# AES_HWR1_M2018.net
KiCad netlist of a schematic drawn in EAGLE
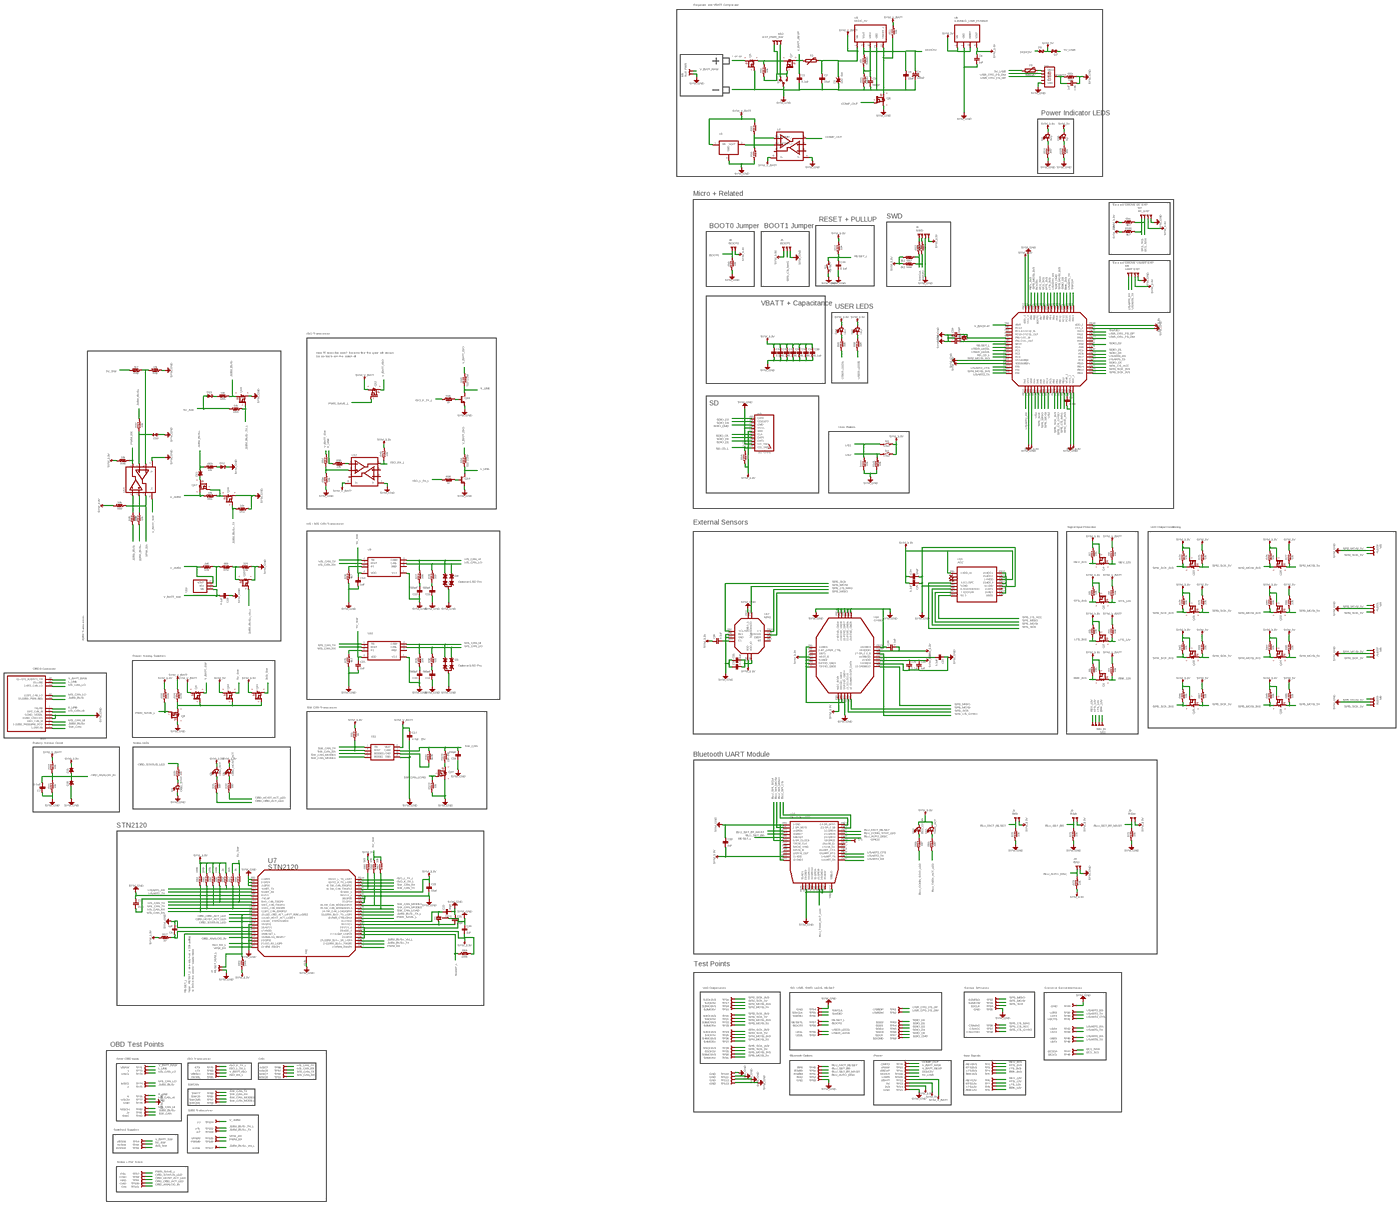
[diagram p0: schematic, sheet 1, overview]
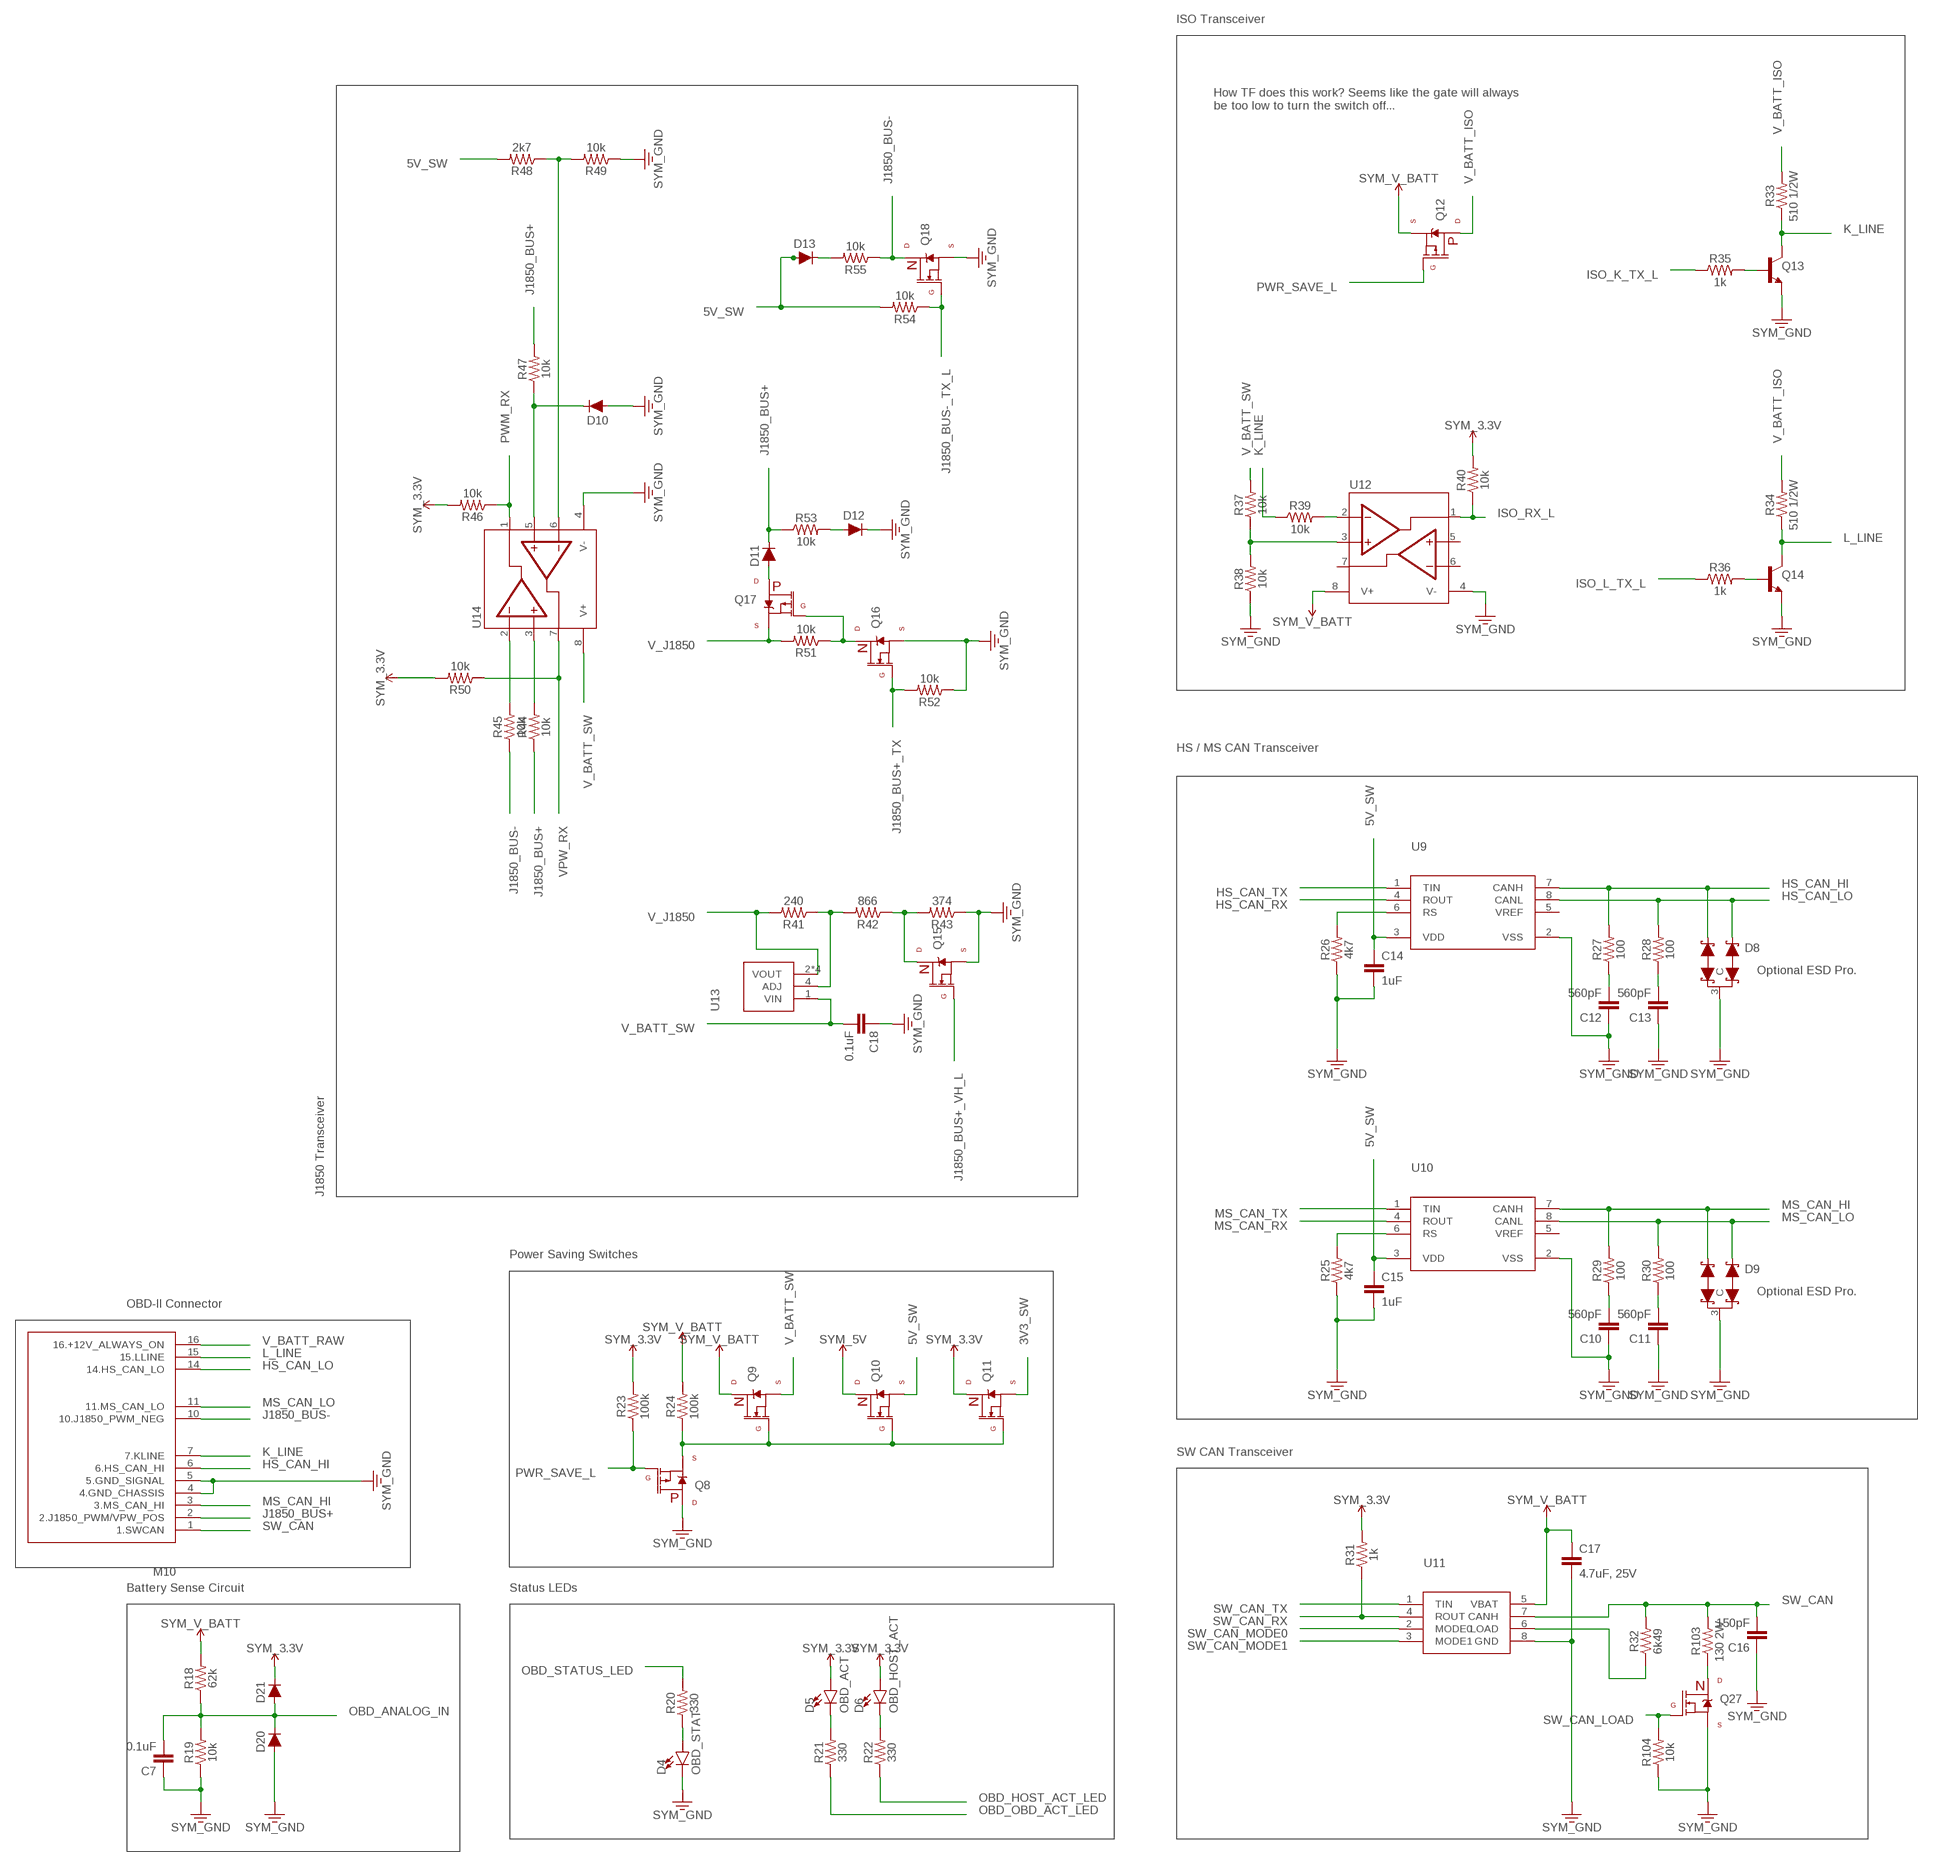
[diagram p1: schematic, sheet 1, part 1 of 5]
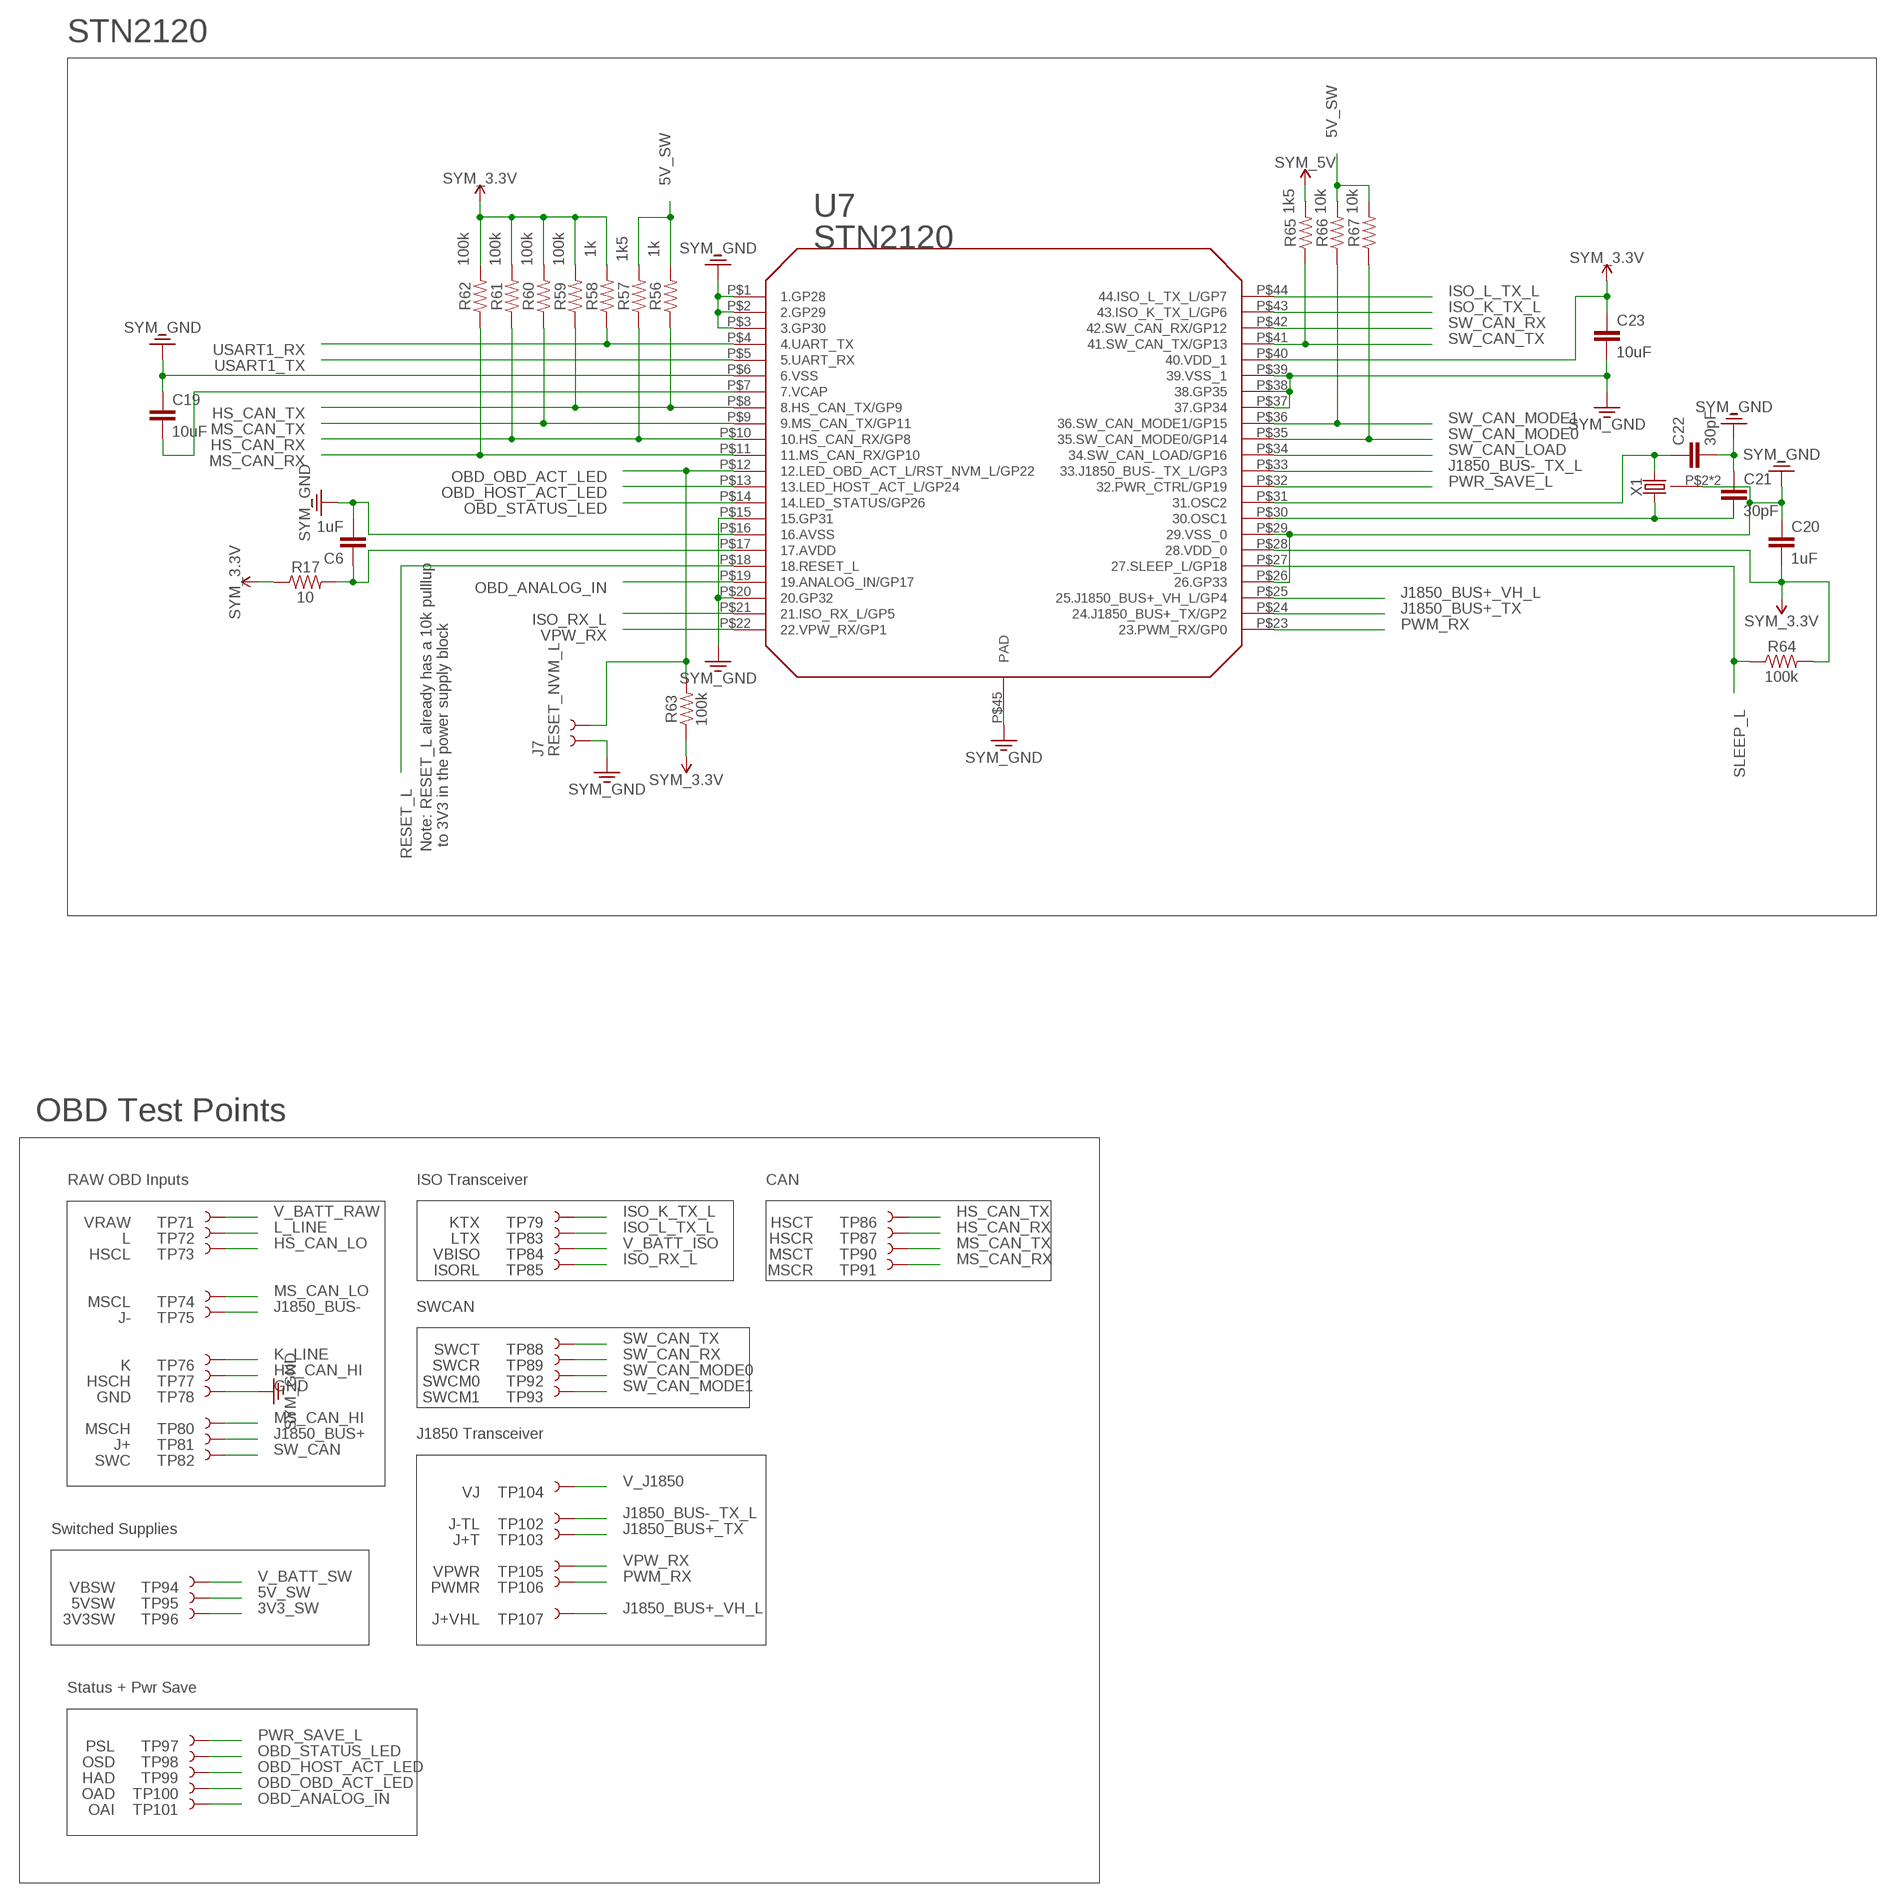
[diagram p2: schematic, sheet 1, part 2 of 5]
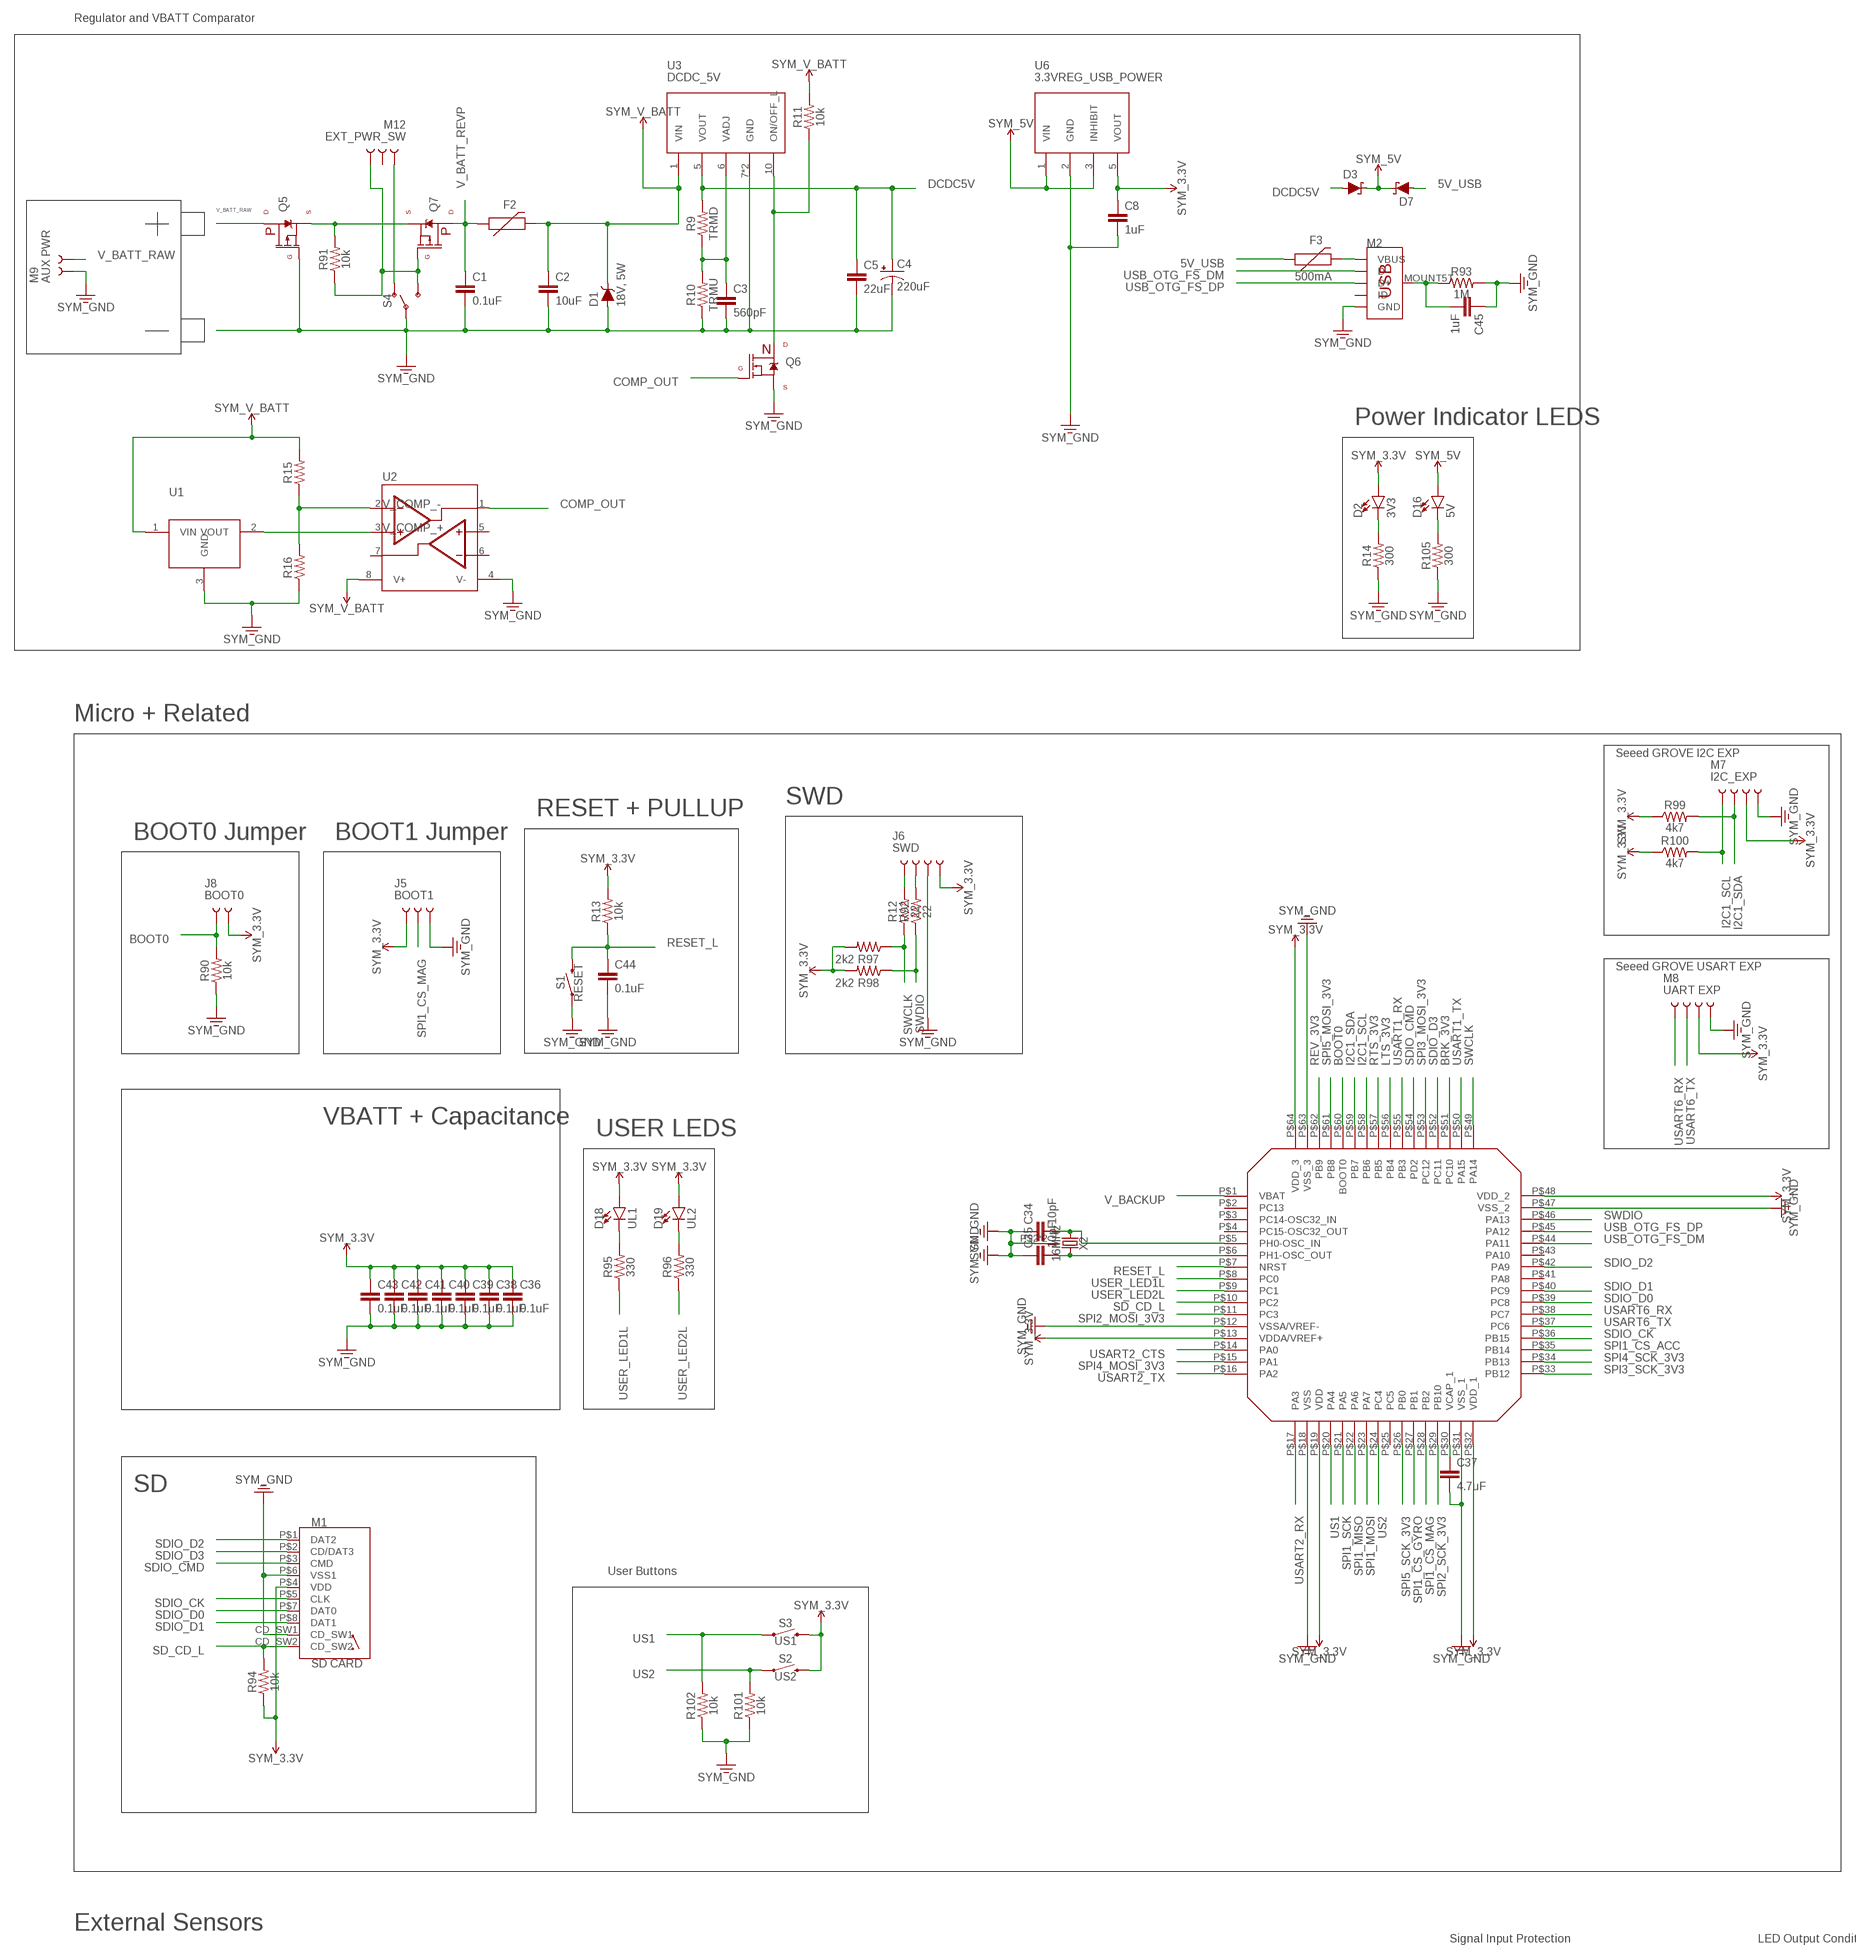
[diagram p3: schematic, sheet 1, part 3 of 5]
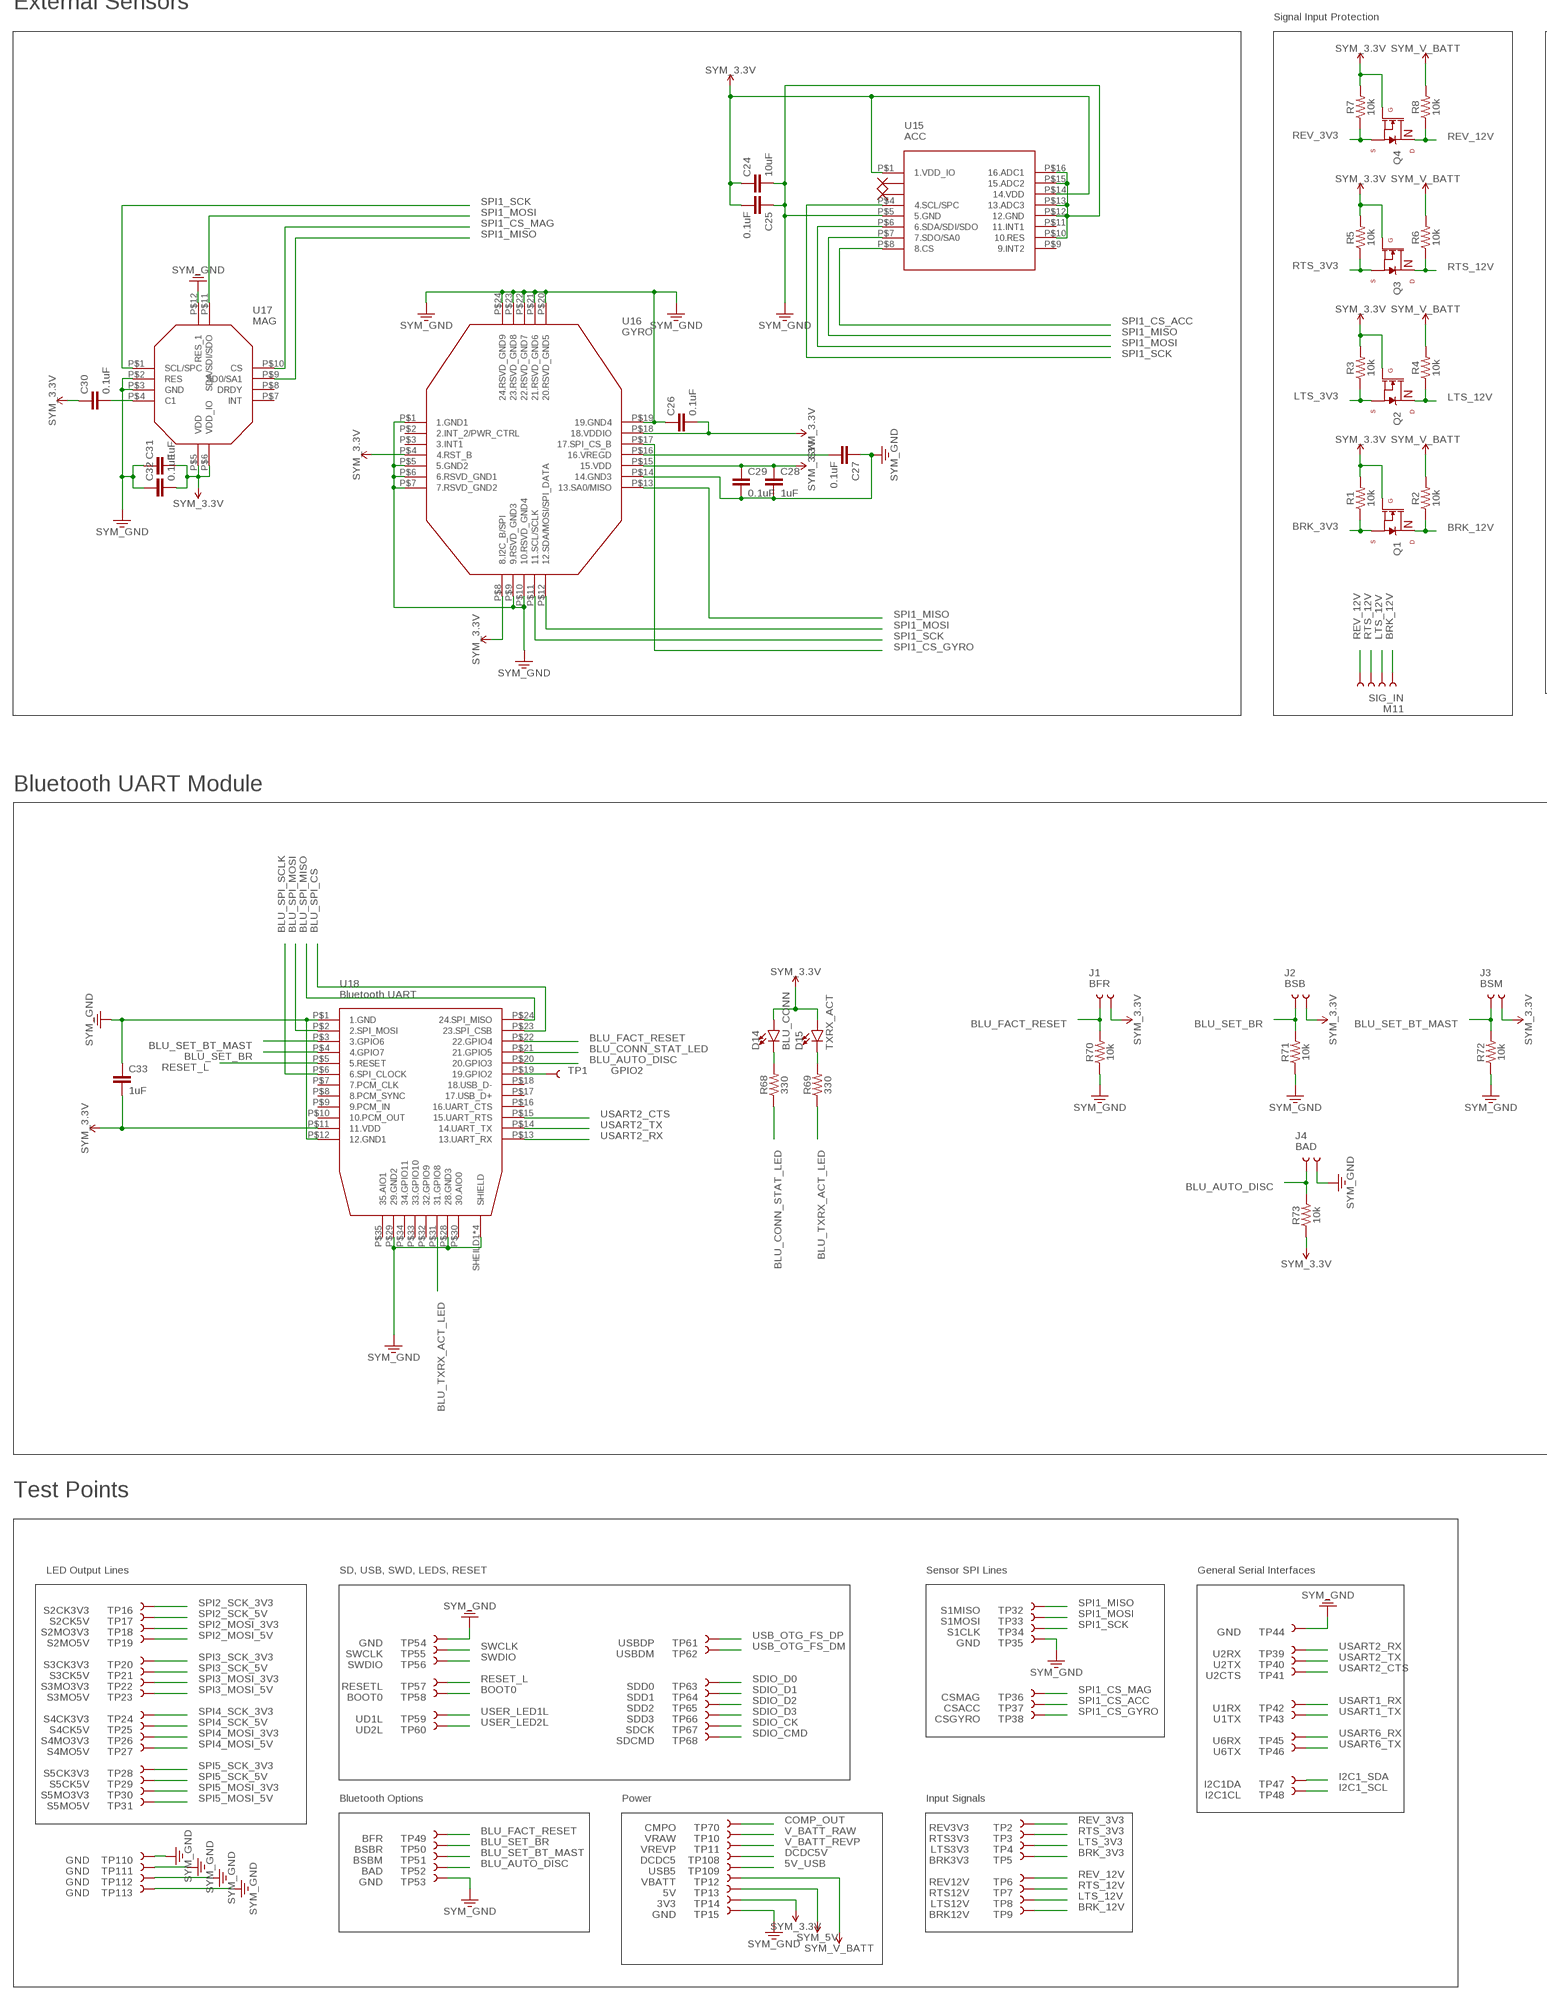
[diagram p4: schematic, sheet 1, part 4 of 5]
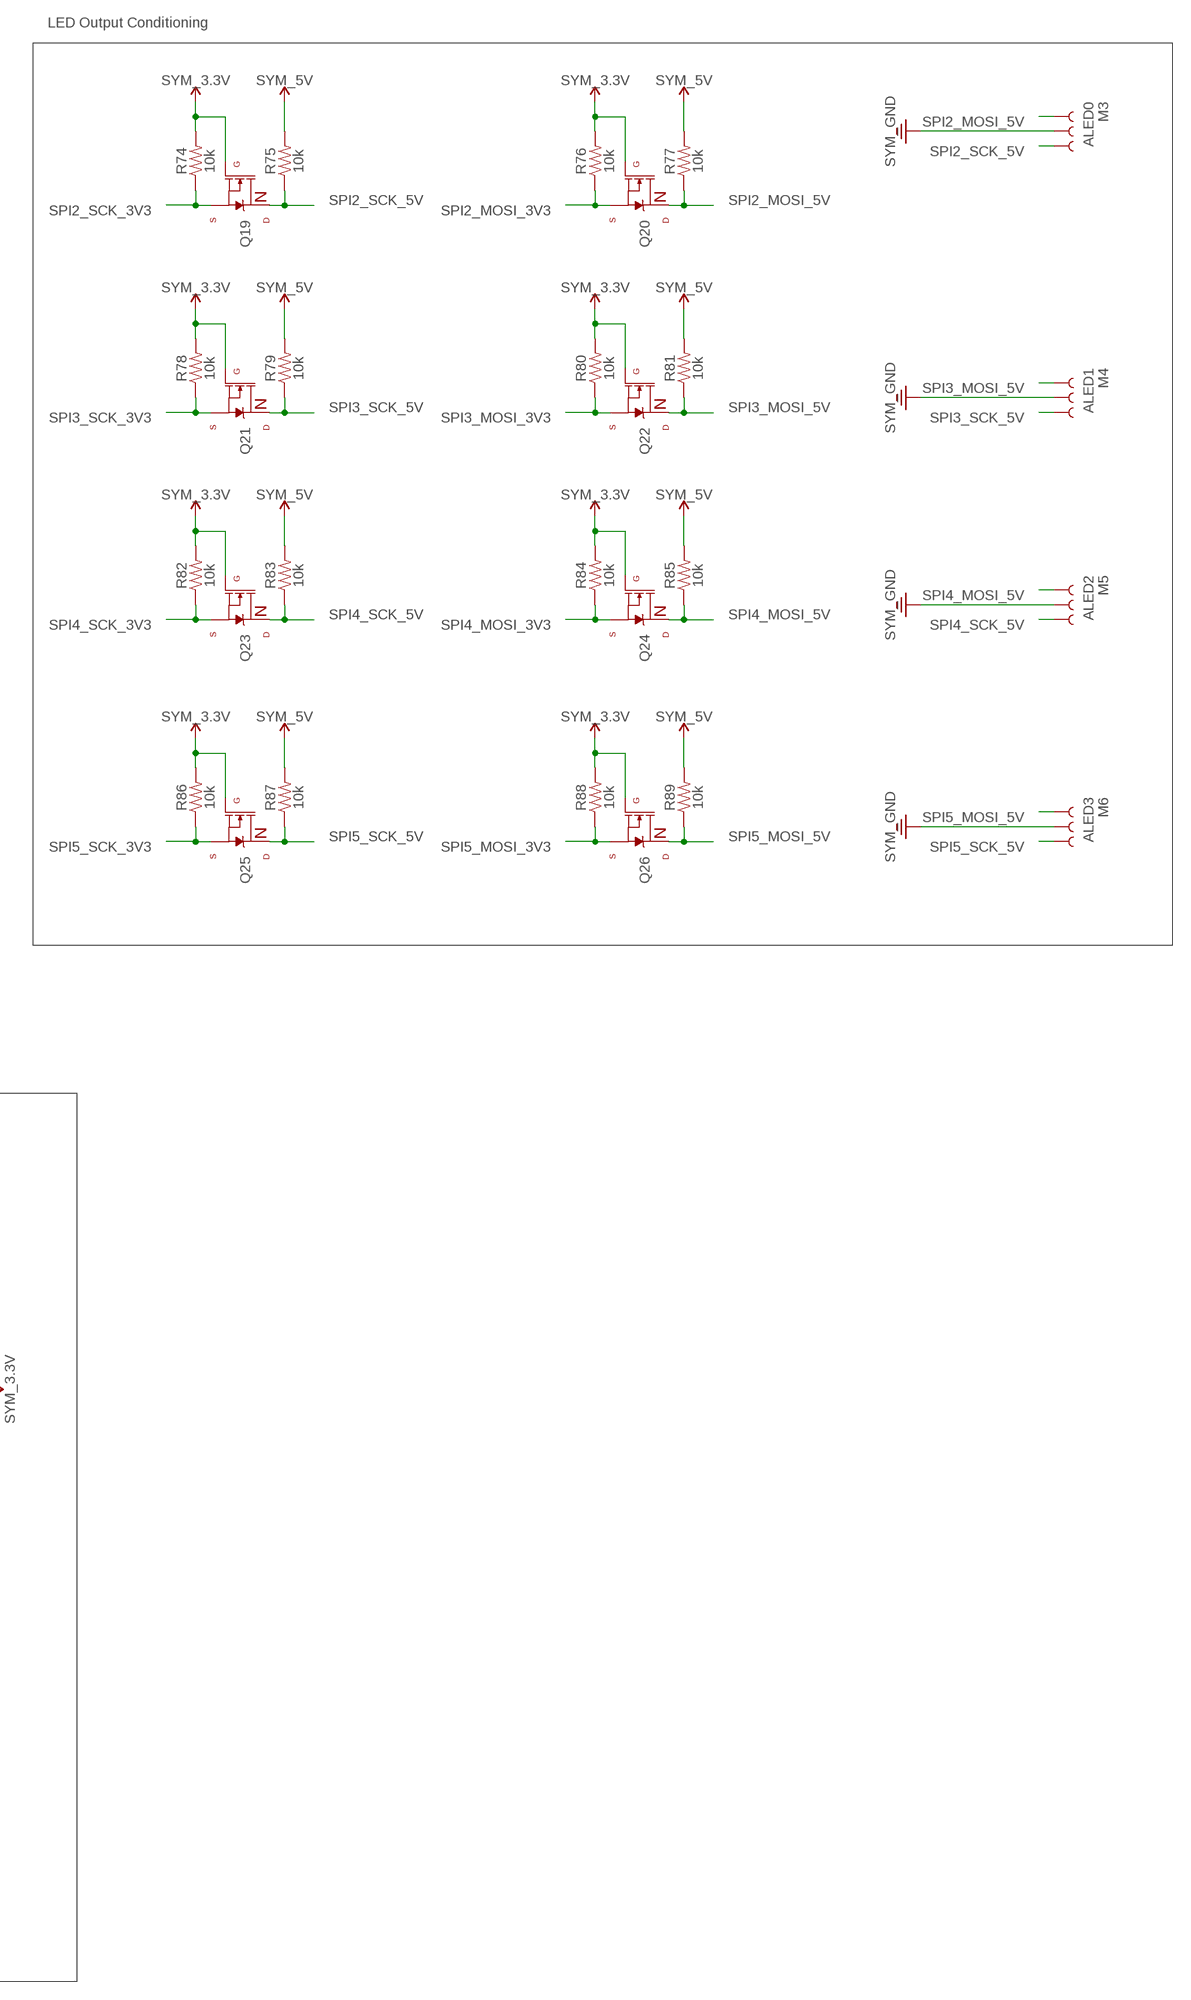
[diagram p5: schematic, sheet 1, part 5 of 5]

(export (version "E")
  (design (tool "Eeschema 10.0.6"))
  (components
    (comp (ref "C1")
      (value "0.1uF")
      (footprint "eagle-import:0603")
      (libsource (lib "eagle-import") (part "PASS_CAP_CER-SMD_0603"))
    )
    (comp (ref "C2")
      (value "10uF")
      (footprint "eagle-import:1206")
      (libsource (lib "eagle-import") (part "PASS_CAP_CER-SMD_1206"))
    )
    (comp (ref "C3")
      (value "560pF")
      (footprint "eagle-import:0603")
      (libsource (lib "eagle-import") (part "PASS_CAP_CER-SMD_0603"))
    )
    (comp (ref "C4")
      (value "220uF")
      (footprint "eagle-import:2917_P")
      (libsource (lib "eagle-import") (part "PASS_CAP_TANT"))
    )
    (comp (ref "C5")
      (value "22uF")
      (footprint "eagle-import:1206")
      (libsource (lib "eagle-import") (part "PASS_CAP_CER-SMD_1206"))
    )
    (comp (ref "C6")
      (value "1uF")
      (footprint "eagle-import:0603")
      (libsource (lib "eagle-import") (part "PASS_CAP_CER-SMD_0603"))
    )
    (comp (ref "C7")
      (value "0.1uF")
      (footprint "eagle-import:0603")
      (libsource (lib "eagle-import") (part "PASS_CAP_CER-SMD_0603"))
    )
    (comp (ref "C8")
      (value "1uF")
      (footprint "eagle-import:0603")
      (libsource (lib "eagle-import") (part "PASS_CAP_CER-SMD_0603"))
    )
    (comp (ref "C10")
      (value "560pF")
      (footprint "eagle-import:0603")
      (libsource (lib "eagle-import") (part "PASS_CAP_CER-SMD_0603"))
    )
    (comp (ref "C11")
      (value "560pF")
      (footprint "eagle-import:0603")
      (libsource (lib "eagle-import") (part "PASS_CAP_CER-SMD_0603"))
    )
    (comp (ref "C12")
      (value "560pF")
      (footprint "eagle-import:0603")
      (libsource (lib "eagle-import") (part "PASS_CAP_CER-SMD_0603"))
    )
    (comp (ref "C13")
      (value "560pF")
      (footprint "eagle-import:0603")
      (libsource (lib "eagle-import") (part "PASS_CAP_CER-SMD_0603"))
    )
    (comp (ref "C14")
      (value "1uF")
      (footprint "eagle-import:0603")
      (libsource (lib "eagle-import") (part "PASS_CAP_CER-SMD_0603"))
    )
    (comp (ref "C15")
      (value "1uF")
      (footprint "eagle-import:0603")
      (libsource (lib "eagle-import") (part "PASS_CAP_CER-SMD_0603"))
    )
    (comp (ref "C16")
      (value "150pF")
      (footprint "eagle-import:0603")
      (libsource (lib "eagle-import") (part "PASS_CAP_CER-SMD_0603"))
    )
    (comp (ref "C17")
      (value "4.7uF, 25V")
      (footprint "eagle-import:0603")
      (libsource (lib "eagle-import") (part "PASS_CAP_CER-SMD_0603"))
    )
    (comp (ref "C18")
      (value "0.1uF")
      (footprint "eagle-import:0603")
      (libsource (lib "eagle-import") (part "PASS_CAP_CER-SMD_0603"))
    )
    (comp (ref "C19")
      (value "10uF")
      (footprint "eagle-import:1206")
      (libsource (lib "eagle-import") (part "PASS_CAP_CER-SMD_1206"))
    )
    (comp (ref "C20")
      (value "1uF")
      (footprint "eagle-import:0603")
      (libsource (lib "eagle-import") (part "PASS_CAP_CER-SMD_0603"))
    )
    (comp (ref "C21")
      (value "30pF")
      (footprint "eagle-import:0603")
      (libsource (lib "eagle-import") (part "PASS_CAP_CER-SMD_0603"))
    )
    (comp (ref "C22")
      (value "30pF")
      (footprint "eagle-import:0603")
      (libsource (lib "eagle-import") (part "PASS_CAP_CER-SMD_0603"))
    )
    (comp (ref "C23")
      (value "10uF")
      (footprint "eagle-import:0603")
      (libsource (lib "eagle-import") (part "PASS_CAP_CER-SMD_0603"))
    )
    (comp (ref "C24")
      (value "10uF")
      (footprint "eagle-import:0603")
      (libsource (lib "eagle-import") (part "PASS_CAP_CER-SMD_0603"))
    )
    (comp (ref "C25")
      (value "0.1uF")
      (footprint "eagle-import:0603")
      (libsource (lib "eagle-import") (part "PASS_CAP_CER-SMD_0603"))
    )
    (comp (ref "C26")
      (value "0.1uF")
      (footprint "eagle-import:0603")
      (libsource (lib "eagle-import") (part "PASS_CAP_CER-SMD_0603"))
    )
    (comp (ref "C27")
      (value "0.1uF")
      (footprint "eagle-import:0603")
      (libsource (lib "eagle-import") (part "PASS_CAP_CER-SMD_0603"))
    )
    (comp (ref "C28")
      (value "1uF")
      (footprint "eagle-import:0603")
      (libsource (lib "eagle-import") (part "PASS_CAP_CER-SMD_0603"))
    )
    (comp (ref "C29")
      (value "0.1uF")
      (footprint "eagle-import:0603")
      (libsource (lib "eagle-import") (part "PASS_CAP_CER-SMD_0603"))
    )
    (comp (ref "C30")
      (value "0.1uF")
      (footprint "eagle-import:0603")
      (libsource (lib "eagle-import") (part "PASS_CAP_CER-SMD_0603"))
    )
    (comp (ref "C31")
      (value "1uF")
      (footprint "eagle-import:0603")
      (libsource (lib "eagle-import") (part "PASS_CAP_CER-SMD_0603"))
    )
    (comp (ref "C32")
      (value "0.1uF")
      (footprint "eagle-import:0603")
      (libsource (lib "eagle-import") (part "PASS_CAP_CER-SMD_0603"))
    )
    (comp (ref "C33")
      (value "1uF")
      (footprint "eagle-import:0603")
      (libsource (lib "eagle-import") (part "PASS_CAP_CER-SMD_0603"))
    )
    (comp (ref "C34")
      (value "10pF")
      (footprint "eagle-import:0603")
      (libsource (lib "eagle-import") (part "PASS_CAP_CER-SMD_0603"))
    )
    (comp (ref "C35")
      (value "10pF")
      (footprint "eagle-import:0603")
      (libsource (lib "eagle-import") (part "PASS_CAP_CER-SMD_0603"))
    )
    (comp (ref "C36")
      (value "0.1uF")
      (footprint "eagle-import:0603")
      (libsource (lib "eagle-import") (part "PASS_CAP_CER-SMD_0603"))
    )
    (comp (ref "C37")
      (value "4.7uF")
      (footprint "eagle-import:0603")
      (libsource (lib "eagle-import") (part "PASS_CAP_CER-SMD_0603"))
    )
    (comp (ref "C38")
      (value "0.1uF")
      (footprint "eagle-import:0603")
      (libsource (lib "eagle-import") (part "PASS_CAP_CER-SMD_0603"))
    )
    (comp (ref "C39")
      (value "0.1uF")
      (footprint "eagle-import:0603")
      (libsource (lib "eagle-import") (part "PASS_CAP_CER-SMD_0603"))
    )
    (comp (ref "C40")
      (value "0.1uF")
      (footprint "eagle-import:0603")
      (libsource (lib "eagle-import") (part "PASS_CAP_CER-SMD_0603"))
    )
    (comp (ref "C41")
      (value "0.1uF")
      (footprint "eagle-import:0603")
      (libsource (lib "eagle-import") (part "PASS_CAP_CER-SMD_0603"))
    )
    (comp (ref "C42")
      (value "0.1uF")
      (footprint "eagle-import:0603")
      (libsource (lib "eagle-import") (part "PASS_CAP_CER-SMD_0603"))
    )
    (comp (ref "C43")
      (value "0.1uF")
      (footprint "eagle-import:0603")
      (libsource (lib "eagle-import") (part "PASS_CAP_CER-SMD_0603"))
    )
    (comp (ref "C44")
      (value "0.1uF")
      (footprint "eagle-import:0603")
      (libsource (lib "eagle-import") (part "PASS_CAP_CER-SMD_0603"))
    )
    (comp (ref "C45")
      (value "1uF")
      (footprint "eagle-import:0603")
      (libsource (lib "eagle-import") (part "PASS_CAP_CER-SMD_0603"))
    )
    (comp (ref "D1")
      (value "18V, 5W")
      (footprint "eagle-import:DO-214AA")
      (libsource (lib "eagle-import") (part "PASS_DIODE_ZENER-SMBJ5355B"))
    )
    (comp (ref "D2")
      (value "3V3")
      (footprint "eagle-import:0603-POLAR")
      (libsource (lib "eagle-import") (part "PASS_DIODE_LED-SMLE13BC8TT86"))
    )
    (comp (ref "D3")
      (value "PASS_DIODE_SCHOTTKY-LSM115J")
      (footprint "eagle-import:DO-214BA")
      (libsource (lib "eagle-import") (part "PASS_DIODE_SCHOTTKY-LSM115J"))
    )
    (comp (ref "D4")
      (value "OBD_STAT")
      (footprint "eagle-import:0603-POLAR")
      (libsource (lib "eagle-import") (part "PASS_DIODE_LED-SMLE13BC8TT86"))
    )
    (comp (ref "D5")
      (value "OBD_ACT")
      (footprint "eagle-import:0603-POLAR")
      (libsource (lib "eagle-import") (part "PASS_DIODE_LED-LTST-C190KFKT"))
    )
    (comp (ref "D6")
      (value "OBD_HOST_ACT")
      (footprint "eagle-import:0603-POLAR")
      (libsource (lib "eagle-import") (part "PASS_DIODE_LED-LTST-C190KFKT"))
    )
    (comp (ref "D7")
      (value "PASS_DIODE_SCHOTTKY-LSM115J")
      (footprint "eagle-import:DO-214BA")
      (libsource (lib "eagle-import") (part "PASS_DIODE_SCHOTTKY-LSM115J"))
    )
    (comp (ref "D8")
      (value "PASS_DIODE_ESD_CAN-PESD1CAN-UX")
      (footprint "eagle-import:SOT23-3")
      (libsource (lib "eagle-import") (part "PASS_DIODE_ESD_CAN-PESD1CAN-UX"))
    )
    (comp (ref "D9")
      (value "PASS_DIODE_ESD_CAN-PESD1CAN-UX")
      (footprint "eagle-import:SOT23-3")
      (libsource (lib "eagle-import") (part "PASS_DIODE_ESD_CAN-PESD1CAN-UX"))
    )
    (comp (ref "D10")
      (value "PASS_DIODE_GEN-1N4148X")
      (footprint "eagle-import:SOD-523")
      (libsource (lib "eagle-import") (part "PASS_DIODE_GEN-1N4148X"))
    )
    (comp (ref "D11")
      (value "PASS_DIODE_GEN-1N4148X")
      (footprint "eagle-import:SOD-523")
      (libsource (lib "eagle-import") (part "PASS_DIODE_GEN-1N4148X"))
    )
    (comp (ref "D12")
      (value "PASS_DIODE_GEN-1N4148X")
      (footprint "eagle-import:SOD-523")
      (libsource (lib "eagle-import") (part "PASS_DIODE_GEN-1N4148X"))
    )
    (comp (ref "D13")
      (value "PASS_DIODE_GEN-1N4148X")
      (footprint "eagle-import:SOD-523")
      (libsource (lib "eagle-import") (part "PASS_DIODE_GEN-1N4148X"))
    )
    (comp (ref "D14")
      (value "BLU_CONN")
      (footprint "eagle-import:0603-POLAR")
      (libsource (lib "eagle-import") (part "PASS_DIODE_LED-SMLE13BC8TT86"))
    )
    (comp (ref "D15")
      (value "TXRX_ACT")
      (footprint "eagle-import:0603-POLAR")
      (libsource (lib "eagle-import") (part "PASS_DIODE_LED-LTST-C190KFKT"))
    )
    (comp (ref "D16")
      (value "5V")
      (footprint "eagle-import:0603-POLAR")
      (libsource (lib "eagle-import") (part "PASS_DIODE_LED-SMLE13BC8TT86"))
    )
    (comp (ref "D18")
      (value "UL1")
      (footprint "eagle-import:0603-POLAR")
      (libsource (lib "eagle-import") (part "PASS_DIODE_LED-SMLE13BC8TT86"))
    )
    (comp (ref "D19")
      (value "UL2")
      (footprint "eagle-import:0603-POLAR")
      (libsource (lib "eagle-import") (part "PASS_DIODE_LED-SMLE13BC8TT86"))
    )
    (comp (ref "D20")
      (value "PASS_DIODE_GEN-1N4148X")
      (footprint "eagle-import:SOD-523")
      (libsource (lib "eagle-import") (part "PASS_DIODE_GEN-1N4148X"))
    )
    (comp (ref "D21")
      (value "PASS_DIODE_GEN-1N4148X")
      (footprint "eagle-import:SOD-523")
      (libsource (lib "eagle-import") (part "PASS_DIODE_GEN-1N4148X"))
    )
    (comp (ref "F2")
      (value "PASS_FUSE_POLY-1206L200SLYR")
      (footprint "eagle-import:1206")
      (libsource (lib "eagle-import") (part "PASS_FUSE_POLY-1206L200SLYR"))
    )
    (comp (ref "F3")
      (value "500mA")
      (footprint "eagle-import:1206")
      (libsource (lib "eagle-import") (part "PASS_FUSE_POLY-0ZCJ0050FF2G"))
    )
    (comp (ref "J1")
      (value "BFR")
      (footprint "eagle-import:1X02")
      (libsource (lib "eagle-import") (part "ZMISC_JUMPER_2PTH_0.1IN"))
    )
    (comp (ref "J2")
      (value "BSB")
      (footprint "eagle-import:1X02")
      (libsource (lib "eagle-import") (part "ZMISC_JUMPER_2PTH_0.1IN"))
    )
    (comp (ref "J3")
      (value "BSM")
      (footprint "eagle-import:1X02")
      (libsource (lib "eagle-import") (part "ZMISC_JUMPER_2PTH_0.1IN"))
    )
    (comp (ref "J4")
      (value "BAD")
      (footprint "eagle-import:1X02")
      (libsource (lib "eagle-import") (part "ZMISC_JUMPER_2PTH_0.1IN"))
    )
    (comp (ref "J5")
      (value "BOOT1")
      (footprint "eagle-import:1X03")
      (libsource (lib "eagle-import") (part "ZMISC_JUMPER_3PTH_0.1IN"))
    )
    (comp (ref "J6")
      (value "SWD")
      (footprint "eagle-import:1X04")
      (libsource (lib "eagle-import") (part "ZMISC_JUMPER_4PTH_0.1IN"))
    )
    (comp (ref "J7")
      (value "RESET_NVM_L")
      (footprint "eagle-import:SMD_HEADER_0.1IN_2POS")
      (libsource (lib "eagle-import") (part "ZMISC_JUMPER_2SMD_0.1IN"))
    )
    (comp (ref "J8")
      (value "BOOT0")
      (footprint "eagle-import:1X02")
      (libsource (lib "eagle-import") (part "ZMISC_JUMPER_2PTH_0.1IN"))
    )
    (comp (ref "M1")
      (value "SD CARD")
      (footprint "eagle-import:SD_AMPHENOL_PUSH_PULL")
      (libsource (lib "eagle-import") (part "SD_MICRO_SOCKET-114-00841-68"))
    )
    (comp (ref "M2")
      (value "USB_MICRO-MID_MOUNT_REVERSIBLE")
      (footprint "eagle-import:MICROUSB")
      (libsource (lib "eagle-import") (part "USB_MICRO-MID_MOUNT_REVERSIBLE"))
    )
    (comp (ref "M3")
      (value "ALED0")
      (footprint "eagle-import:3_PIN_LOCK")
      (libsource (lib "eagle-import") (part "CONN_LED_OUT-MOLEX_5055670371"))
    )
    (comp (ref "M4")
      (value "ALED1")
      (footprint "eagle-import:3_PIN_LOCK")
      (libsource (lib "eagle-import") (part "CONN_LED_OUT-MOLEX_5055670371"))
    )
    (comp (ref "M5")
      (value "ALED2")
      (footprint "eagle-import:3_PIN_LOCK")
      (libsource (lib "eagle-import") (part "CONN_LED_OUT-MOLEX_5055670371"))
    )
    (comp (ref "M6")
      (value "ALED3")
      (footprint "eagle-import:3_PIN_LOCK")
      (libsource (lib "eagle-import") (part "CONN_LED_OUT-MOLEX_5055670371"))
    )
    (comp (ref "M7")
      (value "I2C_EXP")
      (footprint "eagle-import:4_PIN_LOCK")
      (libsource (lib "eagle-import") (part "CONN_LOCK_4-MOLEX_5055670471"))
    )
    (comp (ref "M8")
      (value "UART EXP")
      (footprint "eagle-import:4_PIN_LOCK")
      (libsource (lib "eagle-import") (part "CONN_LOCK_4-MOLEX_5055670471"))
    )
    (comp (ref "M9")
      (value "AUX PWR")
      (footprint "eagle-import:2_PIN_LOCK")
      (libsource (lib "eagle-import") (part "CONN_LOCK_2-5055670271"))
    )
    (comp (ref "M10")
      (value "OBD_CONN-4-794627-6")
      (footprint "eagle-import:OBD_16_SMD")
      (libsource (lib "eagle-import") (part "OBD_CONN-4-794627-6"))
    )
    (comp (ref "M11")
      (value "SIG_IN")
      (footprint "eagle-import:4_PIN_LOCK")
      (libsource (lib "eagle-import") (part "CONN_LOCK_4-MOLEX_5055670471"))
    )
    (comp (ref "M12")
      (value "EXT_PWR_SW")
      (footprint "eagle-import:3_PIN_LOCK")
      (libsource (lib "eagle-import") (part "CONN_LED_OUT-MOLEX_5055670371"))
    )
    (comp (ref "Q1")
      (value "PASS_NMOS-2N7002K")
      (footprint "eagle-import:SOT23-3@1")
      (libsource (lib "eagle-import") (part "PASS_NMOS-2N7002K"))
    )
    (comp (ref "Q2")
      (value "PASS_NMOS-2N7002K")
      (footprint "eagle-import:SOT23-3@1")
      (libsource (lib "eagle-import") (part "PASS_NMOS-2N7002K"))
    )
    (comp (ref "Q3")
      (value "PASS_NMOS-2N7002K")
      (footprint "eagle-import:SOT23-3@1")
      (libsource (lib "eagle-import") (part "PASS_NMOS-2N7002K"))
    )
    (comp (ref "Q4")
      (value "PASS_NMOS-2N7002K")
      (footprint "eagle-import:SOT23-3@1")
      (libsource (lib "eagle-import") (part "PASS_NMOS-2N7002K"))
    )
    (comp (ref "Q5")
      (value "AMP_MOSFET_PCH-MCQ4459")
      (footprint "eagle-import:SOP-8")
      (libsource (lib "eagle-import") (part "AMP_MOSFET_PCH-MCQ4459"))
    )
    (comp (ref "Q6")
      (value "AMP_MOSFET_NCH-2N7002K")
      (footprint "eagle-import:SOT23-3")
      (libsource (lib "eagle-import") (part "AMP_MOSFET_NCH-2N7002K"))
    )
    (comp (ref "Q7")
      (value "AMP_MOSFET_PCH-MCQ4459")
      (footprint "eagle-import:SOP-8")
      (libsource (lib "eagle-import") (part "AMP_MOSFET_PCH-MCQ4459"))
    )
    (comp (ref "Q8")
      (value "PASS_PMOS-MCQ4459")
      (footprint "eagle-import:SOP-8@1")
      (libsource (lib "eagle-import") (part "PASS_PMOS-MCQ4459"))
    )
    (comp (ref "Q9")
      (value "PASS_NMOS-2N7002K")
      (footprint "eagle-import:SOT23-3@1")
      (libsource (lib "eagle-import") (part "PASS_NMOS-2N7002K"))
    )
    (comp (ref "Q10")
      (value "PASS_NMOS-2N7002K")
      (footprint "eagle-import:SOT23-3@1")
      (libsource (lib "eagle-import") (part "PASS_NMOS-2N7002K"))
    )
    (comp (ref "Q11")
      (value "PASS_NMOS-2N7002K")
      (footprint "eagle-import:SOT23-3@1")
      (libsource (lib "eagle-import") (part "PASS_NMOS-2N7002K"))
    )
    (comp (ref "Q12")
      (value "AMP_MOSFET_PCH-MCQ4459")
      (footprint "eagle-import:SOP-8")
      (libsource (lib "eagle-import") (part "AMP_MOSFET_PCH-MCQ4459"))
    )
    (comp (ref "Q13")
      (value "AMP_BJT_NPNZXTN19100CFF")
      (footprint "eagle-import:SOT23-3")
      (libsource (lib "eagle-import") (part "AMP_BJT_NPNZXTN19100CFF"))
    )
    (comp (ref "Q14")
      (value "AMP_BJT_NPNZXTN19100CFF")
      (footprint "eagle-import:SOT23-3")
      (libsource (lib "eagle-import") (part "AMP_BJT_NPNZXTN19100CFF"))
    )
    (comp (ref "Q15")
      (value "AMP_MOSFET_NCH-2N7002K")
      (footprint "eagle-import:SOT23-3")
      (libsource (lib "eagle-import") (part "AMP_MOSFET_NCH-2N7002K"))
    )
    (comp (ref "Q16")
      (value "AMP_MOSFET_NCH-2N7002K")
      (footprint "eagle-import:SOT23-3")
      (libsource (lib "eagle-import") (part "AMP_MOSFET_NCH-2N7002K"))
    )
    (comp (ref "Q17")
      (value "AMP_MOSFET_PCH-MCQ4459")
      (footprint "eagle-import:SOP-8")
      (libsource (lib "eagle-import") (part "AMP_MOSFET_PCH-MCQ4459"))
    )
    (comp (ref "Q18")
      (value "AMP_MOSFET_NCH-2N7002K")
      (footprint "eagle-import:SOT23-3")
      (libsource (lib "eagle-import") (part "AMP_MOSFET_NCH-2N7002K"))
    )
    (comp (ref "Q19")
      (value "AMP_MOSFET_NCH-2N7002K")
      (footprint "eagle-import:SOT23-3")
      (libsource (lib "eagle-import") (part "AMP_MOSFET_NCH-2N7002K"))
    )
    (comp (ref "Q20")
      (value "AMP_MOSFET_NCH-2N7002K")
      (footprint "eagle-import:SOT23-3")
      (libsource (lib "eagle-import") (part "AMP_MOSFET_NCH-2N7002K"))
    )
    (comp (ref "Q21")
      (value "AMP_MOSFET_NCH-2N7002K")
      (footprint "eagle-import:SOT23-3")
      (libsource (lib "eagle-import") (part "AMP_MOSFET_NCH-2N7002K"))
    )
    (comp (ref "Q22")
      (value "AMP_MOSFET_NCH-2N7002K")
      (footprint "eagle-import:SOT23-3")
      (libsource (lib "eagle-import") (part "AMP_MOSFET_NCH-2N7002K"))
    )
    (comp (ref "Q23")
      (value "AMP_MOSFET_NCH-2N7002K")
      (footprint "eagle-import:SOT23-3")
      (libsource (lib "eagle-import") (part "AMP_MOSFET_NCH-2N7002K"))
    )
    (comp (ref "Q24")
      (value "AMP_MOSFET_NCH-2N7002K")
      (footprint "eagle-import:SOT23-3")
      (libsource (lib "eagle-import") (part "AMP_MOSFET_NCH-2N7002K"))
    )
    (comp (ref "Q25")
      (value "AMP_MOSFET_NCH-2N7002K")
      (footprint "eagle-import:SOT23-3")
      (libsource (lib "eagle-import") (part "AMP_MOSFET_NCH-2N7002K"))
    )
    (comp (ref "Q26")
      (value "AMP_MOSFET_NCH-2N7002K")
      (footprint "eagle-import:SOT23-3")
      (libsource (lib "eagle-import") (part "AMP_MOSFET_NCH-2N7002K"))
    )
    (comp (ref "Q27")
      (value "AMP_MOSFET_NCH-2N7002K")
      (footprint "eagle-import:SOT23-3")
      (libsource (lib "eagle-import") (part "AMP_MOSFET_NCH-2N7002K"))
    )
    (comp (ref "R1")
      (value "10k")
      (footprint "eagle-import:0603")
      (libsource (lib "eagle-import") (part "PASS_RES-SMD_0603"))
    )
    (comp (ref "R2")
      (value "10k")
      (footprint "eagle-import:0603")
      (libsource (lib "eagle-import") (part "PASS_RES-SMD_0603"))
    )
    (comp (ref "R3")
      (value "10k")
      (footprint "eagle-import:0603")
      (libsource (lib "eagle-import") (part "PASS_RES-SMD_0603"))
    )
    (comp (ref "R4")
      (value "10k")
      (footprint "eagle-import:0603")
      (libsource (lib "eagle-import") (part "PASS_RES-SMD_0603"))
    )
    (comp (ref "R5")
      (value "10k")
      (footprint "eagle-import:0603")
      (libsource (lib "eagle-import") (part "PASS_RES-SMD_0603"))
    )
    (comp (ref "R6")
      (value "10k")
      (footprint "eagle-import:0603")
      (libsource (lib "eagle-import") (part "PASS_RES-SMD_0603"))
    )
    (comp (ref "R7")
      (value "10k")
      (footprint "eagle-import:0603")
      (libsource (lib "eagle-import") (part "PASS_RES-SMD_0603"))
    )
    (comp (ref "R8")
      (value "10k")
      (footprint "eagle-import:0603")
      (libsource (lib "eagle-import") (part "PASS_RES-SMD_0603"))
    )
    (comp (ref "R9")
      (value "TRMD")
      (footprint "eagle-import:0603")
      (libsource (lib "eagle-import") (part "PASS_RES-SMD_0603"))
    )
    (comp (ref "R10")
      (value "TRMU")
      (footprint "eagle-import:0603")
      (libsource (lib "eagle-import") (part "PASS_RES-SMD_0603"))
    )
    (comp (ref "R11")
      (value "10k")
      (footprint "eagle-import:0603")
      (libsource (lib "eagle-import") (part "PASS_RES-SMD_0603"))
    )
    (comp (ref "R12")
      (value "22")
      (footprint "eagle-import:0603")
      (libsource (lib "eagle-import") (part "PASS_RES-SMD_0603"))
    )
    (comp (ref "R13")
      (value "10k")
      (footprint "eagle-import:0603")
      (libsource (lib "eagle-import") (part "PASS_RES-SMD_0603"))
    )
    (comp (ref "R14")
      (value "300")
      (footprint "eagle-import:0603")
      (libsource (lib "eagle-import") (part "PASS_RES-SMD_0603"))
    )
    (comp (ref "R15")
      (value "PASS_RES-SMD_0603")
      (footprint "eagle-import:0603")
      (libsource (lib "eagle-import") (part "PASS_RES-SMD_0603"))
    )
    (comp (ref "R16")
      (value "PASS_RES-SMD_0603")
      (footprint "eagle-import:0603")
      (libsource (lib "eagle-import") (part "PASS_RES-SMD_0603"))
    )
    (comp (ref "R17")
      (value "10")
      (footprint "eagle-import:0603")
      (libsource (lib "eagle-import") (part "PASS_RES-SMD_0603"))
    )
    (comp (ref "R18")
      (value "62k")
      (footprint "eagle-import:0603")
      (libsource (lib "eagle-import") (part "PASS_RES-SMD_0603"))
    )
    (comp (ref "R19")
      (value "10k")
      (footprint "eagle-import:0603")
      (libsource (lib "eagle-import") (part "PASS_RES-SMD_0603"))
    )
    (comp (ref "R20")
      (value "330")
      (footprint "eagle-import:0603")
      (libsource (lib "eagle-import") (part "PASS_RES-SMD_0603"))
    )
    (comp (ref "R21")
      (value "330")
      (footprint "eagle-import:0603")
      (libsource (lib "eagle-import") (part "PASS_RES-SMD_0603"))
    )
    (comp (ref "R22")
      (value "330")
      (footprint "eagle-import:0603")
      (libsource (lib "eagle-import") (part "PASS_RES-SMD_0603"))
    )
    (comp (ref "R23")
      (value "100k")
      (footprint "eagle-import:0603")
      (libsource (lib "eagle-import") (part "PASS_RES-SMD_0603"))
    )
    (comp (ref "R24")
      (value "100k")
      (footprint "eagle-import:0603")
      (libsource (lib "eagle-import") (part "PASS_RES-SMD_0603"))
    )
    (comp (ref "R25")
      (value "4k7")
      (footprint "eagle-import:0603")
      (libsource (lib "eagle-import") (part "PASS_RES-SMD_0603"))
    )
    (comp (ref "R26")
      (value "4k7")
      (footprint "eagle-import:0603")
      (libsource (lib "eagle-import") (part "PASS_RES-SMD_0603"))
    )
    (comp (ref "R27")
      (value "100")
      (footprint "eagle-import:0603")
      (libsource (lib "eagle-import") (part "PASS_RES-SMD_0603"))
    )
    (comp (ref "R28")
      (value "100")
      (footprint "eagle-import:0603")
      (libsource (lib "eagle-import") (part "PASS_RES-SMD_0603"))
    )
    (comp (ref "R29")
      (value "100")
      (footprint "eagle-import:0603")
      (libsource (lib "eagle-import") (part "PASS_RES-SMD_0603"))
    )
    (comp (ref "R30")
      (value "100")
      (footprint "eagle-import:0603")
      (libsource (lib "eagle-import") (part "PASS_RES-SMD_0603"))
    )
    (comp (ref "R31")
      (value "1k")
      (footprint "eagle-import:0603")
      (libsource (lib "eagle-import") (part "PASS_RES-SMD_0603"))
    )
    (comp (ref "R32")
      (value "6k49")
      (footprint "eagle-import:0603")
      (libsource (lib "eagle-import") (part "PASS_RES-SMD_0603"))
    )
    (comp (ref "R33")
      (value "510 1/2W")
      (footprint "eagle-import:1206")
      (libsource (lib "eagle-import") (part "PASS_RES-SMD_1206"))
    )
    (comp (ref "R34")
      (value "510 1/2W")
      (footprint "eagle-import:1206")
      (libsource (lib "eagle-import") (part "PASS_RES-SMD_1206"))
    )
    (comp (ref "R35")
      (value "1k")
      (footprint "eagle-import:0603")
      (libsource (lib "eagle-import") (part "PASS_RES-SMD_0603"))
    )
    (comp (ref "R36")
      (value "1k")
      (footprint "eagle-import:0603")
      (libsource (lib "eagle-import") (part "PASS_RES-SMD_0603"))
    )
    (comp (ref "R37")
      (value "10k")
      (footprint "eagle-import:0603")
      (libsource (lib "eagle-import") (part "PASS_RES-SMD_0603"))
    )
    (comp (ref "R38")
      (value "10k")
      (footprint "eagle-import:0603")
      (libsource (lib "eagle-import") (part "PASS_RES-SMD_0603"))
    )
    (comp (ref "R39")
      (value "10k")
      (footprint "eagle-import:0603")
      (libsource (lib "eagle-import") (part "PASS_RES-SMD_0603"))
    )
    (comp (ref "R40")
      (value "10k")
      (footprint "eagle-import:0603")
      (libsource (lib "eagle-import") (part "PASS_RES-SMD_0603"))
    )
    (comp (ref "R41")
      (value "240")
      (footprint "eagle-import:0603")
      (libsource (lib "eagle-import") (part "PASS_RES-SMD_0603"))
    )
    (comp (ref "R42")
      (value "866")
      (footprint "eagle-import:0603")
      (libsource (lib "eagle-import") (part "PASS_RES-SMD_0603"))
    )
    (comp (ref "R43")
      (value "374")
      (footprint "eagle-import:0603")
      (libsource (lib "eagle-import") (part "PASS_RES-SMD_0603"))
    )
    (comp (ref "R44")
      (value "10k")
      (footprint "eagle-import:0603")
      (libsource (lib "eagle-import") (part "PASS_RES-SMD_0603"))
    )
    (comp (ref "R45")
      (value "10k")
      (footprint "eagle-import:0603")
      (libsource (lib "eagle-import") (part "PASS_RES-SMD_0603"))
    )
    (comp (ref "R46")
      (value "10k")
      (footprint "eagle-import:0603")
      (libsource (lib "eagle-import") (part "PASS_RES-SMD_0603"))
    )
    (comp (ref "R47")
      (value "10k")
      (footprint "eagle-import:0603")
      (libsource (lib "eagle-import") (part "PASS_RES-SMD_0603"))
    )
    (comp (ref "R48")
      (value "2k7")
      (footprint "eagle-import:0603")
      (libsource (lib "eagle-import") (part "PASS_RES-SMD_0603"))
    )
    (comp (ref "R49")
      (value "10k")
      (footprint "eagle-import:0603")
      (libsource (lib "eagle-import") (part "PASS_RES-SMD_0603"))
    )
    (comp (ref "R50")
      (value "10k")
      (footprint "eagle-import:0603")
      (libsource (lib "eagle-import") (part "PASS_RES-SMD_0603"))
    )
    (comp (ref "R51")
      (value "10k")
      (footprint "eagle-import:0603")
      (libsource (lib "eagle-import") (part "PASS_RES-SMD_0603"))
    )
    (comp (ref "R52")
      (value "10k")
      (footprint "eagle-import:0603")
      (libsource (lib "eagle-import") (part "PASS_RES-SMD_0603"))
    )
    (comp (ref "R53")
      (value "10k")
      (footprint "eagle-import:0603")
      (libsource (lib "eagle-import") (part "PASS_RES-SMD_0603"))
    )
    (comp (ref "R54")
      (value "10k")
      (footprint "eagle-import:0603")
      (libsource (lib "eagle-import") (part "PASS_RES-SMD_0603"))
    )
    (comp (ref "R55")
      (value "10k")
      (footprint "eagle-import:0603")
      (libsource (lib "eagle-import") (part "PASS_RES-SMD_0603"))
    )
    (comp (ref "R56")
      (value "1k")
      (footprint "eagle-import:0603")
      (libsource (lib "eagle-import") (part "PASS_RES-SMD_0603"))
    )
    (comp (ref "R57")
      (value "1k5")
      (footprint "eagle-import:0603")
      (libsource (lib "eagle-import") (part "PASS_RES-SMD_0603"))
    )
    (comp (ref "R58")
      (value "1k")
      (footprint "eagle-import:0603")
      (libsource (lib "eagle-import") (part "PASS_RES-SMD_0603"))
    )
    (comp (ref "R59")
      (value "100k")
      (footprint "eagle-import:0603")
      (libsource (lib "eagle-import") (part "PASS_RES-SMD_0603"))
    )
    (comp (ref "R60")
      (value "100k")
      (footprint "eagle-import:0603")
      (libsource (lib "eagle-import") (part "PASS_RES-SMD_0603"))
    )
    (comp (ref "R61")
      (value "100k")
      (footprint "eagle-import:0603")
      (libsource (lib "eagle-import") (part "PASS_RES-SMD_0603"))
    )
    (comp (ref "R62")
      (value "100k")
      (footprint "eagle-import:0603")
      (libsource (lib "eagle-import") (part "PASS_RES-SMD_0603"))
    )
    (comp (ref "R63")
      (value "100k")
      (footprint "eagle-import:0603")
      (libsource (lib "eagle-import") (part "PASS_RES-SMD_0603"))
    )
    (comp (ref "R64")
      (value "100k")
      (footprint "eagle-import:0603")
      (libsource (lib "eagle-import") (part "PASS_RES-SMD_0603"))
    )
    (comp (ref "R65")
      (value "1k5")
      (footprint "eagle-import:0603")
      (libsource (lib "eagle-import") (part "PASS_RES-SMD_0603"))
    )
    (comp (ref "R66")
      (value "10k")
      (footprint "eagle-import:0603")
      (libsource (lib "eagle-import") (part "PASS_RES-SMD_0603"))
    )
    (comp (ref "R67")
      (value "10k")
      (footprint "eagle-import:0603")
      (libsource (lib "eagle-import") (part "PASS_RES-SMD_0603"))
    )
    (comp (ref "R68")
      (value "330")
      (footprint "eagle-import:0603")
      (libsource (lib "eagle-import") (part "PASS_RES-SMD_0603"))
    )
    (comp (ref "R69")
      (value "330")
      (footprint "eagle-import:0603")
      (libsource (lib "eagle-import") (part "PASS_RES-SMD_0603"))
    )
    (comp (ref "R70")
      (value "10k")
      (footprint "eagle-import:0603")
      (libsource (lib "eagle-import") (part "PASS_RES-SMD_0603"))
    )
    (comp (ref "R71")
      (value "10k")
      (footprint "eagle-import:0603")
      (libsource (lib "eagle-import") (part "PASS_RES-SMD_0603"))
    )
    (comp (ref "R72")
      (value "10k")
      (footprint "eagle-import:0603")
      (libsource (lib "eagle-import") (part "PASS_RES-SMD_0603"))
    )
    (comp (ref "R73")
      (value "10k")
      (footprint "eagle-import:0603")
      (libsource (lib "eagle-import") (part "PASS_RES-SMD_0603"))
    )
    (comp (ref "R74")
      (value "10k")
      (footprint "eagle-import:0603")
      (libsource (lib "eagle-import") (part "PASS_RES-SMD_0603"))
    )
    (comp (ref "R75")
      (value "10k")
      (footprint "eagle-import:0603")
      (libsource (lib "eagle-import") (part "PASS_RES-SMD_0603"))
    )
    (comp (ref "R76")
      (value "10k")
      (footprint "eagle-import:0603")
      (libsource (lib "eagle-import") (part "PASS_RES-SMD_0603"))
    )
    (comp (ref "R77")
      (value "10k")
      (footprint "eagle-import:0603")
      (libsource (lib "eagle-import") (part "PASS_RES-SMD_0603"))
    )
    (comp (ref "R78")
      (value "10k")
      (footprint "eagle-import:0603")
      (libsource (lib "eagle-import") (part "PASS_RES-SMD_0603"))
    )
    (comp (ref "R79")
      (value "10k")
      (footprint "eagle-import:0603")
      (libsource (lib "eagle-import") (part "PASS_RES-SMD_0603"))
    )
    (comp (ref "R80")
      (value "10k")
      (footprint "eagle-import:0603")
      (libsource (lib "eagle-import") (part "PASS_RES-SMD_0603"))
    )
    (comp (ref "R81")
      (value "10k")
      (footprint "eagle-import:0603")
      (libsource (lib "eagle-import") (part "PASS_RES-SMD_0603"))
    )
    (comp (ref "R82")
      (value "10k")
      (footprint "eagle-import:0603")
      (libsource (lib "eagle-import") (part "PASS_RES-SMD_0603"))
    )
    (comp (ref "R83")
      (value "10k")
      (footprint "eagle-import:0603")
      (libsource (lib "eagle-import") (part "PASS_RES-SMD_0603"))
    )
    (comp (ref "R84")
      (value "10k")
      (footprint "eagle-import:0603")
      (libsource (lib "eagle-import") (part "PASS_RES-SMD_0603"))
    )
    (comp (ref "R85")
      (value "10k")
      (footprint "eagle-import:0603")
      (libsource (lib "eagle-import") (part "PASS_RES-SMD_0603"))
    )
    (comp (ref "R86")
      (value "10k")
      (footprint "eagle-import:0603")
      (libsource (lib "eagle-import") (part "PASS_RES-SMD_0603"))
    )
    (comp (ref "R87")
      (value "10k")
      (footprint "eagle-import:0603")
      (libsource (lib "eagle-import") (part "PASS_RES-SMD_0603"))
    )
    (comp (ref "R88")
      (value "10k")
      (footprint "eagle-import:0603")
      (libsource (lib "eagle-import") (part "PASS_RES-SMD_0603"))
    )
    (comp (ref "R89")
      (value "10k")
      (footprint "eagle-import:0603")
      (libsource (lib "eagle-import") (part "PASS_RES-SMD_0603"))
    )
    (comp (ref "R90")
      (value "10k")
      (footprint "eagle-import:0603")
      (libsource (lib "eagle-import") (part "PASS_RES-SMD_0603"))
    )
    (comp (ref "R91")
      (value "10k")
      (footprint "eagle-import:0603")
      (libsource (lib "eagle-import") (part "PASS_RES-SMD_0603"))
    )
    (comp (ref "R92")
      (value "22")
      (footprint "eagle-import:0603")
      (libsource (lib "eagle-import") (part "PASS_RES-SMD_0603"))
    )
    (comp (ref "R93")
      (value "1M")
      (footprint "eagle-import:0603")
      (libsource (lib "eagle-import") (part "PASS_RES-SMD_0603"))
    )
    (comp (ref "R94")
      (value "10k")
      (footprint "eagle-import:0603")
      (libsource (lib "eagle-import") (part "PASS_RES-SMD_0603"))
    )
    (comp (ref "R95")
      (value "330")
      (footprint "eagle-import:0603")
      (libsource (lib "eagle-import") (part "PASS_RES-SMD_0603"))
    )
    (comp (ref "R96")
      (value "330")
      (footprint "eagle-import:0603")
      (libsource (lib "eagle-import") (part "PASS_RES-SMD_0603"))
    )
    (comp (ref "R97")
      (value "2k2")
      (footprint "eagle-import:0603")
      (libsource (lib "eagle-import") (part "PASS_RES-SMD_0603"))
    )
    (comp (ref "R98")
      (value "2k2")
      (footprint "eagle-import:0603")
      (libsource (lib "eagle-import") (part "PASS_RES-SMD_0603"))
    )
    (comp (ref "R99")
      (value "4k7")
      (footprint "eagle-import:0603")
      (libsource (lib "eagle-import") (part "PASS_RES-SMD_0603"))
    )
    (comp (ref "R100")
      (value "4k7")
      (footprint "eagle-import:0603")
      (libsource (lib "eagle-import") (part "PASS_RES-SMD_0603"))
    )
    (comp (ref "R101")
      (value "10k")
      (footprint "eagle-import:0603")
      (libsource (lib "eagle-import") (part "PASS_RES-SMD_0603"))
    )
    (comp (ref "R102")
      (value "10k")
      (footprint "eagle-import:0603")
      (libsource (lib "eagle-import") (part "PASS_RES-SMD_0603"))
    )
    (comp (ref "R103")
      (value "130 2W")
      (footprint "eagle-import:2512")
      (libsource (lib "eagle-import") (part "PASS_RES-SMD_2512"))
    )
    (comp (ref "R104")
      (value "10k")
      (footprint "eagle-import:0603")
      (libsource (lib "eagle-import") (part "PASS_RES-SMD_0603"))
    )
    (comp (ref "R105")
      (value "300")
      (footprint "eagle-import:0603")
      (libsource (lib "eagle-import") (part "PASS_RES-SMD_0603"))
    )
    (comp (ref "S1")
      (value "RESET")
      (footprint "eagle-import:PTS525")
      (libsource (lib "eagle-import") (part "BUTTON_TEMP_ON"))
    )
    (comp (ref "S2")
      (value "US2")
      (footprint "eagle-import:PTS525")
      (libsource (lib "eagle-import") (part "BUTTON_TEMP_ON"))
    )
    (comp (ref "S3")
      (value "US1")
      (footprint "eagle-import:PTS525")
      (libsource (lib "eagle-import") (part "BUTTON_TEMP_ON"))
    )
    (comp (ref "S4")
      (value "SWITCH_SPDT_SLIDE_SPARKFUN_SMD")
      (footprint "eagle-import:SPARKFUNSWITCH")
      (libsource (lib "eagle-import") (part "SWITCH_SPDT_SLIDE_SPARKFUN_SMD"))
    )
    (comp (ref "TP1")
      (value "GPIO2")
      (footprint "eagle-import:PAD.03X.05")
      (libsource (lib "eagle-import") (part "TEST-POINT3X5"))
    )
    (comp (ref "TP2")
      (value "REV3V3")
      (footprint "eagle-import:PAD.03X.05")
      (libsource (lib "eagle-import") (part "TEST-POINT3X5"))
    )
    (comp (ref "TP3")
      (value "RTS3V3")
      (footprint "eagle-import:PAD.03X.05")
      (libsource (lib "eagle-import") (part "TEST-POINT3X5"))
    )
    (comp (ref "TP4")
      (value "LTS3V3")
      (footprint "eagle-import:PAD.03X.05")
      (libsource (lib "eagle-import") (part "TEST-POINT3X5"))
    )
    (comp (ref "TP5")
      (value "BRK3V3")
      (footprint "eagle-import:PAD.03X.05")
      (libsource (lib "eagle-import") (part "TEST-POINT3X5"))
    )
    (comp (ref "TP6")
      (value "REV12V")
      (footprint "eagle-import:PAD.03X.05")
      (libsource (lib "eagle-import") (part "TEST-POINT3X5"))
    )
    (comp (ref "TP7")
      (value "RTS12V")
      (footprint "eagle-import:PAD.03X.05")
      (libsource (lib "eagle-import") (part "TEST-POINT3X5"))
    )
    (comp (ref "TP8")
      (value "LTS12V")
      (footprint "eagle-import:PAD.03X.05")
      (libsource (lib "eagle-import") (part "TEST-POINT3X5"))
    )
    (comp (ref "TP9")
      (value "BRK12V")
      (footprint "eagle-import:PAD.03X.05")
      (libsource (lib "eagle-import") (part "TEST-POINT3X5"))
    )
    (comp (ref "TP10")
      (value "VRAW")
      (footprint "eagle-import:PAD.03X.05")
      (libsource (lib "eagle-import") (part "TEST-POINT3X5"))
    )
    (comp (ref "TP11")
      (value "VREVP")
      (footprint "eagle-import:PAD.03X.05")
      (libsource (lib "eagle-import") (part "TEST-POINT3X5"))
    )
    (comp (ref "TP12")
      (value "VBATT")
      (footprint "eagle-import:PAD.03X.05")
      (libsource (lib "eagle-import") (part "TEST-POINT3X5"))
    )
    (comp (ref "TP13")
      (value "5V")
      (footprint "eagle-import:PAD.03X.05")
      (libsource (lib "eagle-import") (part "TEST-POINT3X5"))
    )
    (comp (ref "TP14")
      (value "3V3")
      (footprint "eagle-import:PAD.03X.05")
      (libsource (lib "eagle-import") (part "TEST-POINT3X5"))
    )
    (comp (ref "TP15")
      (value "GND")
      (footprint "eagle-import:PAD.03X.05")
      (libsource (lib "eagle-import") (part "TEST-POINT3X5"))
    )
    (comp (ref "TP16")
      (value "S2CK3V3")
      (footprint "eagle-import:PAD.03X.05")
      (libsource (lib "eagle-import") (part "TEST-POINT3X5"))
    )
    (comp (ref "TP17")
      (value "S2CK5V")
      (footprint "eagle-import:PAD.03X.05")
      (libsource (lib "eagle-import") (part "TEST-POINT3X5"))
    )
    (comp (ref "TP18")
      (value "S2MO3V3")
      (footprint "eagle-import:PAD.03X.05")
      (libsource (lib "eagle-import") (part "TEST-POINT3X5"))
    )
    (comp (ref "TP19")
      (value "S2MO5V")
      (footprint "eagle-import:PAD.03X.05")
      (libsource (lib "eagle-import") (part "TEST-POINT3X5"))
    )
    (comp (ref "TP20")
      (value "S3CK3V3")
      (footprint "eagle-import:PAD.03X.05")
      (libsource (lib "eagle-import") (part "TEST-POINT3X5"))
    )
    (comp (ref "TP21")
      (value "S3CK5V")
      (footprint "eagle-import:PAD.03X.05")
      (libsource (lib "eagle-import") (part "TEST-POINT3X5"))
    )
    (comp (ref "TP22")
      (value "S3MO3V3")
      (footprint "eagle-import:PAD.03X.05")
      (libsource (lib "eagle-import") (part "TEST-POINT3X5"))
    )
    (comp (ref "TP23")
      (value "S3MO5V")
      (footprint "eagle-import:PAD.03X.05")
      (libsource (lib "eagle-import") (part "TEST-POINT3X5"))
    )
    (comp (ref "TP24")
      (value "S4CK3V3")
      (footprint "eagle-import:PAD.03X.05")
      (libsource (lib "eagle-import") (part "TEST-POINT3X5"))
    )
    (comp (ref "TP25")
      (value "S4CK5V")
      (footprint "eagle-import:PAD.03X.05")
      (libsource (lib "eagle-import") (part "TEST-POINT3X5"))
    )
    (comp (ref "TP26")
      (value "S4MO3V3")
      (footprint "eagle-import:PAD.03X.05")
      (libsource (lib "eagle-import") (part "TEST-POINT3X5"))
    )
    (comp (ref "TP27")
      (value "S4MO5V")
      (footprint "eagle-import:PAD.03X.05")
      (libsource (lib "eagle-import") (part "TEST-POINT3X5"))
    )
    (comp (ref "TP28")
      (value "S5CK3V3")
      (footprint "eagle-import:PAD.03X.05")
      (libsource (lib "eagle-import") (part "TEST-POINT3X5"))
    )
    (comp (ref "TP29")
      (value "S5CK5V")
      (footprint "eagle-import:PAD.03X.05")
      (libsource (lib "eagle-import") (part "TEST-POINT3X5"))
    )
    (comp (ref "TP30")
      (value "S5MO3V3")
      (footprint "eagle-import:PAD.03X.05")
      (libsource (lib "eagle-import") (part "TEST-POINT3X5"))
    )
    (comp (ref "TP31")
      (value "S5MO5V")
      (footprint "eagle-import:PAD.03X.05")
      (libsource (lib "eagle-import") (part "TEST-POINT3X5"))
    )
    (comp (ref "TP32")
      (value "S1MISO")
      (footprint "eagle-import:PAD.03X.05")
      (libsource (lib "eagle-import") (part "TEST-POINT3X5"))
    )
    (comp (ref "TP33")
      (value "S1MOSI")
      (footprint "eagle-import:PAD.03X.05")
      (libsource (lib "eagle-import") (part "TEST-POINT3X5"))
    )
    (comp (ref "TP34")
      (value "S1CLK")
      (footprint "eagle-import:PAD.03X.05")
      (libsource (lib "eagle-import") (part "TEST-POINT3X5"))
    )
    (comp (ref "TP35")
      (value "GND")
      (footprint "eagle-import:PAD.03X.05")
      (libsource (lib "eagle-import") (part "TEST-POINT3X5"))
    )
    (comp (ref "TP36")
      (value "CSMAG")
      (footprint "eagle-import:PAD.03X.05")
      (libsource (lib "eagle-import") (part "TEST-POINT3X5"))
    )
    (comp (ref "TP37")
      (value "CSACC")
      (footprint "eagle-import:PAD.03X.05")
      (libsource (lib "eagle-import") (part "TEST-POINT3X5"))
    )
    (comp (ref "TP38")
      (value "CSGYRO")
      (footprint "eagle-import:PAD.03X.05")
      (libsource (lib "eagle-import") (part "TEST-POINT3X5"))
    )
    (comp (ref "TP39")
      (value "U2RX")
      (footprint "eagle-import:PAD.03X.05")
      (libsource (lib "eagle-import") (part "TEST-POINT3X5"))
    )
    (comp (ref "TP40")
      (value "U2TX")
      (footprint "eagle-import:PAD.03X.05")
      (libsource (lib "eagle-import") (part "TEST-POINT3X5"))
    )
    (comp (ref "TP41")
      (value "U2CTS")
      (footprint "eagle-import:PAD.03X.05")
      (libsource (lib "eagle-import") (part "TEST-POINT3X5"))
    )
    (comp (ref "TP42")
      (value "U1RX")
      (footprint "eagle-import:PAD.03X.05")
      (libsource (lib "eagle-import") (part "TEST-POINT3X5"))
    )
    (comp (ref "TP43")
      (value "U1TX")
      (footprint "eagle-import:PAD.03X.05")
      (libsource (lib "eagle-import") (part "TEST-POINT3X5"))
    )
    (comp (ref "TP44")
      (value "GND")
      (footprint "eagle-import:PAD.03X.05")
      (libsource (lib "eagle-import") (part "TEST-POINT3X5"))
    )
    (comp (ref "TP45")
      (value "U6RX")
      (footprint "eagle-import:PAD.03X.05")
      (libsource (lib "eagle-import") (part "TEST-POINT3X5"))
    )
    (comp (ref "TP46")
      (value "U6TX")
      (footprint "eagle-import:PAD.03X.05")
      (libsource (lib "eagle-import") (part "TEST-POINT3X5"))
    )
    (comp (ref "TP47")
      (value "I2C1DA")
      (footprint "eagle-import:PAD.03X.05")
      (libsource (lib "eagle-import") (part "TEST-POINT3X5"))
    )
    (comp (ref "TP48")
      (value "I2C1CL")
      (footprint "eagle-import:PAD.03X.05")
      (libsource (lib "eagle-import") (part "TEST-POINT3X5"))
    )
    (comp (ref "TP49")
      (value "BFR")
      (footprint "eagle-import:PAD.03X.05")
      (libsource (lib "eagle-import") (part "TEST-POINT3X5"))
    )
    (comp (ref "TP50")
      (value "BSBR")
      (footprint "eagle-import:PAD.03X.05")
      (libsource (lib "eagle-import") (part "TEST-POINT3X5"))
    )
    (comp (ref "TP51")
      (value "BSBM")
      (footprint "eagle-import:PAD.03X.05")
      (libsource (lib "eagle-import") (part "TEST-POINT3X5"))
    )
    (comp (ref "TP52")
      (value "BAD")
      (footprint "eagle-import:PAD.03X.05")
      (libsource (lib "eagle-import") (part "TEST-POINT3X5"))
    )
    (comp (ref "TP53")
      (value "GND")
      (footprint "eagle-import:PAD.03X.05")
      (libsource (lib "eagle-import") (part "TEST-POINT3X5"))
    )
    (comp (ref "TP54")
      (value "GND")
      (footprint "eagle-import:PAD.03X.05")
      (libsource (lib "eagle-import") (part "TEST-POINT3X5"))
    )
    (comp (ref "TP55")
      (value "SWCLK")
      (footprint "eagle-import:PAD.03X.05")
      (libsource (lib "eagle-import") (part "TEST-POINT3X5"))
    )
    (comp (ref "TP56")
      (value "SWDIO")
      (footprint "eagle-import:PAD.03X.05")
      (libsource (lib "eagle-import") (part "TEST-POINT3X5"))
    )
    (comp (ref "TP57")
      (value "RESETL")
      (footprint "eagle-import:PAD.03X.05")
      (libsource (lib "eagle-import") (part "TEST-POINT3X5"))
    )
    (comp (ref "TP58")
      (value "BOOT0")
      (footprint "eagle-import:PAD.03X.05")
      (libsource (lib "eagle-import") (part "TEST-POINT3X5"))
    )
    (comp (ref "TP59")
      (value "UD1L")
      (footprint "eagle-import:PAD.03X.05")
      (libsource (lib "eagle-import") (part "TEST-POINT3X5"))
    )
    (comp (ref "TP60")
      (value "UD2L")
      (footprint "eagle-import:PAD.03X.05")
      (libsource (lib "eagle-import") (part "TEST-POINT3X5"))
    )
    (comp (ref "TP61")
      (value "USBDP")
      (footprint "eagle-import:PAD.03X.05")
      (libsource (lib "eagle-import") (part "TEST-POINT3X5"))
    )
    (comp (ref "TP62")
      (value "USBDM")
      (footprint "eagle-import:PAD.03X.05")
      (libsource (lib "eagle-import") (part "TEST-POINT3X5"))
    )
    (comp (ref "TP63")
      (value "SDD0")
      (footprint "eagle-import:PAD.03X.05")
      (libsource (lib "eagle-import") (part "TEST-POINT3X5"))
    )
    (comp (ref "TP64")
      (value "SDD1")
      (footprint "eagle-import:PAD.03X.05")
      (libsource (lib "eagle-import") (part "TEST-POINT3X5"))
    )
    (comp (ref "TP65")
      (value "SDD2")
      (footprint "eagle-import:PAD.03X.05")
      (libsource (lib "eagle-import") (part "TEST-POINT3X5"))
    )
    (comp (ref "TP66")
      (value "SDD3")
      (footprint "eagle-import:PAD.03X.05")
      (libsource (lib "eagle-import") (part "TEST-POINT3X5"))
    )
    (comp (ref "TP67")
      (value "SDCK")
      (footprint "eagle-import:PAD.03X.05")
      (libsource (lib "eagle-import") (part "TEST-POINT3X5"))
    )
    (comp (ref "TP68")
      (value "SDCMD")
      (footprint "eagle-import:PAD.03X.05")
      (libsource (lib "eagle-import") (part "TEST-POINT3X5"))
    )
    (comp (ref "TP70")
      (value "CMPO")
      (footprint "eagle-import:PAD.03X.05")
      (libsource (lib "eagle-import") (part "TEST-POINT3X5"))
    )
    (comp (ref "TP71")
      (value "VRAW")
      (footprint "eagle-import:PAD.03X.05")
      (libsource (lib "eagle-import") (part "TEST-POINT3X5"))
    )
    (comp (ref "TP72")
      (value "L")
      (footprint "eagle-import:PAD.03X.05")
      (libsource (lib "eagle-import") (part "TEST-POINT3X5"))
    )
    (comp (ref "TP73")
      (value "HSCL")
      (footprint "eagle-import:PAD.03X.05")
      (libsource (lib "eagle-import") (part "TEST-POINT3X5"))
    )
    (comp (ref "TP74")
      (value "MSCL")
      (footprint "eagle-import:PAD.03X.05")
      (libsource (lib "eagle-import") (part "TEST-POINT3X5"))
    )
    (comp (ref "TP75")
      (value "J-")
      (footprint "eagle-import:PAD.03X.05")
      (libsource (lib "eagle-import") (part "TEST-POINT3X5"))
    )
    (comp (ref "TP76")
      (value "K")
      (footprint "eagle-import:PAD.03X.05")
      (libsource (lib "eagle-import") (part "TEST-POINT3X5"))
    )
    (comp (ref "TP77")
      (value "HSCH")
      (footprint "eagle-import:PAD.03X.05")
      (libsource (lib "eagle-import") (part "TEST-POINT3X5"))
    )
    (comp (ref "TP78")
      (value "GND")
      (footprint "eagle-import:PAD.03X.05")
      (libsource (lib "eagle-import") (part "TEST-POINT3X5"))
    )
    (comp (ref "TP79")
      (value "KTX")
      (footprint "eagle-import:PAD.03X.05")
      (libsource (lib "eagle-import") (part "TEST-POINT3X5"))
    )
    (comp (ref "TP80")
      (value "MSCH")
      (footprint "eagle-import:PAD.03X.05")
      (libsource (lib "eagle-import") (part "TEST-POINT3X5"))
    )
    (comp (ref "TP81")
      (value "J+")
      (footprint "eagle-import:PAD.03X.05")
      (libsource (lib "eagle-import") (part "TEST-POINT3X5"))
    )
    (comp (ref "TP82")
      (value "SWC")
      (footprint "eagle-import:PAD.03X.05")
      (libsource (lib "eagle-import") (part "TEST-POINT3X5"))
    )
    (comp (ref "TP83")
      (value "LTX")
      (footprint "eagle-import:PAD.03X.05")
      (libsource (lib "eagle-import") (part "TEST-POINT3X5"))
    )
    (comp (ref "TP84")
      (value "VBISO")
      (footprint "eagle-import:PAD.03X.05")
      (libsource (lib "eagle-import") (part "TEST-POINT3X5"))
    )
    (comp (ref "TP85")
      (value "ISORL")
      (footprint "eagle-import:PAD.03X.05")
      (libsource (lib "eagle-import") (part "TEST-POINT3X5"))
    )
    (comp (ref "TP86")
      (value "HSCT")
      (footprint "eagle-import:PAD.03X.05")
      (libsource (lib "eagle-import") (part "TEST-POINT3X5"))
    )
    (comp (ref "TP87")
      (value "HSCR")
      (footprint "eagle-import:PAD.03X.05")
      (libsource (lib "eagle-import") (part "TEST-POINT3X5"))
    )
    (comp (ref "TP88")
      (value "SWCT")
      (footprint "eagle-import:PAD.03X.05")
      (libsource (lib "eagle-import") (part "TEST-POINT3X5"))
    )
    (comp (ref "TP89")
      (value "SWCR")
      (footprint "eagle-import:PAD.03X.05")
      (libsource (lib "eagle-import") (part "TEST-POINT3X5"))
    )
    (comp (ref "TP90")
      (value "MSCT")
      (footprint "eagle-import:PAD.03X.05")
      (libsource (lib "eagle-import") (part "TEST-POINT3X5"))
    )
    (comp (ref "TP91")
      (value "MSCR")
      (footprint "eagle-import:PAD.03X.05")
      (libsource (lib "eagle-import") (part "TEST-POINT3X5"))
    )
    (comp (ref "TP92")
      (value "SWCM0")
      (footprint "eagle-import:PAD.03X.05")
      (libsource (lib "eagle-import") (part "TEST-POINT3X5"))
    )
    (comp (ref "TP93")
      (value "SWCM1")
      (footprint "eagle-import:PAD.03X.05")
      (libsource (lib "eagle-import") (part "TEST-POINT3X5"))
    )
    (comp (ref "TP94")
      (value "VBSW")
      (footprint "eagle-import:PAD.03X.05")
      (libsource (lib "eagle-import") (part "TEST-POINT3X5"))
    )
    (comp (ref "TP95")
      (value "5VSW")
      (footprint "eagle-import:PAD.03X.05")
      (libsource (lib "eagle-import") (part "TEST-POINT3X5"))
    )
    (comp (ref "TP96")
      (value "3V3SW")
      (footprint "eagle-import:PAD.03X.05")
      (libsource (lib "eagle-import") (part "TEST-POINT3X5"))
    )
    (comp (ref "TP97")
      (value "PSL")
      (footprint "eagle-import:PAD.03X.05")
      (libsource (lib "eagle-import") (part "TEST-POINT3X5"))
    )
    (comp (ref "TP98")
      (value "OSD")
      (footprint "eagle-import:PAD.03X.05")
      (libsource (lib "eagle-import") (part "TEST-POINT3X5"))
    )
    (comp (ref "TP99")
      (value "HAD")
      (footprint "eagle-import:PAD.03X.05")
      (libsource (lib "eagle-import") (part "TEST-POINT3X5"))
    )
    (comp (ref "TP100")
      (value "OAD")
      (footprint "eagle-import:PAD.03X.05")
      (libsource (lib "eagle-import") (part "TEST-POINT3X5"))
    )
    (comp (ref "TP101")
      (value "OAI")
      (footprint "eagle-import:PAD.03X.05")
      (libsource (lib "eagle-import") (part "TEST-POINT3X5"))
    )
    (comp (ref "TP102")
      (value "J-TL")
      (footprint "eagle-import:PAD.03X.05")
      (libsource (lib "eagle-import") (part "TEST-POINT3X5"))
    )
    (comp (ref "TP103")
      (value "J+T")
      (footprint "eagle-import:PAD.03X.05")
      (libsource (lib "eagle-import") (part "TEST-POINT3X5"))
    )
    (comp (ref "TP104")
      (value "VJ")
      (footprint "eagle-import:PAD.03X.05")
      (libsource (lib "eagle-import") (part "TEST-POINT3X5"))
    )
    (comp (ref "TP105")
      (value "VPWR")
      (footprint "eagle-import:PAD.03X.05")
      (libsource (lib "eagle-import") (part "TEST-POINT3X5"))
    )
    (comp (ref "TP106")
      (value "PWMR")
      (footprint "eagle-import:PAD.03X.05")
      (libsource (lib "eagle-import") (part "TEST-POINT3X5"))
    )
    (comp (ref "TP107")
      (value "J+VHL")
      (footprint "eagle-import:PAD.03X.05")
      (libsource (lib "eagle-import") (part "TEST-POINT3X5"))
    )
    (comp (ref "TP108")
      (value "DCDC5")
      (footprint "eagle-import:PAD.03X.05")
      (libsource (lib "eagle-import") (part "TEST-POINT3X5"))
    )
    (comp (ref "TP109")
      (value "USB5")
      (footprint "eagle-import:PAD.03X.05")
      (libsource (lib "eagle-import") (part "TEST-POINT3X5"))
    )
    (comp (ref "TP110")
      (value "GND")
      (footprint "eagle-import:PAD.03X.05")
      (libsource (lib "eagle-import") (part "TEST-POINT3X5"))
    )
    (comp (ref "TP111")
      (value "GND")
      (footprint "eagle-import:PAD.03X.05")
      (libsource (lib "eagle-import") (part "TEST-POINT3X5"))
    )
    (comp (ref "TP112")
      (value "GND")
      (footprint "eagle-import:PAD.03X.05")
      (libsource (lib "eagle-import") (part "TEST-POINT3X5"))
    )
    (comp (ref "TP113")
      (value "GND")
      (footprint "eagle-import:PAD.03X.05")
      (libsource (lib "eagle-import") (part "TEST-POINT3X5"))
    )
    (comp (ref "U1")
      (value "IC_VREF_3PIN-NCP51460SN33T1G")
      (footprint "eagle-import:SOT23-3")
      (libsource (lib "eagle-import") (part "IC_VREF_3PIN-NCP51460SN33T1G"))
    )
    (comp (ref "U2")
      (value "IC_OP-AMP_DUAL-OPA1662AIDR")
      (footprint "eagle-import:SOIC-8")
      (libsource (lib "eagle-import") (part "IC_OP-AMP_DUAL-OPA1662AIDR"))
    )
    (comp (ref "U3")
      (value "DCDC_5V")
      (footprint "eagle-import:CUI-5")
      (libsource (lib "eagle-import") (part "REG-DCDC_5V"))
    )
    (comp (ref "U6")
      (value "3.3VREG_USB_POWER")
      (footprint "eagle-import:SOT23-5")
      (libsource (lib "eagle-import") (part "REG-LINEAR_4-RT9080-33GJ5_INHIBIT_IS_ACTUALLY_ENABLE!"))
    )
    (comp (ref "U7")
      (value "STN2120")
      (footprint "eagle-import:QFN-44")
      (libsource (lib "eagle-import") (part "IC_OBD_INTERPSTN2120"))
    )
    (comp (ref "U9")
      (value "IC_OBD_TXRX_CAN_MCP2551")
      (footprint "eagle-import:SOIC-8@1")
      (libsource (lib "eagle-import") (part "IC_OBD_TXRX_CAN_MCP2551"))
    )
    (comp (ref "U10")
      (value "IC_OBD_TXRX_CAN_MCP2551")
      (footprint "eagle-import:SOIC-8@1")
      (libsource (lib "eagle-import") (part "IC_OBD_TXRX_CAN_MCP2551"))
    )
    (comp (ref "U11")
      (value "IC_OBD_TXRX_SWCAN-TH8056A")
      (footprint "eagle-import:SOIC-8")
      (libsource (lib "eagle-import") (part "IC_OBD_TXRX_SWCAN-TH8056A"))
    )
    (comp (ref "U12")
      (value "IC_OP-AMP_DUAL-OPA1662AIDR")
      (footprint "eagle-import:SOIC-8")
      (libsource (lib "eagle-import") (part "IC_OP-AMP_DUAL-OPA1662AIDR"))
    )
    (comp (ref "U13")
      (value "REG_LINEAR_3LM317LD")
      (footprint "eagle-import:SOIC-8")
      (libsource (lib "eagle-import") (part "REG_LINEAR_3LM317LD"))
    )
    (comp (ref "U14")
      (value "IC_OP-AMP_DUAL-OPA1662AIDR")
      (footprint "eagle-import:SOIC-8")
      (libsource (lib "eagle-import") (part "IC_OP-AMP_DUAL-OPA1662AIDR"))
    )
    (comp (ref "U15")
      (value "ACC")
      (footprint "eagle-import:LGA-16")
      (libsource (lib "eagle-import") (part "SEN_ACC-LIS3DH"))
    )
    (comp (ref "U16")
      (value "GYRO")
      (footprint "eagle-import:QFN-24")
      (libsource (lib "eagle-import") (part "SEN_GYRO-FXAS21002C"))
    )
    (comp (ref "U17")
      (value "MAG")
      (footprint "eagle-import:VFLGA-12")
      (libsource (lib "eagle-import") (part "SEN_MAG-LIS3MDL"))
    )
    (comp (ref "U18")
      (value "Bluetooth UART")
      (footprint "eagle-import:RN42")
      (libsource (lib "eagle-import") (part "RN4X"))
    )
    (comp (ref "U19")
      (value "STM32F411")
      (footprint "eagle-import:LQFP-64")
      (libsource (lib "eagle-import") (part "IC_MICRO_STM32F411-RXTX"))
    )
    (comp (ref "X1")
      (value "XTAL-FA238")
      (footprint "eagle-import:FA-238")
      (libsource (lib "eagle-import") (part "XTAL-FA238"))
    )
    (comp (ref "X2")
      (value "16MHz")
      (footprint "eagle-import:FA-238")
      (libsource (lib "eagle-import") (part "XTAL-FA238"))
    )
  )
  (nets
    (net (code "1") (name "/3V3_SW") (class "Default")
      (node (ref "Q11") (pin "2") (pinfunction "S_2") (pintype "bidirectional"))
      (node (ref "TP96") (pin "P$1") (pinfunction "1_P$1") (pintype "bidirectional"))
    )
    (net (code "2") (name "/5V_SW") (class "Default")
      (node (ref "C14") (pin "1") (pinfunction "1_1") (pintype "passive"))
      (node (ref "C15") (pin "1") (pinfunction "1_1") (pintype "passive"))
      (node (ref "D13") (pin "A") (pinfunction "A_A") (pintype "passive"))
      (node (ref "Q10") (pin "2") (pinfunction "S_2") (pintype "bidirectional"))
      (node (ref "R48") (pin "2") (pinfunction "2_2") (pintype "passive"))
      (node (ref "R54") (pin "2") (pinfunction "2_2") (pintype "passive"))
      (node (ref "R56") (pin "2") (pinfunction "2_2") (pintype "passive"))
      (node (ref "R57") (pin "2") (pinfunction "2_2") (pintype "passive"))
      (node (ref "R66") (pin "2") (pinfunction "2_2") (pintype "passive"))
      (node (ref "R67") (pin "2") (pinfunction "2_2") (pintype "passive"))
      (node (ref "TP95") (pin "P$1") (pinfunction "1_P$1") (pintype "bidirectional"))
      (node (ref "U10") (pin "3") (pinfunction "VDD_3") (pintype "bidirectional"))
      (node (ref "U9") (pin "3") (pinfunction "VDD_3") (pintype "bidirectional"))
    )
    (net (code "3") (name "/5V_USB") (class "Default")
      (node (ref "D7") (pin "A") (pinfunction "A_A") (pintype "passive"))
      (node (ref "F3") (pin "1") (pinfunction "1_1") (pintype "bidirectional"))
      (node (ref "TP109") (pin "P$1") (pinfunction "1_P$1") (pintype "bidirectional"))
    )
    (net (code "4") (name "/BLU_AUTO_DISC") (class "Default")
      (node (ref "J4") (pin "1") (pinfunction "1_1") (pintype "bidirectional"))
      (node (ref "R73") (pin "2") (pinfunction "2_2") (pintype "passive"))
      (node (ref "TP52") (pin "P$1") (pinfunction "1_P$1") (pintype "bidirectional"))
      (node (ref "U18") (pin "P$20") (pinfunction "20.GPIO3_P$20") (pintype "bidirectional"))
    )
    (net (code "5") (name "/BLU_CONN_STAT_LED") (class "Default")
      (node (ref "R68") (pin "1") (pinfunction "1_1") (pintype "passive"))
      (node (ref "U18") (pin "P$21") (pinfunction "21.GPIO5_P$21") (pintype "bidirectional"))
    )
    (net (code "6") (name "/BLU_FACT_RESET") (class "Default")
      (node (ref "J1") (pin "1") (pinfunction "1_1") (pintype "bidirectional"))
      (node (ref "R70") (pin "2") (pinfunction "2_2") (pintype "passive"))
      (node (ref "TP49") (pin "P$1") (pinfunction "1_P$1") (pintype "bidirectional"))
      (node (ref "U18") (pin "P$22") (pinfunction "22.GPIO4_P$22") (pintype "bidirectional"))
    )
    (net (code "7") (name "/BLU_SET_BR") (class "Default")
      (node (ref "J2") (pin "1") (pinfunction "1_1") (pintype "bidirectional"))
      (node (ref "R71") (pin "2") (pinfunction "2_2") (pintype "passive"))
      (node (ref "TP50") (pin "P$1") (pinfunction "1_P$1") (pintype "bidirectional"))
      (node (ref "U18") (pin "P$4") (pinfunction "4.GPIO7_P$4") (pintype "bidirectional"))
    )
    (net (code "8") (name "/BLU_SET_BT_MAST") (class "Default")
      (node (ref "J3") (pin "1") (pinfunction "1_1") (pintype "bidirectional"))
      (node (ref "R72") (pin "2") (pinfunction "2_2") (pintype "passive"))
      (node (ref "TP51") (pin "P$1") (pinfunction "1_P$1") (pintype "bidirectional"))
      (node (ref "U18") (pin "P$3") (pinfunction "3.GPIO6_P$3") (pintype "bidirectional"))
    )
    (net (code "9") (name "/BLU_SPI_CS") (class "Default")
      (node (ref "U18") (pin "P$23") (pinfunction "23.SPI_CSB_P$23") (pintype "bidirectional"))
    )
    (net (code "10") (name "/BLU_SPI_MISO") (class "Default")
      (node (ref "U18") (pin "P$24") (pinfunction "24.SPI_MISO_P$24") (pintype "bidirectional"))
    )
    (net (code "11") (name "/BLU_SPI_MOSI") (class "Default")
      (node (ref "U18") (pin "P$2") (pinfunction "2.SPI_MOSI_P$2") (pintype "bidirectional"))
    )
    (net (code "12") (name "/BLU_SPI_SCLK") (class "Default")
      (node (ref "U18") (pin "P$6") (pinfunction "6.SPI_CLOCK_P$6") (pintype "bidirectional"))
    )
    (net (code "13") (name "/BLU_TXRX_ACT_LED") (class "Default")
      (node (ref "R69") (pin "1") (pinfunction "1_1") (pintype "passive"))
      (node (ref "U18") (pin "P$31") (pinfunction "31.GPIO8_P$31") (pintype "bidirectional"))
    )
    (net (code "14") (name "/BOOT0") (class "Default")
      (node (ref "J8") (pin "1") (pinfunction "1_1") (pintype "bidirectional"))
      (node (ref "R90") (pin "2") (pinfunction "2_2") (pintype "passive"))
      (node (ref "TP58") (pin "P$1") (pinfunction "1_P$1") (pintype "bidirectional"))
      (node (ref "U19") (pin "P$60") (pinfunction "BOOT0_P$60") (pintype "bidirectional"))
    )
    (net (code "15") (name "/BRK_3V3") (class "Default")
      (node (ref "Q1") (pin "2") (pinfunction "S_2") (pintype "bidirectional"))
      (node (ref "R1") (pin "1") (pinfunction "1_1") (pintype "passive"))
      (node (ref "TP5") (pin "P$1") (pinfunction "1_P$1") (pintype "bidirectional"))
      (node (ref "U19") (pin "P$51") (pinfunction "PC10_P$51") (pintype "bidirectional"))
    )
    (net (code "16") (name "/BRK_12V") (class "Default")
      (node (ref "M11") (pin "P$1") (pinfunction "1_P$1") (pintype "bidirectional"))
      (node (ref "Q1") (pin "3") (pinfunction "D_3") (pintype "bidirectional"))
      (node (ref "R2") (pin "1") (pinfunction "1_1") (pintype "passive"))
      (node (ref "TP9") (pin "P$1") (pinfunction "1_P$1") (pintype "bidirectional"))
    )
    (net (code "17") (name "/COMP_OUT") (class "Default")
      (node (ref "Q6") (pin "1") (pinfunction "G_1") (pintype "bidirectional"))
      (node (ref "TP70") (pin "P$1") (pinfunction "1_P$1") (pintype "bidirectional"))
      (node (ref "U2") (pin "1") (pinfunction "OUTA_1") (pintype "output"))
    )
    (net (code "18") (name "/DCDC5V") (class "Default")
      (node (ref "C4") (pin "PIN_2_+") (pinfunction "+_PIN_2_+") (pintype "passive"))
      (node (ref "C5") (pin "1") (pinfunction "1_1") (pintype "passive"))
      (node (ref "D3") (pin "A") (pinfunction "A_A") (pintype "passive"))
      (node (ref "R9") (pin "2") (pinfunction "2_2") (pintype "passive"))
      (node (ref "TP108") (pin "P$1") (pinfunction "1_P$1") (pintype "bidirectional"))
      (node (ref "U3") (pin "5") (pinfunction "VOUT_5") (pintype "bidirectional"))
    )
    (net (code "19") (name "/HS_CAN_HI") (class "Default")
      (node (ref "D8") (pin "2") (pinfunction "C1_2") (pintype "passive"))
      (node (ref "M10") (pin "6") (pinfunction "6.HS_CAN_HI_6") (pintype "bidirectional"))
      (node (ref "R27") (pin "2") (pinfunction "2_2") (pintype "passive"))
      (node (ref "TP77") (pin "P$1") (pinfunction "1_P$1") (pintype "bidirectional"))
      (node (ref "U9") (pin "7") (pinfunction "CANH_7") (pintype "bidirectional"))
    )
    (net (code "20") (name "/HS_CAN_LO") (class "Default")
      (node (ref "D8") (pin "1") (pinfunction "C2_1") (pintype "passive"))
      (node (ref "M10") (pin "14") (pinfunction "14.HS_CAN_LO_14") (pintype "bidirectional"))
      (node (ref "R28") (pin "2") (pinfunction "2_2") (pintype "passive"))
      (node (ref "TP73") (pin "P$1") (pinfunction "1_P$1") (pintype "bidirectional"))
      (node (ref "U9") (pin "8") (pinfunction "CANL_8") (pintype "bidirectional"))
    )
    (net (code "21") (name "/HS_CAN_RX") (class "Default")
      (node (ref "R57") (pin "1") (pinfunction "1_1") (pintype "passive"))
      (node (ref "R61") (pin "1") (pinfunction "1_1") (pintype "passive"))
      (node (ref "TP87") (pin "P$1") (pinfunction "1_P$1") (pintype "bidirectional"))
      (node (ref "U7") (pin "P$10") (pinfunction "10.HS_CAN_RX/GP8_P$10") (pintype "bidirectional"))
      (node (ref "U9") (pin "4") (pinfunction "ROUT_4") (pintype "bidirectional"))
    )
    (net (code "22") (name "/HS_CAN_TX") (class "Default")
      (node (ref "R56") (pin "1") (pinfunction "1_1") (pintype "passive"))
      (node (ref "R59") (pin "1") (pinfunction "1_1") (pintype "passive"))
      (node (ref "TP86") (pin "P$1") (pinfunction "1_P$1") (pintype "bidirectional"))
      (node (ref "U7") (pin "P$8") (pinfunction "8.HS_CAN_TX/GP9_P$8") (pintype "bidirectional"))
      (node (ref "U9") (pin "1") (pinfunction "TIN_1") (pintype "bidirectional"))
    )
    (net (code "23") (name "/I2C1_SCL") (class "Default")
      (node (ref "M7") (pin "P$1") (pinfunction "1_P$1") (pintype "bidirectional"))
      (node (ref "R100") (pin "2") (pinfunction "2_2") (pintype "passive"))
      (node (ref "TP48") (pin "P$1") (pinfunction "1_P$1") (pintype "bidirectional"))
      (node (ref "U19") (pin "P$58") (pinfunction "PB6_P$58") (pintype "bidirectional"))
    )
    (net (code "24") (name "/I2C1_SDA") (class "Default")
      (node (ref "M7") (pin "P$2") (pinfunction "2_P$2") (pintype "bidirectional"))
      (node (ref "R99") (pin "2") (pinfunction "2_2") (pintype "passive"))
      (node (ref "TP47") (pin "P$1") (pinfunction "1_P$1") (pintype "bidirectional"))
      (node (ref "U19") (pin "P$59") (pinfunction "PB7_P$59") (pintype "bidirectional"))
    )
    (net (code "25") (name "/ISO_K_TX_L") (class "Default")
      (node (ref "R35") (pin "1") (pinfunction "1_1") (pintype "passive"))
      (node (ref "TP79") (pin "P$1") (pinfunction "1_P$1") (pintype "bidirectional"))
      (node (ref "U7") (pin "P$43") (pinfunction "43.ISO_K_TX_L/GP6_P$43") (pintype "bidirectional"))
    )
    (net (code "26") (name "/ISO_L_TX_L") (class "Default")
      (node (ref "R36") (pin "1") (pinfunction "1_1") (pintype "passive"))
      (node (ref "TP83") (pin "P$1") (pinfunction "1_P$1") (pintype "bidirectional"))
      (node (ref "U7") (pin "P$44") (pinfunction "44.ISO_L_TX_L/GP7_P$44") (pintype "bidirectional"))
    )
    (net (code "27") (name "/ISO_RX_L") (class "Default")
      (node (ref "R40") (pin "1") (pinfunction "1_1") (pintype "passive"))
      (node (ref "TP85") (pin "P$1") (pinfunction "1_P$1") (pintype "bidirectional"))
      (node (ref "U12") (pin "1") (pinfunction "OUTA_1") (pintype "output"))
      (node (ref "U7") (pin "P$21") (pinfunction "21.ISO_RX_L/GP5_P$21") (pintype "bidirectional"))
    )
    (net (code "28") (name "/J1850_BUS+") (class "Default")
      (node (ref "D11") (pin "C") (pinfunction "C_C") (pintype "passive"))
      (node (ref "M10") (pin "2") (pinfunction "2.J1850_PWM/VPW_POS_2") (pintype "bidirectional"))
      (node (ref "R44") (pin "1") (pinfunction "1_1") (pintype "passive"))
      (node (ref "R47") (pin "2") (pinfunction "2_2") (pintype "passive"))
      (node (ref "R53") (pin "1") (pinfunction "1_1") (pintype "passive"))
      (node (ref "TP81") (pin "P$1") (pinfunction "1_P$1") (pintype "bidirectional"))
    )
    (net (code "29") (name "/J1850_BUS+_TX") (class "Default")
      (node (ref "Q16") (pin "1") (pinfunction "G_1") (pintype "bidirectional"))
      (node (ref "R52") (pin "2") (pinfunction "2_2") (pintype "passive"))
      (node (ref "TP103") (pin "P$1") (pinfunction "1_P$1") (pintype "bidirectional"))
      (node (ref "U7") (pin "P$24") (pinfunction "24.J1850_BUS+_TX/GP2_P$24") (pintype "bidirectional"))
    )
    (net (code "30") (name "/J1850_BUS+_VH_L") (class "Default")
      (node (ref "Q15") (pin "1") (pinfunction "G_1") (pintype "bidirectional"))
      (node (ref "TP107") (pin "P$1") (pinfunction "1_P$1") (pintype "bidirectional"))
      (node (ref "U7") (pin "P$25") (pinfunction "25.J1850_BUS+_VH_L/GP4_P$25") (pintype "bidirectional"))
    )
    (net (code "31") (name "/J1850_BUS-") (class "Default")
      (node (ref "M10") (pin "10") (pinfunction "10.J1850_PWM_NEG_10") (pintype "bidirectional"))
      (node (ref "Q18") (pin "3") (pinfunction "D_3") (pintype "bidirectional"))
      (node (ref "R45") (pin "1") (pinfunction "1_1") (pintype "passive"))
      (node (ref "R55") (pin "1") (pinfunction "1_1") (pintype "passive"))
      (node (ref "TP75") (pin "P$1") (pinfunction "1_P$1") (pintype "bidirectional"))
    )
    (net (code "32") (name "/J1850_BUS-_TX_L") (class "Default")
      (node (ref "Q18") (pin "1") (pinfunction "G_1") (pintype "bidirectional"))
      (node (ref "R54") (pin "1") (pinfunction "1_1") (pintype "passive"))
      (node (ref "TP102") (pin "P$1") (pinfunction "1_P$1") (pintype "bidirectional"))
      (node (ref "U7") (pin "P$33") (pinfunction "33.J1850_BUS-_TX_L/GP3_P$33") (pintype "bidirectional"))
    )
    (net (code "33") (name "/K_LINE") (class "Default")
      (node (ref "M10") (pin "7") (pinfunction "7.KLINE_7") (pintype "bidirectional"))
      (node (ref "Q13") (pin "3") (pinfunction "C_3") (pintype "passive"))
      (node (ref "R33") (pin "1") (pinfunction "1_1") (pintype "passive"))
      (node (ref "R39") (pin "1") (pinfunction "1_1") (pintype "passive"))
      (node (ref "TP76") (pin "P$1") (pinfunction "1_P$1") (pintype "bidirectional"))
    )
    (net (code "34") (name "/LTS_3V3") (class "Default")
      (node (ref "Q2") (pin "2") (pinfunction "S_2") (pintype "bidirectional"))
      (node (ref "R3") (pin "1") (pinfunction "1_1") (pintype "passive"))
      (node (ref "TP4") (pin "P$1") (pinfunction "1_P$1") (pintype "bidirectional"))
      (node (ref "U19") (pin "P$56") (pinfunction "PB4_P$56") (pintype "bidirectional"))
    )
    (net (code "35") (name "/LTS_12V") (class "Default")
      (node (ref "M11") (pin "P$2") (pinfunction "2_P$2") (pintype "bidirectional"))
      (node (ref "Q2") (pin "3") (pinfunction "D_3") (pintype "bidirectional"))
      (node (ref "R4") (pin "1") (pinfunction "1_1") (pintype "passive"))
      (node (ref "TP8") (pin "P$1") (pinfunction "1_P$1") (pintype "bidirectional"))
    )
    (net (code "36") (name "/L_LINE") (class "Default")
      (node (ref "M10") (pin "15") (pinfunction "15.LLINE_15") (pintype "bidirectional"))
      (node (ref "Q14") (pin "3") (pinfunction "C_3") (pintype "passive"))
      (node (ref "R34") (pin "1") (pinfunction "1_1") (pintype "passive"))
      (node (ref "TP72") (pin "P$1") (pinfunction "1_P$1") (pintype "bidirectional"))
    )
    (net (code "37") (name "/MS_CAN_HI") (class "Default")
      (node (ref "D9") (pin "2") (pinfunction "C1_2") (pintype "passive"))
      (node (ref "M10") (pin "3") (pinfunction "3.MS_CAN_HI_3") (pintype "bidirectional"))
      (node (ref "R29") (pin "2") (pinfunction "2_2") (pintype "passive"))
      (node (ref "TP80") (pin "P$1") (pinfunction "1_P$1") (pintype "bidirectional"))
      (node (ref "U10") (pin "7") (pinfunction "CANH_7") (pintype "bidirectional"))
    )
    (net (code "38") (name "/MS_CAN_LO") (class "Default")
      (node (ref "D9") (pin "1") (pinfunction "C2_1") (pintype "passive"))
      (node (ref "M10") (pin "11") (pinfunction "11.MS_CAN_LO_11") (pintype "bidirectional"))
      (node (ref "R30") (pin "2") (pinfunction "2_2") (pintype "passive"))
      (node (ref "TP74") (pin "P$1") (pinfunction "1_P$1") (pintype "bidirectional"))
      (node (ref "U10") (pin "8") (pinfunction "CANL_8") (pintype "bidirectional"))
    )
    (net (code "39") (name "/MS_CAN_RX") (class "Default")
      (node (ref "R62") (pin "1") (pinfunction "1_1") (pintype "passive"))
      (node (ref "TP91") (pin "P$1") (pinfunction "1_P$1") (pintype "bidirectional"))
      (node (ref "U10") (pin "4") (pinfunction "ROUT_4") (pintype "bidirectional"))
      (node (ref "U7") (pin "P$11") (pinfunction "11.MS_CAN_RX/GP10_P$11") (pintype "bidirectional"))
    )
    (net (code "40") (name "/MS_CAN_TX") (class "Default")
      (node (ref "R60") (pin "1") (pinfunction "1_1") (pintype "passive"))
      (node (ref "TP90") (pin "P$1") (pinfunction "1_P$1") (pintype "bidirectional"))
      (node (ref "U10") (pin "1") (pinfunction "TIN_1") (pintype "bidirectional"))
      (node (ref "U7") (pin "P$9") (pinfunction "9.MS_CAN_TX/GP11_P$9") (pintype "bidirectional"))
    )
    (net (code "41") (name "/OBD_ANALOG_IN") (class "Default")
      (node (ref "C7") (pin "2") (pinfunction "2_2") (pintype "passive"))
      (node (ref "D20") (pin "C") (pinfunction "C_C") (pintype "passive"))
      (node (ref "D21") (pin "A") (pinfunction "A_A") (pintype "passive"))
      (node (ref "R18") (pin "1") (pinfunction "1_1") (pintype "passive"))
      (node (ref "R19") (pin "2") (pinfunction "2_2") (pintype "passive"))
      (node (ref "TP101") (pin "P$1") (pinfunction "1_P$1") (pintype "bidirectional"))
      (node (ref "U7") (pin "P$19") (pinfunction "19.ANALOG_IN/GP17_P$19") (pintype "bidirectional"))
    )
    (net (code "42") (name "/OBD_HOST_ACT_LED") (class "Default")
      (node (ref "R22") (pin "1") (pinfunction "1_1") (pintype "passive"))
      (node (ref "TP99") (pin "P$1") (pinfunction "1_P$1") (pintype "bidirectional"))
      (node (ref "U7") (pin "P$13") (pinfunction "13.LED_HOST_ACT_L/GP24_P$13") (pintype "bidirectional"))
    )
    (net (code "43") (name "/OBD_OBD_ACT_LED") (class "Default")
      (node (ref "J7") (pin "P$2") (pinfunction "2_P$2") (pintype "bidirectional"))
      (node (ref "R21") (pin "1") (pinfunction "1_1") (pintype "passive"))
      (node (ref "R63") (pin "2") (pinfunction "2_2") (pintype "passive"))
      (node (ref "TP100") (pin "P$1") (pinfunction "1_P$1") (pintype "bidirectional"))
      (node (ref "U7") (pin "P$12") (pinfunction "12.LED_OBD_ACT_L/RST_NVM_L/GP22_P$12") (pintype "bidirectional"))
    )
    (net (code "44") (name "/OBD_STATUS_LED") (class "Default")
      (node (ref "R20") (pin "2") (pinfunction "2_2") (pintype "passive"))
      (node (ref "TP98") (pin "P$1") (pinfunction "1_P$1") (pintype "bidirectional"))
      (node (ref "U7") (pin "P$14") (pinfunction "14.LED_STATUS/GP26_P$14") (pintype "bidirectional"))
    )
    (net (code "45") (name "/PWM_RX") (class "Default")
      (node (ref "R46") (pin "1") (pinfunction "1_1") (pintype "passive"))
      (node (ref "TP106") (pin "P$1") (pinfunction "1_P$1") (pintype "bidirectional"))
      (node (ref "U14") (pin "1") (pinfunction "OUTA_1") (pintype "output"))
      (node (ref "U7") (pin "P$23") (pinfunction "23.PWM_RX/GP0_P$23") (pintype "bidirectional"))
    )
    (net (code "46") (name "/PWR_SAVE_L") (class "Default")
      (node (ref "Q12") (pin "5") (pinfunction "G_5") (pintype "bidirectional"))
      (node (ref "Q8") (pin "4") (pinfunction "G_4") (pintype "bidirectional"))
      (node (ref "R23") (pin "1") (pinfunction "1_1") (pintype "passive"))
      (node (ref "TP97") (pin "P$1") (pinfunction "1_P$1") (pintype "bidirectional"))
      (node (ref "U7") (pin "P$32") (pinfunction "32.PWR_CTRL/GP19_P$32") (pintype "bidirectional"))
    )
    (net (code "47") (name "/RESET_L") (class "Default")
      (node (ref "C44") (pin "1") (pinfunction "1_1") (pintype "passive"))
      (node (ref "R13") (pin "1") (pinfunction "1_1") (pintype "passive"))
      (node (ref "S1") (pin "P$3") (pinfunction "2_P$3") (pintype "passive"))
      (node (ref "S1") (pin "P$4") (pinfunction "2_P$4") (pintype "passive"))
      (node (ref "TP57") (pin "P$1") (pinfunction "1_P$1") (pintype "bidirectional"))
      (node (ref "U18") (pin "P$5") (pinfunction "5.RESET_P$5") (pintype "bidirectional"))
      (node (ref "U19") (pin "P$7") (pinfunction "NRST_P$7") (pintype "bidirectional"))
      (node (ref "U7") (pin "P$18") (pinfunction "18.RESET_L_P$18") (pintype "bidirectional"))
    )
    (net (code "48") (name "/REV_3V3") (class "Default")
      (node (ref "Q4") (pin "2") (pinfunction "S_2") (pintype "bidirectional"))
      (node (ref "R7") (pin "1") (pinfunction "1_1") (pintype "passive"))
      (node (ref "TP2") (pin "P$1") (pinfunction "1_P$1") (pintype "bidirectional"))
      (node (ref "U19") (pin "P$62") (pinfunction "PB9_P$62") (pintype "bidirectional"))
    )
    (net (code "49") (name "/REV_12V") (class "Default")
      (node (ref "M11") (pin "P$4") (pinfunction "4_P$4") (pintype "bidirectional"))
      (node (ref "Q4") (pin "3") (pinfunction "D_3") (pintype "bidirectional"))
      (node (ref "R8") (pin "1") (pinfunction "1_1") (pintype "passive"))
      (node (ref "TP6") (pin "P$1") (pinfunction "1_P$1") (pintype "bidirectional"))
    )
    (net (code "50") (name "/RTS_3V3") (class "Default")
      (node (ref "Q3") (pin "2") (pinfunction "S_2") (pintype "bidirectional"))
      (node (ref "R5") (pin "1") (pinfunction "1_1") (pintype "passive"))
      (node (ref "TP3") (pin "P$1") (pinfunction "1_P$1") (pintype "bidirectional"))
      (node (ref "U19") (pin "P$57") (pinfunction "PB5_P$57") (pintype "bidirectional"))
    )
    (net (code "51") (name "/RTS_12V") (class "Default")
      (node (ref "M11") (pin "P$3") (pinfunction "3_P$3") (pintype "bidirectional"))
      (node (ref "Q3") (pin "3") (pinfunction "D_3") (pintype "bidirectional"))
      (node (ref "R6") (pin "1") (pinfunction "1_1") (pintype "passive"))
      (node (ref "TP7") (pin "P$1") (pinfunction "1_P$1") (pintype "bidirectional"))
    )
    (net (code "52") (name "/SDIO_CK") (class "Default")
      (node (ref "M1") (pin "P$5") (pinfunction "CLK_P$5") (pintype "bidirectional"))
      (node (ref "TP67") (pin "P$1") (pinfunction "1_P$1") (pintype "bidirectional"))
      (node (ref "U19") (pin "P$36") (pinfunction "PB15_P$36") (pintype "bidirectional"))
    )
    (net (code "53") (name "/SDIO_CMD") (class "Default")
      (node (ref "M1") (pin "P$3") (pinfunction "CMD_P$3") (pintype "bidirectional"))
      (node (ref "TP68") (pin "P$1") (pinfunction "1_P$1") (pintype "bidirectional"))
      (node (ref "U19") (pin "P$54") (pinfunction "PD2_P$54") (pintype "bidirectional"))
    )
    (net (code "54") (name "/SDIO_D0") (class "Default")
      (node (ref "M1") (pin "P$7") (pinfunction "DAT0_P$7") (pintype "bidirectional"))
      (node (ref "TP63") (pin "P$1") (pinfunction "1_P$1") (pintype "bidirectional"))
      (node (ref "U19") (pin "P$39") (pinfunction "PC8_P$39") (pintype "bidirectional"))
    )
    (net (code "55") (name "/SDIO_D1") (class "Default")
      (node (ref "M1") (pin "P$8") (pinfunction "DAT1_P$8") (pintype "bidirectional"))
      (node (ref "TP64") (pin "P$1") (pinfunction "1_P$1") (pintype "bidirectional"))
      (node (ref "U19") (pin "P$40") (pinfunction "PC9_P$40") (pintype "bidirectional"))
    )
    (net (code "56") (name "/SDIO_D2") (class "Default")
      (node (ref "M1") (pin "P$1") (pinfunction "DAT2_P$1") (pintype "bidirectional"))
      (node (ref "TP65") (pin "P$1") (pinfunction "1_P$1") (pintype "bidirectional"))
      (node (ref "U19") (pin "P$42") (pinfunction "PA9_P$42") (pintype "bidirectional"))
    )
    (net (code "57") (name "/SDIO_D3") (class "Default")
      (node (ref "M1") (pin "P$2") (pinfunction "CD/DAT3_P$2") (pintype "bidirectional"))
      (node (ref "TP66") (pin "P$1") (pinfunction "1_P$1") (pintype "bidirectional"))
      (node (ref "U19") (pin "P$52") (pinfunction "PC11_P$52") (pintype "bidirectional"))
    )
    (net (code "58") (name "/SD_CD_L") (class "Default")
      (node (ref "M1") (pin "CD_SW2") (pinfunction "CD_SW2_CD_SW2") (pintype "bidirectional"))
      (node (ref "R94") (pin "2") (pinfunction "2_2") (pintype "passive"))
      (node (ref "U19") (pin "P$10") (pinfunction "PC2_P$10") (pintype "bidirectional"))
    )
    (net (code "59") (name "/SLEEP_L") (class "Default")
      (node (ref "R64") (pin "1") (pinfunction "1_1") (pintype "passive"))
      (node (ref "U7") (pin "P$27") (pinfunction "27.SLEEP_L/GP18_P$27") (pintype "bidirectional"))
    )
    (net (code "60") (name "/SPI1_CS_ACC") (class "Default")
      (node (ref "TP37") (pin "P$1") (pinfunction "1_P$1") (pintype "bidirectional"))
      (node (ref "U15") (pin "P$8") (pinfunction "8.CS_P$8") (pintype "bidirectional"))
      (node (ref "U19") (pin "P$35") (pinfunction "PB14_P$35") (pintype "bidirectional"))
    )
    (net (code "61") (name "/SPI1_CS_GYRO") (class "Default")
      (node (ref "TP38") (pin "P$1") (pinfunction "1_P$1") (pintype "bidirectional"))
      (node (ref "U16") (pin "P$17") (pinfunction "17.SPI_CS_B_P$17") (pintype "bidirectional"))
      (node (ref "U19") (pin "P$27") (pinfunction "PB1_P$27") (pintype "bidirectional"))
    )
    (net (code "62") (name "/SPI1_CS_MAG") (class "Default")
      (node (ref "J5") (pin "2") (pinfunction "2_2") (pintype "bidirectional"))
      (node (ref "TP36") (pin "P$1") (pinfunction "1_P$1") (pintype "bidirectional"))
      (node (ref "U17") (pin "P$10") (pinfunction "CS_P$10") (pintype "bidirectional"))
      (node (ref "U19") (pin "P$28") (pinfunction "PB2_P$28") (pintype "bidirectional"))
    )
    (net (code "63") (name "/SPI1_MISO") (class "Default")
      (node (ref "TP32") (pin "P$1") (pinfunction "1_P$1") (pintype "bidirectional"))
      (node (ref "U15") (pin "P$7") (pinfunction "7.SDO/SA0_P$7") (pintype "bidirectional"))
      (node (ref "U16") (pin "P$13") (pinfunction "13.SA0/MISO_P$13") (pintype "bidirectional"))
      (node (ref "U17") (pin "P$9") (pinfunction "SD0/SA1_P$9") (pintype "bidirectional"))
      (node (ref "U19") (pin "P$22") (pinfunction "PA6_P$22") (pintype "bidirectional"))
    )
    (net (code "64") (name "/SPI1_MOSI") (class "Default")
      (node (ref "TP33") (pin "P$1") (pinfunction "1_P$1") (pintype "bidirectional"))
      (node (ref "U15") (pin "P$6") (pinfunction "6.SDA/SDI/SDO_P$6") (pintype "bidirectional"))
      (node (ref "U16") (pin "P$12") (pinfunction "12.SDA/MOSI/SPI_DATA_P$12") (pintype "bidirectional"))
      (node (ref "U17") (pin "P$11") (pinfunction "SDA/SDI/SDO_P$11") (pintype "bidirectional"))
      (node (ref "U19") (pin "P$23") (pinfunction "PA7_P$23") (pintype "bidirectional"))
    )
    (net (code "65") (name "/SPI1_SCK") (class "Default")
      (node (ref "TP34") (pin "P$1") (pinfunction "1_P$1") (pintype "bidirectional"))
      (node (ref "U15") (pin "P$4") (pinfunction "4.SCL/SPC_P$4") (pintype "bidirectional"))
      (node (ref "U16") (pin "P$11") (pinfunction "11.SCL/SCLK_P$11") (pintype "bidirectional"))
      (node (ref "U17") (pin "P$1") (pinfunction "SCL/SPC_P$1") (pintype "bidirectional"))
      (node (ref "U19") (pin "P$21") (pinfunction "PA5_P$21") (pintype "bidirectional"))
    )
    (net (code "66") (name "/SPI2_MOSI_3V3") (class "Default")
      (node (ref "Q20") (pin "2") (pinfunction "S_2") (pintype "bidirectional"))
      (node (ref "R76") (pin "1") (pinfunction "1_1") (pintype "passive"))
      (node (ref "TP18") (pin "P$1") (pinfunction "1_P$1") (pintype "bidirectional"))
      (node (ref "U19") (pin "P$11") (pinfunction "PC3_P$11") (pintype "bidirectional"))
    )
    (net (code "67") (name "/SPI2_MOSI_5V") (class "Default")
      (node (ref "M3") (pin "P$1") (pinfunction "1_P$1") (pintype "bidirectional"))
      (node (ref "Q20") (pin "3") (pinfunction "D_3") (pintype "bidirectional"))
      (node (ref "R77") (pin "1") (pinfunction "1_1") (pintype "passive"))
      (node (ref "TP19") (pin "P$1") (pinfunction "1_P$1") (pintype "bidirectional"))
    )
    (net (code "68") (name "/SPI2_SCK_3V3") (class "Default")
      (node (ref "Q19") (pin "2") (pinfunction "S_2") (pintype "bidirectional"))
      (node (ref "R74") (pin "1") (pinfunction "1_1") (pintype "passive"))
      (node (ref "TP16") (pin "P$1") (pinfunction "1_P$1") (pintype "bidirectional"))
      (node (ref "U19") (pin "P$29") (pinfunction "PB10_P$29") (pintype "bidirectional"))
    )
    (net (code "69") (name "/SPI2_SCK_5V") (class "Default")
      (node (ref "M3") (pin "P$3") (pinfunction "3_P$3") (pintype "bidirectional"))
      (node (ref "Q19") (pin "3") (pinfunction "D_3") (pintype "bidirectional"))
      (node (ref "R75") (pin "1") (pinfunction "1_1") (pintype "passive"))
      (node (ref "TP17") (pin "P$1") (pinfunction "1_P$1") (pintype "bidirectional"))
    )
    (net (code "70") (name "/SPI3_MOSI_3V3") (class "Default")
      (node (ref "Q22") (pin "2") (pinfunction "S_2") (pintype "bidirectional"))
      (node (ref "R80") (pin "1") (pinfunction "1_1") (pintype "passive"))
      (node (ref "TP22") (pin "P$1") (pinfunction "1_P$1") (pintype "bidirectional"))
      (node (ref "U19") (pin "P$53") (pinfunction "PC12_P$53") (pintype "bidirectional"))
    )
    (net (code "71") (name "/SPI3_MOSI_5V") (class "Default")
      (node (ref "M4") (pin "P$1") (pinfunction "1_P$1") (pintype "bidirectional"))
      (node (ref "Q22") (pin "3") (pinfunction "D_3") (pintype "bidirectional"))
      (node (ref "R81") (pin "1") (pinfunction "1_1") (pintype "passive"))
      (node (ref "TP23") (pin "P$1") (pinfunction "1_P$1") (pintype "bidirectional"))
    )
    (net (code "72") (name "/SPI3_SCK_3V3") (class "Default")
      (node (ref "Q21") (pin "2") (pinfunction "S_2") (pintype "bidirectional"))
      (node (ref "R78") (pin "1") (pinfunction "1_1") (pintype "passive"))
      (node (ref "TP20") (pin "P$1") (pinfunction "1_P$1") (pintype "bidirectional"))
      (node (ref "U19") (pin "P$33") (pinfunction "PB12_P$33") (pintype "bidirectional"))
    )
    (net (code "73") (name "/SPI3_SCK_5V") (class "Default")
      (node (ref "M4") (pin "P$3") (pinfunction "3_P$3") (pintype "bidirectional"))
      (node (ref "Q21") (pin "3") (pinfunction "D_3") (pintype "bidirectional"))
      (node (ref "R79") (pin "1") (pinfunction "1_1") (pintype "passive"))
      (node (ref "TP21") (pin "P$1") (pinfunction "1_P$1") (pintype "bidirectional"))
    )
    (net (code "74") (name "/SPI4_MOSI_3V3") (class "Default")
      (node (ref "Q24") (pin "2") (pinfunction "S_2") (pintype "bidirectional"))
      (node (ref "R84") (pin "1") (pinfunction "1_1") (pintype "passive"))
      (node (ref "TP26") (pin "P$1") (pinfunction "1_P$1") (pintype "bidirectional"))
      (node (ref "U19") (pin "P$15") (pinfunction "PA1_P$15") (pintype "bidirectional"))
    )
    (net (code "75") (name "/SPI4_MOSI_5V") (class "Default")
      (node (ref "M5") (pin "P$1") (pinfunction "1_P$1") (pintype "bidirectional"))
      (node (ref "Q24") (pin "3") (pinfunction "D_3") (pintype "bidirectional"))
      (node (ref "R85") (pin "1") (pinfunction "1_1") (pintype "passive"))
      (node (ref "TP27") (pin "P$1") (pinfunction "1_P$1") (pintype "bidirectional"))
    )
    (net (code "76") (name "/SPI4_SCK_3V3") (class "Default")
      (node (ref "Q23") (pin "2") (pinfunction "S_2") (pintype "bidirectional"))
      (node (ref "R82") (pin "1") (pinfunction "1_1") (pintype "passive"))
      (node (ref "TP24") (pin "P$1") (pinfunction "1_P$1") (pintype "bidirectional"))
      (node (ref "U19") (pin "P$34") (pinfunction "PB13_P$34") (pintype "bidirectional"))
    )
    (net (code "77") (name "/SPI4_SCK_5V") (class "Default")
      (node (ref "M5") (pin "P$3") (pinfunction "3_P$3") (pintype "bidirectional"))
      (node (ref "Q23") (pin "3") (pinfunction "D_3") (pintype "bidirectional"))
      (node (ref "R83") (pin "1") (pinfunction "1_1") (pintype "passive"))
      (node (ref "TP25") (pin "P$1") (pinfunction "1_P$1") (pintype "bidirectional"))
    )
    (net (code "78") (name "/SPI5_MOSI_3V3") (class "Default")
      (node (ref "Q26") (pin "2") (pinfunction "S_2") (pintype "bidirectional"))
      (node (ref "R88") (pin "1") (pinfunction "1_1") (pintype "passive"))
      (node (ref "TP30") (pin "P$1") (pinfunction "1_P$1") (pintype "bidirectional"))
      (node (ref "U19") (pin "P$61") (pinfunction "PB8_P$61") (pintype "bidirectional"))
    )
    (net (code "79") (name "/SPI5_MOSI_5V") (class "Default")
      (node (ref "M6") (pin "P$1") (pinfunction "1_P$1") (pintype "bidirectional"))
      (node (ref "Q26") (pin "3") (pinfunction "D_3") (pintype "bidirectional"))
      (node (ref "R89") (pin "1") (pinfunction "1_1") (pintype "passive"))
      (node (ref "TP31") (pin "P$1") (pinfunction "1_P$1") (pintype "bidirectional"))
    )
    (net (code "80") (name "/SPI5_SCK_3V3") (class "Default")
      (node (ref "Q25") (pin "2") (pinfunction "S_2") (pintype "bidirectional"))
      (node (ref "R86") (pin "1") (pinfunction "1_1") (pintype "passive"))
      (node (ref "TP28") (pin "P$1") (pinfunction "1_P$1") (pintype "bidirectional"))
      (node (ref "U19") (pin "P$26") (pinfunction "PB0_P$26") (pintype "bidirectional"))
    )
    (net (code "81") (name "/SPI5_SCK_5V") (class "Default")
      (node (ref "M6") (pin "P$3") (pinfunction "3_P$3") (pintype "bidirectional"))
      (node (ref "Q25") (pin "3") (pinfunction "D_3") (pintype "bidirectional"))
      (node (ref "R87") (pin "1") (pinfunction "1_1") (pintype "passive"))
      (node (ref "TP29") (pin "P$1") (pinfunction "1_P$1") (pintype "bidirectional"))
    )
    (net (code "82") (name "/SWCLK") (class "Default")
      (node (ref "R12") (pin "1") (pinfunction "1_1") (pintype "passive"))
      (node (ref "R97") (pin "1") (pinfunction "1_1") (pintype "passive"))
      (node (ref "TP55") (pin "P$1") (pinfunction "1_P$1") (pintype "bidirectional"))
      (node (ref "U19") (pin "P$49") (pinfunction "PA14_P$49") (pintype "bidirectional"))
    )
    (net (code "83") (name "/SWDIO") (class "Default")
      (node (ref "R92") (pin "1") (pinfunction "1_1") (pintype "passive"))
      (node (ref "R98") (pin "1") (pinfunction "1_1") (pintype "passive"))
      (node (ref "TP56") (pin "P$1") (pinfunction "1_P$1") (pintype "bidirectional"))
      (node (ref "U19") (pin "P$46") (pinfunction "PA13_P$46") (pintype "bidirectional"))
    )
    (net (code "84") (name "/SW_CAN") (class "Default")
      (node (ref "C16") (pin "2") (pinfunction "2_2") (pintype "passive"))
      (node (ref "M10") (pin "1") (pinfunction "1.SWCAN_1") (pintype "bidirectional"))
      (node (ref "R103") (pin "P$2") (pinfunction "2_P$2") (pintype "passive"))
      (node (ref "R32") (pin "2") (pinfunction "2_2") (pintype "passive"))
      (node (ref "TP82") (pin "P$1") (pinfunction "1_P$1") (pintype "bidirectional"))
      (node (ref "U11") (pin "7") (pinfunction "CANH_7") (pintype "bidirectional"))
    )
    (net (code "85") (name "/SW_CAN_LOAD") (class "Default")
      (node (ref "Q27") (pin "1") (pinfunction "G_1") (pintype "bidirectional"))
      (node (ref "R104") (pin "2") (pinfunction "2_2") (pintype "passive"))
      (node (ref "U7") (pin "P$34") (pinfunction "34.SW_CAN_LOAD/GP16_P$34") (pintype "bidirectional"))
    )
    (net (code "86") (name "/SW_CAN_MODE0") (class "Default")
      (node (ref "R67") (pin "1") (pinfunction "1_1") (pintype "passive"))
      (node (ref "TP92") (pin "P$1") (pinfunction "1_P$1") (pintype "bidirectional"))
      (node (ref "U11") (pin "2") (pinfunction "MODE0_2") (pintype "bidirectional"))
      (node (ref "U7") (pin "P$35") (pinfunction "35.SW_CAN_MODE0/GP14_P$35") (pintype "bidirectional"))
    )
    (net (code "87") (name "/SW_CAN_MODE1") (class "Default")
      (node (ref "R66") (pin "1") (pinfunction "1_1") (pintype "passive"))
      (node (ref "TP93") (pin "P$1") (pinfunction "1_P$1") (pintype "bidirectional"))
      (node (ref "U11") (pin "3") (pinfunction "MODE1_3") (pintype "bidirectional"))
      (node (ref "U7") (pin "P$36") (pinfunction "36.SW_CAN_MODE1/GP15_P$36") (pintype "bidirectional"))
    )
    (net (code "88") (name "/SW_CAN_RX") (class "Default")
      (node (ref "R31") (pin "1") (pinfunction "1_1") (pintype "passive"))
      (node (ref "TP89") (pin "P$1") (pinfunction "1_P$1") (pintype "bidirectional"))
      (node (ref "U11") (pin "4") (pinfunction "ROUT_4") (pintype "bidirectional"))
      (node (ref "U7") (pin "P$42") (pinfunction "42.SW_CAN_RX/GP12_P$42") (pintype "bidirectional"))
    )
    (net (code "89") (name "/SW_CAN_TX") (class "Default")
      (node (ref "R65") (pin "1") (pinfunction "1_1") (pintype "passive"))
      (node (ref "TP88") (pin "P$1") (pinfunction "1_P$1") (pintype "bidirectional"))
      (node (ref "U11") (pin "1") (pinfunction "TIN_1") (pintype "bidirectional"))
      (node (ref "U7") (pin "P$41") (pinfunction "41.SW_CAN_TX/GP13_P$41") (pintype "bidirectional"))
    )
    (net (code "90") (name "/US1") (class "Default")
      (node (ref "R102") (pin "2") (pinfunction "2_2") (pintype "passive"))
      (node (ref "S3") (pin "P$1") (pinfunction "1_P$1") (pintype "passive"))
      (node (ref "S3") (pin "P$2") (pinfunction "1_P$2") (pintype "passive"))
      (node (ref "U19") (pin "P$20") (pinfunction "PA4_P$20") (pintype "bidirectional"))
    )
    (net (code "91") (name "/US2") (class "Default")
      (node (ref "R101") (pin "2") (pinfunction "2_2") (pintype "passive"))
      (node (ref "S2") (pin "P$1") (pinfunction "1_P$1") (pintype "passive"))
      (node (ref "S2") (pin "P$2") (pinfunction "1_P$2") (pintype "passive"))
      (node (ref "U19") (pin "P$24") (pinfunction "PC4_P$24") (pintype "bidirectional"))
    )
    (net (code "92") (name "/USART1_RX") (class "Default")
      (node (ref "R58") (pin "1") (pinfunction "1_1") (pintype "passive"))
      (node (ref "TP42") (pin "P$1") (pinfunction "1_P$1") (pintype "bidirectional"))
      (node (ref "U19") (pin "P$55") (pinfunction "PB3_P$55") (pintype "bidirectional"))
      (node (ref "U7") (pin "P$4") (pinfunction "4.UART_TX_P$4") (pintype "bidirectional"))
    )
    (net (code "93") (name "/USART1_TX") (class "Default")
      (node (ref "TP43") (pin "P$1") (pinfunction "1_P$1") (pintype "bidirectional"))
      (node (ref "U19") (pin "P$50") (pinfunction "PA15_P$50") (pintype "bidirectional"))
      (node (ref "U7") (pin "P$5") (pinfunction "5.UART_RX_P$5") (pintype "bidirectional"))
    )
    (net (code "94") (name "/USART2_CTS") (class "Default")
      (node (ref "TP41") (pin "P$1") (pinfunction "1_P$1") (pintype "bidirectional"))
      (node (ref "U18") (pin "P$15") (pinfunction "15.UART_RTS_P$15") (pintype "bidirectional"))
      (node (ref "U19") (pin "P$14") (pinfunction "PA0_P$14") (pintype "bidirectional"))
    )
    (net (code "95") (name "/USART2_RX") (class "Default")
      (node (ref "TP39") (pin "P$1") (pinfunction "1_P$1") (pintype "bidirectional"))
      (node (ref "U18") (pin "P$13") (pinfunction "13.UART_RX_P$13") (pintype "bidirectional"))
      (node (ref "U19") (pin "P$17") (pinfunction "PA3_P$17") (pintype "bidirectional"))
    )
    (net (code "96") (name "/USART2_TX") (class "Default")
      (node (ref "TP40") (pin "P$1") (pinfunction "1_P$1") (pintype "bidirectional"))
      (node (ref "U18") (pin "P$14") (pinfunction "14.UART_TX_P$14") (pintype "bidirectional"))
      (node (ref "U19") (pin "P$16") (pinfunction "PA2_P$16") (pintype "bidirectional"))
    )
    (net (code "97") (name "/USART6_RX") (class "Default")
      (node (ref "M8") (pin "P$1") (pinfunction "1_P$1") (pintype "bidirectional"))
      (node (ref "TP45") (pin "P$1") (pinfunction "1_P$1") (pintype "bidirectional"))
      (node (ref "U19") (pin "P$38") (pinfunction "PC7_P$38") (pintype "bidirectional"))
    )
    (net (code "98") (name "/USART6_TX") (class "Default")
      (node (ref "M8") (pin "P$2") (pinfunction "2_P$2") (pintype "bidirectional"))
      (node (ref "TP46") (pin "P$1") (pinfunction "1_P$1") (pintype "bidirectional"))
      (node (ref "U19") (pin "P$37") (pinfunction "PC6_P$37") (pintype "bidirectional"))
    )
    (net (code "99") (name "/USB_OTG_FS_DM") (class "Default")
      (node (ref "M2") (pin "2") (pinfunction "D-_2") (pintype "bidirectional"))
      (node (ref "TP62") (pin "P$1") (pinfunction "1_P$1") (pintype "bidirectional"))
      (node (ref "U19") (pin "P$44") (pinfunction "PA11_P$44") (pintype "bidirectional"))
    )
    (net (code "100") (name "/USB_OTG_FS_DP") (class "Default")
      (node (ref "M2") (pin "3") (pinfunction "D+_3") (pintype "bidirectional"))
      (node (ref "TP61") (pin "P$1") (pinfunction "1_P$1") (pintype "bidirectional"))
      (node (ref "U19") (pin "P$45") (pinfunction "PA12_P$45") (pintype "bidirectional"))
    )
    (net (code "101") (name "/USER_LED1L") (class "Default")
      (node (ref "R95") (pin "1") (pinfunction "1_1") (pintype "passive"))
      (node (ref "TP59") (pin "P$1") (pinfunction "1_P$1") (pintype "bidirectional"))
      (node (ref "U19") (pin "P$8") (pinfunction "PC0_P$8") (pintype "bidirectional"))
    )
    (net (code "102") (name "/USER_LED2L") (class "Default")
      (node (ref "R96") (pin "1") (pinfunction "1_1") (pintype "passive"))
      (node (ref "TP60") (pin "P$1") (pinfunction "1_P$1") (pintype "bidirectional"))
      (node (ref "U19") (pin "P$9") (pinfunction "PC1_P$9") (pintype "bidirectional"))
    )
    (net (code "103") (name "/VPW_RX") (class "Default")
      (node (ref "R50") (pin "1") (pinfunction "1_1") (pintype "passive"))
      (node (ref "TP105") (pin "P$1") (pinfunction "1_P$1") (pintype "bidirectional"))
      (node (ref "U14") (pin "7") (pinfunction "OUTB_7") (pintype "output"))
      (node (ref "U7") (pin "P$22") (pinfunction "22.VPW_RX/GP1_P$22") (pintype "bidirectional"))
    )
    (net (code "104") (name "/V_BACKUP") (class "Default")
      (node (ref "U19") (pin "P$1") (pinfunction "VBAT_P$1") (pintype "bidirectional"))
    )
    (net (code "105") (name "/V_BATT_ISO") (class "Default")
      (node (ref "Q12") (pin "1") (pinfunction "D_1") (pintype "bidirectional"))
      (node (ref "Q12") (pin "2") (pinfunction "D_2") (pintype "bidirectional"))
      (node (ref "Q12") (pin "3") (pinfunction "D_3") (pintype "bidirectional"))
      (node (ref "Q12") (pin "4") (pinfunction "D_4") (pintype "bidirectional"))
      (node (ref "R33") (pin "2") (pinfunction "2_2") (pintype "passive"))
      (node (ref "R34") (pin "2") (pinfunction "2_2") (pintype "passive"))
      (node (ref "TP84") (pin "P$1") (pinfunction "1_P$1") (pintype "bidirectional"))
    )
    (net (code "106") (name "/V_BATT_RAW") (class "Default")
      (node (ref "M10") (pin "16") (pinfunction "16.+12V_ALWAYS_ON_16") (pintype "bidirectional"))
      (node (ref "M9") (pin "P$3") (pinfunction "2_P$3") (pintype "bidirectional"))
      (node (ref "Q5") (pin "1") (pinfunction "D_1") (pintype "bidirectional"))
      (node (ref "Q5") (pin "2") (pinfunction "D_2") (pintype "bidirectional"))
      (node (ref "Q5") (pin "3") (pinfunction "D_3") (pintype "bidirectional"))
      (node (ref "Q5") (pin "4") (pinfunction "D_4") (pintype "bidirectional"))
      (node (ref "TP10") (pin "P$1") (pinfunction "1_P$1") (pintype "bidirectional"))
      (node (ref "TP71") (pin "P$1") (pinfunction "1_P$1") (pintype "bidirectional"))
    )
    (net (code "107") (name "/V_BATT_REVP") (class "Default")
      (node (ref "C1") (pin "1") (pinfunction "1_1") (pintype "passive"))
      (node (ref "F2") (pin "1") (pinfunction "1_1") (pintype "bidirectional"))
      (node (ref "Q7") (pin "1") (pinfunction "D_1") (pintype "bidirectional"))
      (node (ref "Q7") (pin "2") (pinfunction "D_2") (pintype "bidirectional"))
      (node (ref "Q7") (pin "3") (pinfunction "D_3") (pintype "bidirectional"))
      (node (ref "Q7") (pin "4") (pinfunction "D_4") (pintype "bidirectional"))
      (node (ref "TP11") (pin "P$1") (pinfunction "1_P$1") (pintype "bidirectional"))
    )
    (net (code "108") (name "/V_BATT_SW") (class "Default")
      (node (ref "C18") (pin "2") (pinfunction "2_2") (pintype "passive"))
      (node (ref "Q9") (pin "2") (pinfunction "S_2") (pintype "bidirectional"))
      (node (ref "R37") (pin "2") (pinfunction "2_2") (pintype "passive"))
      (node (ref "TP94") (pin "P$1") (pinfunction "1_P$1") (pintype "bidirectional"))
      (node (ref "U13") (pin "1") (pinfunction "VIN_1") (pintype "bidirectional"))
      (node (ref "U14") (pin "8") (pinfunction "V+_8") (pintype "bidirectional"))
    )
    (net (code "109") (name "/V_COMP_+") (class "Default")
      (node (ref "U1") (pin "2") (pinfunction "VOUT_2") (pintype "bidirectional"))
      (node (ref "U2") (pin "3") (pinfunction "+INA_3") (pintype "input"))
    )
    (net (code "110") (name "/V_COMP_-") (class "Default")
      (node (ref "R15") (pin "1") (pinfunction "1_1") (pintype "passive"))
      (node (ref "R16") (pin "2") (pinfunction "2_2") (pintype "passive"))
      (node (ref "U2") (pin "2") (pinfunction "-INA_2") (pintype "input"))
    )
    (net (code "111") (name "/V_J1850") (class "Default")
      (node (ref "Q17") (pin "6") (pinfunction "S_6") (pintype "bidirectional"))
      (node (ref "Q17") (pin "7") (pinfunction "S_7") (pintype "bidirectional"))
      (node (ref "Q17") (pin "8") (pinfunction "S_8") (pintype "bidirectional"))
      (node (ref "R41") (pin "2") (pinfunction "2_2") (pintype "passive"))
      (node (ref "R51") (pin "2") (pinfunction "2_2") (pintype "passive"))
      (node (ref "TP104") (pin "P$1") (pinfunction "1_P$1") (pintype "bidirectional"))
      (node (ref "U13") (pin "2") (pinfunction "VOUT_2") (pintype "bidirectional"))
      (node (ref "U13") (pin "3") (pinfunction "VOUT_3") (pintype "bidirectional"))
      (node (ref "U13") (pin "6") (pinfunction "VOUT_6") (pintype "bidirectional"))
      (node (ref "U13") (pin "7") (pinfunction "VOUT_7") (pintype "bidirectional"))
    )
    (net (code "112") (name "Net-(C10-Pad2)") (class "Default")
      (node (ref "C10") (pin "2") (pinfunction "2_2") (pintype "passive"))
      (node (ref "R29") (pin "1") (pinfunction "1_1") (pintype "passive"))
    )
    (net (code "113") (name "Net-(C11-Pad2)") (class "Default")
      (node (ref "C11") (pin "2") (pinfunction "2_2") (pintype "passive"))
      (node (ref "R30") (pin "1") (pinfunction "1_1") (pintype "passive"))
    )
    (net (code "114") (name "Net-(C12-Pad2)") (class "Default")
      (node (ref "C12") (pin "2") (pinfunction "2_2") (pintype "passive"))
      (node (ref "R27") (pin "1") (pinfunction "1_1") (pintype "passive"))
    )
    (net (code "115") (name "Net-(C13-Pad2)") (class "Default")
      (node (ref "C13") (pin "2") (pinfunction "2_2") (pintype "passive"))
      (node (ref "R28") (pin "1") (pinfunction "1_1") (pintype "passive"))
    )
    (net (code "116") (name "Net-(D2-C)") (class "Default")
      (node (ref "D2") (pin "-") (pinfunction "C_-") (pintype "passive"))
      (node (ref "R14") (pin "2") (pinfunction "2_2") (pintype "passive"))
    )
    (net (code "117") (name "Net-(D4-A)") (class "Default")
      (node (ref "D4") (pin "+") (pinfunction "A_+") (pintype "passive"))
      (node (ref "R20") (pin "1") (pinfunction "1_1") (pintype "passive"))
    )
    (net (code "118") (name "Net-(D5-C)") (class "Default")
      (node (ref "D5") (pin "-") (pinfunction "C_-") (pintype "passive"))
      (node (ref "R21") (pin "2") (pinfunction "2_2") (pintype "passive"))
    )
    (net (code "119") (name "Net-(D6-C)") (class "Default")
      (node (ref "D6") (pin "-") (pinfunction "C_-") (pintype "passive"))
      (node (ref "R22") (pin "2") (pinfunction "2_2") (pintype "passive"))
    )
    (net (code "120") (name "Net-(D11-PadA)") (class "Default")
      (node (ref "D11") (pin "A") (pinfunction "A_A") (pintype "passive"))
      (node (ref "Q17") (pin "1") (pinfunction "D_1") (pintype "bidirectional"))
      (node (ref "Q17") (pin "2") (pinfunction "D_2") (pintype "bidirectional"))
      (node (ref "Q17") (pin "3") (pinfunction "D_3") (pintype "bidirectional"))
      (node (ref "Q17") (pin "4") (pinfunction "D_4") (pintype "bidirectional"))
    )
    (net (code "121") (name "Net-(D12-PadA)") (class "Default")
      (node (ref "D12") (pin "A") (pinfunction "A_A") (pintype "passive"))
      (node (ref "R53") (pin "2") (pinfunction "2_2") (pintype "passive"))
    )
    (net (code "122") (name "Net-(D13-PadC)") (class "Default")
      (node (ref "D13") (pin "C") (pinfunction "C_C") (pintype "passive"))
      (node (ref "R55") (pin "2") (pinfunction "2_2") (pintype "passive"))
    )
    (net (code "123") (name "Net-(D14-C)") (class "Default")
      (node (ref "D14") (pin "-") (pinfunction "C_-") (pintype "passive"))
      (node (ref "R68") (pin "2") (pinfunction "2_2") (pintype "passive"))
    )
    (net (code "124") (name "Net-(D15-C)") (class "Default")
      (node (ref "D15") (pin "-") (pinfunction "C_-") (pintype "passive"))
      (node (ref "R69") (pin "2") (pinfunction "2_2") (pintype "passive"))
    )
    (net (code "125") (name "Net-(D16-C)") (class "Default")
      (node (ref "D16") (pin "-") (pinfunction "C_-") (pintype "passive"))
      (node (ref "R105") (pin "2") (pinfunction "2_2") (pintype "passive"))
    )
    (net (code "126") (name "Net-(D18-C)") (class "Default")
      (node (ref "D18") (pin "-") (pinfunction "C_-") (pintype "passive"))
      (node (ref "R95") (pin "2") (pinfunction "2_2") (pintype "passive"))
    )
    (net (code "127") (name "Net-(D19-C)") (class "Default")
      (node (ref "D19") (pin "-") (pinfunction "C_-") (pintype "passive"))
      (node (ref "R96") (pin "2") (pinfunction "2_2") (pintype "passive"))
    )
    (net (code "128") (name "Net-(J6-Pad1)") (class "Default")
      (node (ref "J6") (pin "1") (pinfunction "1_1") (pintype "bidirectional"))
      (node (ref "R12") (pin "2") (pinfunction "2_2") (pintype "passive"))
    )
    (net (code "129") (name "Net-(J6-Pad2)") (class "Default")
      (node (ref "J6") (pin "2") (pinfunction "2_2") (pintype "bidirectional"))
      (node (ref "R92") (pin "2") (pinfunction "2_2") (pintype "passive"))
    )
    (net (code "130") (name "Net-(M2-SHIELD)") (class "Default")
      (node (ref "C45") (pin "2") (pinfunction "2_2") (pintype "passive"))
      (node (ref "M2") (pin "MOUNT5T") (pinfunction "SHIELD_MOUNT5T") (pintype "bidirectional"))
      (node (ref "R93") (pin "1") (pinfunction "1_1") (pintype "passive"))
    )
    (net (code "131") (name "Net-(M2-VBUS)") (class "Default")
      (node (ref "F3") (pin "2") (pinfunction "2_2") (pintype "bidirectional"))
      (node (ref "M2") (pin "1") (pinfunction "VBUS_1") (pintype "power_in"))
    )
    (net (code "132") (name "Net-(M12-1)") (class "Default")
      (node (ref "M12") (pin "P$1") (pinfunction "1_P$1") (pintype "bidirectional"))
      (node (ref "S4") (pin "C1") (pinfunction "C1_C1") (pintype "passive"))
    )
    (net (code "133") (name "Net-(M12-3)") (class "Default")
      (node (ref "M12") (pin "P$3") (pinfunction "3_P$3") (pintype "bidirectional"))
      (node (ref "Q7") (pin "5") (pinfunction "G_5") (pintype "bidirectional"))
      (node (ref "R91") (pin "1") (pinfunction "1_1") (pintype "passive"))
      (node (ref "S4") (pin "C2") (pinfunction "C2_C2") (pintype "passive"))
    )
    (net (code "134") (name "Net-(Q5-S-Pad6)") (class "Default")
      (node (ref "Q5") (pin "6") (pinfunction "S_6") (pintype "bidirectional"))
      (node (ref "Q5") (pin "7") (pinfunction "S_7") (pintype "bidirectional"))
      (node (ref "Q5") (pin "8") (pinfunction "S_8") (pintype "bidirectional"))
      (node (ref "Q7") (pin "6") (pinfunction "S_6") (pintype "bidirectional"))
      (node (ref "Q7") (pin "7") (pinfunction "S_7") (pintype "bidirectional"))
      (node (ref "Q7") (pin "8") (pinfunction "S_8") (pintype "bidirectional"))
      (node (ref "R91") (pin "2") (pinfunction "2_2") (pintype "passive"))
    )
    (net (code "135") (name "Net-(Q6-D)") (class "Default")
      (node (ref "Q6") (pin "3") (pinfunction "D_3") (pintype "bidirectional"))
      (node (ref "R11") (pin "1") (pinfunction "1_1") (pintype "passive"))
      (node (ref "U3") (pin "10") (pinfunction "ON/OFF_L_10") (pintype "bidirectional"))
    )
    (net (code "136") (name "Net-(Q10-G)") (class "Default")
      (node (ref "Q10") (pin "1") (pinfunction "G_1") (pintype "bidirectional"))
      (node (ref "Q11") (pin "1") (pinfunction "G_1") (pintype "bidirectional"))
      (node (ref "Q8") (pin "1") (pinfunction "S_1") (pintype "bidirectional"))
      (node (ref "Q8") (pin "2") (pinfunction "S_2") (pintype "bidirectional"))
      (node (ref "Q8") (pin "3") (pinfunction "S_3") (pintype "bidirectional"))
      (node (ref "Q9") (pin "1") (pinfunction "G_1") (pintype "bidirectional"))
      (node (ref "R24") (pin "1") (pinfunction "1_1") (pintype "passive"))
    )
    (net (code "137") (name "Net-(Q13-B)") (class "Default")
      (node (ref "Q13") (pin "1") (pinfunction "B_1") (pintype "passive"))
      (node (ref "R35") (pin "2") (pinfunction "2_2") (pintype "passive"))
    )
    (net (code "138") (name "Net-(Q14-B)") (class "Default")
      (node (ref "Q14") (pin "1") (pinfunction "B_1") (pintype "passive"))
      (node (ref "R36") (pin "2") (pinfunction "2_2") (pintype "passive"))
    )
    (net (code "139") (name "Net-(Q15-D)") (class "Default")
      (node (ref "Q15") (pin "3") (pinfunction "D_3") (pintype "bidirectional"))
      (node (ref "R42") (pin "1") (pinfunction "1_1") (pintype "passive"))
      (node (ref "R43") (pin "2") (pinfunction "2_2") (pintype "passive"))
    )
    (net (code "140") (name "Net-(Q16-D)") (class "Default")
      (node (ref "Q16") (pin "3") (pinfunction "D_3") (pintype "bidirectional"))
      (node (ref "Q17") (pin "5") (pinfunction "G_5") (pintype "bidirectional"))
      (node (ref "R51") (pin "1") (pinfunction "1_1") (pintype "passive"))
    )
    (net (code "141") (name "Net-(Q27-D)") (class "Default")
      (node (ref "Q27") (pin "3") (pinfunction "D_3") (pintype "bidirectional"))
      (node (ref "R103") (pin "P$1") (pinfunction "1_P$1") (pintype "passive"))
    )
    (net (code "142") (name "Net-(TP1-1)") (class "Default")
      (node (ref "TP1") (pin "P$1") (pinfunction "1_P$1") (pintype "bidirectional"))
      (node (ref "U18") (pin "P$19") (pinfunction "19.GPIO2_P$19") (pintype "bidirectional"))
    )
    (net (code "143") (name "Net-(U3-VADJ)") (class "Default")
      (node (ref "C3") (pin "1") (pinfunction "1_1") (pintype "passive"))
      (node (ref "R10") (pin "2") (pinfunction "2_2") (pintype "passive"))
      (node (ref "R9") (pin "1") (pinfunction "1_1") (pintype "passive"))
      (node (ref "U3") (pin "6") (pinfunction "VADJ_6") (pintype "bidirectional"))
    )
    (net (code "144") (name "Net-(U7-7.VCAP)") (class "Default")
      (node (ref "C19") (pin "2") (pinfunction "2_2") (pintype "passive"))
      (node (ref "U7") (pin "P$7") (pinfunction "7.VCAP_P$7") (pintype "bidirectional"))
    )
    (net (code "145") (name "Net-(U7-17.AVDD)") (class "Default")
      (node (ref "C6") (pin "1") (pinfunction "1_1") (pintype "passive"))
      (node (ref "R17") (pin "2") (pinfunction "2_2") (pintype "passive"))
      (node (ref "U7") (pin "P$17") (pinfunction "17.AVDD_P$17") (pintype "bidirectional"))
    )
    (net (code "146") (name "Net-(U7-30.OSC1)") (class "Default")
      (node (ref "C21") (pin "2") (pinfunction "2_2") (pintype "passive"))
      (node (ref "U7") (pin "P$30") (pinfunction "30.OSC1_P$30") (pintype "bidirectional"))
      (node (ref "X1") (pin "P$1") (pinfunction "1_P$1") (pintype "passive"))
    )
    (net (code "147") (name "Net-(U7-31.OSC2)") (class "Default")
      (node (ref "C22") (pin "1") (pinfunction "1_1") (pintype "passive"))
      (node (ref "U7") (pin "P$31") (pinfunction "31.OSC2_P$31") (pintype "bidirectional"))
      (node (ref "X1") (pin "P$3") (pinfunction "2_P$3") (pintype "passive"))
    )
    (net (code "148") (name "Net-(U9-RS)") (class "Default")
      (node (ref "R26") (pin "2") (pinfunction "2_2") (pintype "passive"))
      (node (ref "U9") (pin "6") (pinfunction "RS_6") (pintype "bidirectional"))
    )
    (net (code "149") (name "Net-(U10-RS)") (class "Default")
      (node (ref "R25") (pin "2") (pinfunction "2_2") (pintype "passive"))
      (node (ref "U10") (pin "6") (pinfunction "RS_6") (pintype "bidirectional"))
    )
    (net (code "150") (name "Net-(U11-LOAD)") (class "Default")
      (node (ref "R32") (pin "1") (pinfunction "1_1") (pintype "passive"))
      (node (ref "U11") (pin "6") (pinfunction "LOAD_6") (pintype "bidirectional"))
    )
    (net (code "151") (name "Net-(U12-+INA)") (class "Default")
      (node (ref "R37") (pin "1") (pinfunction "1_1") (pintype "passive"))
      (node (ref "R38") (pin "2") (pinfunction "2_2") (pintype "passive"))
      (node (ref "U12") (pin "3") (pinfunction "+INA_3") (pintype "input"))
    )
    (net (code "152") (name "Net-(U12--INA)") (class "Default")
      (node (ref "R39") (pin "2") (pinfunction "2_2") (pintype "passive"))
      (node (ref "U12") (pin "2") (pinfunction "-INA_2") (pintype "input"))
    )
    (net (code "153") (name "Net-(U13-ADJ)") (class "Default")
      (node (ref "R41") (pin "1") (pinfunction "1_1") (pintype "passive"))
      (node (ref "R42") (pin "2") (pinfunction "2_2") (pintype "passive"))
      (node (ref "U13") (pin "4") (pinfunction "ADJ_4") (pintype "bidirectional"))
    )
    (net (code "154") (name "Net-(U14-+INA)") (class "Default")
      (node (ref "R44") (pin "2") (pinfunction "2_2") (pintype "passive"))
      (node (ref "U14") (pin "3") (pinfunction "+INA_3") (pintype "input"))
    )
    (net (code "155") (name "Net-(U14-+INB)") (class "Default")
      (node (ref "D10") (pin "C") (pinfunction "C_C") (pintype "passive"))
      (node (ref "R47") (pin "1") (pinfunction "1_1") (pintype "passive"))
      (node (ref "U14") (pin "5") (pinfunction "+INB_5") (pintype "input"))
    )
    (net (code "156") (name "Net-(U14--INA)") (class "Default")
      (node (ref "R45") (pin "2") (pinfunction "2_2") (pintype "passive"))
      (node (ref "U14") (pin "2") (pinfunction "-INA_2") (pintype "input"))
    )
    (net (code "157") (name "Net-(U14--INB)") (class "Default")
      (node (ref "R48") (pin "1") (pinfunction "1_1") (pintype "passive"))
      (node (ref "R49") (pin "2") (pinfunction "2_2") (pintype "passive"))
      (node (ref "U14") (pin "6") (pinfunction "-INB_6") (pintype "input"))
    )
    (net (code "158") (name "Net-(U16-16.VREGD)") (class "Default")
      (node (ref "C27") (pin "2") (pinfunction "2_2") (pintype "passive"))
      (node (ref "U16") (pin "P$16") (pinfunction "16.VREGD_P$16") (pintype "bidirectional"))
    )
    (net (code "159") (name "Net-(U17-C1)") (class "Default")
      (node (ref "C30") (pin "2") (pinfunction "2_2") (pintype "passive"))
      (node (ref "U17") (pin "P$4") (pinfunction "C1_P$4") (pintype "bidirectional"))
    )
    (net (code "160") (name "Net-(U19-PH0-OSC_IN)") (class "Default")
      (node (ref "C34") (pin "2") (pinfunction "2_2") (pintype "passive"))
      (node (ref "U19") (pin "P$5") (pinfunction "PH0-OSC_IN_P$5") (pintype "bidirectional"))
      (node (ref "X2") (pin "P$1") (pinfunction "1_P$1") (pintype "passive"))
    )
    (net (code "161") (name "Net-(U19-PH1-OSC_OUT)") (class "Default")
      (node (ref "C35") (pin "2") (pinfunction "2_2") (pintype "passive"))
      (node (ref "U19") (pin "P$6") (pinfunction "PH1-OSC_OUT_P$6") (pintype "bidirectional"))
      (node (ref "X2") (pin "P$3") (pinfunction "2_P$3") (pintype "passive"))
    )
    (net (code "162") (name "Net-(U19-VCAP_1)") (class "Default")
      (node (ref "C37") (pin "1") (pinfunction "1_1") (pintype "passive"))
      (node (ref "U19") (pin "P$30") (pinfunction "VCAP_1_P$30") (pintype "bidirectional"))
    )
    (net (code "163") (name "SYM_3.3V") (class "Default")
      (node (ref "C20") (pin "2") (pinfunction "2_2") (pintype "passive"))
      (node (ref "C23") (pin "1") (pinfunction "1_1") (pintype "passive"))
      (node (ref "C24") (pin "1") (pinfunction "1_1") (pintype "passive"))
      (node (ref "C25") (pin "2") (pinfunction "2_2") (pintype "passive"))
      (node (ref "C26") (pin "2") (pinfunction "2_2") (pintype "passive"))
      (node (ref "C28") (pin "1") (pinfunction "1_1") (pintype "passive"))
      (node (ref "C29") (pin "1") (pinfunction "1_1") (pintype "passive"))
      (node (ref "C30") (pin "1") (pinfunction "1_1") (pintype "passive"))
      (node (ref "C31") (pin "2") (pinfunction "2_2") (pintype "passive"))
      (node (ref "C32") (pin "2") (pinfunction "2_2") (pintype "passive"))
      (node (ref "C33") (pin "2") (pinfunction "2_2") (pintype "passive"))
      (node (ref "C36") (pin "1") (pinfunction "1_1") (pintype "passive"))
      (node (ref "C38") (pin "1") (pinfunction "1_1") (pintype "passive"))
      (node (ref "C39") (pin "1") (pinfunction "1_1") (pintype "passive"))
      (node (ref "C40") (pin "1") (pinfunction "1_1") (pintype "passive"))
      (node (ref "C41") (pin "1") (pinfunction "1_1") (pintype "passive"))
      (node (ref "C42") (pin "1") (pinfunction "1_1") (pintype "passive"))
      (node (ref "C43") (pin "1") (pinfunction "1_1") (pintype "passive"))
      (node (ref "C8") (pin "1") (pinfunction "1_1") (pintype "passive"))
      (node (ref "D14") (pin "+") (pinfunction "A_+") (pintype "passive"))
      (node (ref "D15") (pin "+") (pinfunction "A_+") (pintype "passive"))
      (node (ref "D18") (pin "+") (pinfunction "A_+") (pintype "passive"))
      (node (ref "D19") (pin "+") (pinfunction "A_+") (pintype "passive"))
      (node (ref "D2") (pin "+") (pinfunction "A_+") (pintype "passive"))
      (node (ref "D21") (pin "C") (pinfunction "C_C") (pintype "passive"))
      (node (ref "D5") (pin "+") (pinfunction "A_+") (pintype "passive"))
      (node (ref "D6") (pin "+") (pinfunction "A_+") (pintype "passive"))
      (node (ref "J1") (pin "2") (pinfunction "2_2") (pintype "bidirectional"))
      (node (ref "J2") (pin "2") (pinfunction "2_2") (pintype "bidirectional"))
      (node (ref "J3") (pin "2") (pinfunction "2_2") (pintype "bidirectional"))
      (node (ref "J5") (pin "1") (pinfunction "1_1") (pintype "bidirectional"))
      (node (ref "J6") (pin "4") (pinfunction "4_4") (pintype "bidirectional"))
      (node (ref "J8") (pin "2") (pinfunction "2_2") (pintype "bidirectional"))
      (node (ref "M1") (pin "P$4") (pinfunction "VDD_P$4") (pintype "bidirectional"))
      (node (ref "M7") (pin "P$3") (pinfunction "3_P$3") (pintype "bidirectional"))
      (node (ref "M8") (pin "P$3") (pinfunction "3_P$3") (pintype "bidirectional"))
      (node (ref "Q1") (pin "1") (pinfunction "G_1") (pintype "bidirectional"))
      (node (ref "Q11") (pin "3") (pinfunction "D_3") (pintype "bidirectional"))
      (node (ref "Q19") (pin "1") (pinfunction "G_1") (pintype "bidirectional"))
      (node (ref "Q2") (pin "1") (pinfunction "G_1") (pintype "bidirectional"))
      (node (ref "Q20") (pin "1") (pinfunction "G_1") (pintype "bidirectional"))
      (node (ref "Q21") (pin "1") (pinfunction "G_1") (pintype "bidirectional"))
      (node (ref "Q22") (pin "1") (pinfunction "G_1") (pintype "bidirectional"))
      (node (ref "Q23") (pin "1") (pinfunction "G_1") (pintype "bidirectional"))
      (node (ref "Q24") (pin "1") (pinfunction "G_1") (pintype "bidirectional"))
      (node (ref "Q25") (pin "1") (pinfunction "G_1") (pintype "bidirectional"))
      (node (ref "Q26") (pin "1") (pinfunction "G_1") (pintype "bidirectional"))
      (node (ref "Q3") (pin "1") (pinfunction "G_1") (pintype "bidirectional"))
      (node (ref "Q4") (pin "1") (pinfunction "G_1") (pintype "bidirectional"))
      (node (ref "R1") (pin "2") (pinfunction "2_2") (pintype "passive"))
      (node (ref "R100") (pin "1") (pinfunction "1_1") (pintype "passive"))
      (node (ref "R13") (pin "2") (pinfunction "2_2") (pintype "passive"))
      (node (ref "R17") (pin "1") (pinfunction "1_1") (pintype "passive"))
      (node (ref "R23") (pin "2") (pinfunction "2_2") (pintype "passive"))
      (node (ref "R3") (pin "2") (pinfunction "2_2") (pintype "passive"))
      (node (ref "R31") (pin "2") (pinfunction "2_2") (pintype "passive"))
      (node (ref "R40") (pin "2") (pinfunction "2_2") (pintype "passive"))
      (node (ref "R46") (pin "2") (pinfunction "2_2") (pintype "passive"))
      (node (ref "R5") (pin "2") (pinfunction "2_2") (pintype "passive"))
      (node (ref "R50") (pin "2") (pinfunction "2_2") (pintype "passive"))
      (node (ref "R58") (pin "2") (pinfunction "2_2") (pintype "passive"))
      (node (ref "R59") (pin "2") (pinfunction "2_2") (pintype "passive"))
      (node (ref "R60") (pin "2") (pinfunction "2_2") (pintype "passive"))
      (node (ref "R61") (pin "2") (pinfunction "2_2") (pintype "passive"))
      (node (ref "R62") (pin "2") (pinfunction "2_2") (pintype "passive"))
      (node (ref "R63") (pin "1") (pinfunction "1_1") (pintype "passive"))
      (node (ref "R64") (pin "2") (pinfunction "2_2") (pintype "passive"))
      (node (ref "R7") (pin "2") (pinfunction "2_2") (pintype "passive"))
      (node (ref "R73") (pin "1") (pinfunction "1_1") (pintype "passive"))
      (node (ref "R74") (pin "2") (pinfunction "2_2") (pintype "passive"))
      (node (ref "R76") (pin "2") (pinfunction "2_2") (pintype "passive"))
      (node (ref "R78") (pin "2") (pinfunction "2_2") (pintype "passive"))
      (node (ref "R80") (pin "2") (pinfunction "2_2") (pintype "passive"))
      (node (ref "R82") (pin "2") (pinfunction "2_2") (pintype "passive"))
      (node (ref "R84") (pin "2") (pinfunction "2_2") (pintype "passive"))
      (node (ref "R86") (pin "2") (pinfunction "2_2") (pintype "passive"))
      (node (ref "R88") (pin "2") (pinfunction "2_2") (pintype "passive"))
      (node (ref "R94") (pin "1") (pinfunction "1_1") (pintype "passive"))
      (node (ref "R97") (pin "2") (pinfunction "2_2") (pintype "passive"))
      (node (ref "R98") (pin "2") (pinfunction "2_2") (pintype "passive"))
      (node (ref "R99") (pin "1") (pinfunction "1_1") (pintype "passive"))
      (node (ref "S2") (pin "P$3") (pinfunction "2_P$3") (pintype "passive"))
      (node (ref "S2") (pin "P$4") (pinfunction "2_P$4") (pintype "passive"))
      (node (ref "S3") (pin "P$3") (pinfunction "2_P$3") (pintype "passive"))
      (node (ref "S3") (pin "P$4") (pinfunction "2_P$4") (pintype "passive"))
      (node (ref "TP14") (pin "P$1") (pinfunction "1_P$1") (pintype "bidirectional"))
      (node (ref "U15") (pin "P$1") (pinfunction "1.VDD_IO_P$1") (pintype "bidirectional"))
      (node (ref "U15") (pin "P$14") (pinfunction "14.VDD_P$14") (pintype "bidirectional"))
      (node (ref "U16") (pin "P$15") (pinfunction "15.VDD_P$15") (pintype "bidirectional"))
      (node (ref "U16") (pin "P$18") (pinfunction "18.VDDIO_P$18") (pintype "bidirectional"))
      (node (ref "U16") (pin "P$4") (pinfunction "4.RST_B_P$4") (pintype "bidirectional"))
      (node (ref "U16") (pin "P$8") (pinfunction "8.I2C_B/SPI_P$8") (pintype "bidirectional"))
      (node (ref "U17") (pin "P$5") (pinfunction "VDD_P$5") (pintype "bidirectional"))
      (node (ref "U17") (pin "P$6") (pinfunction "VDD_IO_P$6") (pintype "bidirectional"))
      (node (ref "U18") (pin "P$11") (pinfunction "11.VDD_P$11") (pintype "bidirectional"))
      (node (ref "U19") (pin "P$13") (pinfunction "VDDA/VREF+_P$13") (pintype "bidirectional"))
      (node (ref "U19") (pin "P$19") (pinfunction "VDD_P$19") (pintype "bidirectional"))
      (node (ref "U19") (pin "P$32") (pinfunction "VDD_1_P$32") (pintype "bidirectional"))
      (node (ref "U19") (pin "P$48") (pinfunction "VDD_2_P$48") (pintype "bidirectional"))
      (node (ref "U19") (pin "P$64") (pinfunction "VDD_3_P$64") (pintype "bidirectional"))
      (node (ref "U6") (pin "5") (pinfunction "VOUT_5") (pintype "bidirectional"))
      (node (ref "U7") (pin "P$28") (pinfunction "28.VDD_0_P$28") (pintype "bidirectional"))
      (node (ref "U7") (pin "P$40") (pinfunction "40.VDD_1_P$40") (pintype "bidirectional"))
    )
    (net (code "164") (name "SYM_5V") (class "Default")
      (node (ref "D16") (pin "+") (pinfunction "A_+") (pintype "passive"))
      (node (ref "D3") (pin "C") (pinfunction "C_C") (pintype "passive"))
      (node (ref "D7") (pin "C") (pinfunction "C_C") (pintype "passive"))
      (node (ref "Q10") (pin "3") (pinfunction "D_3") (pintype "bidirectional"))
      (node (ref "R65") (pin "2") (pinfunction "2_2") (pintype "passive"))
      (node (ref "R75") (pin "2") (pinfunction "2_2") (pintype "passive"))
      (node (ref "R77") (pin "2") (pinfunction "2_2") (pintype "passive"))
      (node (ref "R79") (pin "2") (pinfunction "2_2") (pintype "passive"))
      (node (ref "R81") (pin "2") (pinfunction "2_2") (pintype "passive"))
      (node (ref "R83") (pin "2") (pinfunction "2_2") (pintype "passive"))
      (node (ref "R85") (pin "2") (pinfunction "2_2") (pintype "passive"))
      (node (ref "R87") (pin "2") (pinfunction "2_2") (pintype "passive"))
      (node (ref "R89") (pin "2") (pinfunction "2_2") (pintype "passive"))
      (node (ref "TP13") (pin "P$1") (pinfunction "1_P$1") (pintype "bidirectional"))
      (node (ref "U6") (pin "1") (pinfunction "VIN_1") (pintype "bidirectional"))
      (node (ref "U6") (pin "3") (pinfunction "INHIBIT_3") (pintype "bidirectional"))
    )
    (net (code "165") (name "SYM_GND") (class "Default")
      (node (ref "C1") (pin "2") (pinfunction "2_2") (pintype "passive"))
      (node (ref "C10") (pin "1") (pinfunction "1_1") (pintype "passive"))
      (node (ref "C11") (pin "1") (pinfunction "1_1") (pintype "passive"))
      (node (ref "C12") (pin "1") (pinfunction "1_1") (pintype "passive"))
      (node (ref "C13") (pin "1") (pinfunction "1_1") (pintype "passive"))
      (node (ref "C14") (pin "2") (pinfunction "2_2") (pintype "passive"))
      (node (ref "C15") (pin "2") (pinfunction "2_2") (pintype "passive"))
      (node (ref "C16") (pin "1") (pinfunction "1_1") (pintype "passive"))
      (node (ref "C17") (pin "2") (pinfunction "2_2") (pintype "passive"))
      (node (ref "C18") (pin "1") (pinfunction "1_1") (pintype "passive"))
      (node (ref "C19") (pin "1") (pinfunction "1_1") (pintype "passive"))
      (node (ref "C2") (pin "2") (pinfunction "2_2") (pintype "passive"))
      (node (ref "C20") (pin "1") (pinfunction "1_1") (pintype "passive"))
      (node (ref "C21") (pin "1") (pinfunction "1_1") (pintype "passive"))
      (node (ref "C22") (pin "2") (pinfunction "2_2") (pintype "passive"))
      (node (ref "C23") (pin "2") (pinfunction "2_2") (pintype "passive"))
      (node (ref "C24") (pin "2") (pinfunction "2_2") (pintype "passive"))
      (node (ref "C25") (pin "1") (pinfunction "1_1") (pintype "passive"))
      (node (ref "C26") (pin "1") (pinfunction "1_1") (pintype "passive"))
      (node (ref "C27") (pin "1") (pinfunction "1_1") (pintype "passive"))
      (node (ref "C28") (pin "2") (pinfunction "2_2") (pintype "passive"))
      (node (ref "C29") (pin "2") (pinfunction "2_2") (pintype "passive"))
      (node (ref "C3") (pin "2") (pinfunction "2_2") (pintype "passive"))
      (node (ref "C31") (pin "1") (pinfunction "1_1") (pintype "passive"))
      (node (ref "C32") (pin "1") (pinfunction "1_1") (pintype "passive"))
      (node (ref "C33") (pin "1") (pinfunction "1_1") (pintype "passive"))
      (node (ref "C34") (pin "1") (pinfunction "1_1") (pintype "passive"))
      (node (ref "C35") (pin "1") (pinfunction "1_1") (pintype "passive"))
      (node (ref "C36") (pin "2") (pinfunction "2_2") (pintype "passive"))
      (node (ref "C37") (pin "2") (pinfunction "2_2") (pintype "passive"))
      (node (ref "C38") (pin "2") (pinfunction "2_2") (pintype "passive"))
      (node (ref "C39") (pin "2") (pinfunction "2_2") (pintype "passive"))
      (node (ref "C4") (pin "PIN_1_-") (pinfunction "-_PIN_1_-") (pintype "passive"))
      (node (ref "C40") (pin "2") (pinfunction "2_2") (pintype "passive"))
      (node (ref "C41") (pin "2") (pinfunction "2_2") (pintype "passive"))
      (node (ref "C42") (pin "2") (pinfunction "2_2") (pintype "passive"))
      (node (ref "C43") (pin "2") (pinfunction "2_2") (pintype "passive"))
      (node (ref "C44") (pin "2") (pinfunction "2_2") (pintype "passive"))
      (node (ref "C45") (pin "1") (pinfunction "1_1") (pintype "passive"))
      (node (ref "C5") (pin "2") (pinfunction "2_2") (pintype "passive"))
      (node (ref "C6") (pin "2") (pinfunction "2_2") (pintype "passive"))
      (node (ref "C7") (pin "1") (pinfunction "1_1") (pintype "passive"))
      (node (ref "C8") (pin "2") (pinfunction "2_2") (pintype "passive"))
      (node (ref "D1") (pin "A") (pinfunction "A_A") (pintype "passive"))
      (node (ref "D10") (pin "A") (pinfunction "A_A") (pintype "passive"))
      (node (ref "D12") (pin "C") (pinfunction "C_C") (pintype "passive"))
      (node (ref "D20") (pin "A") (pinfunction "A_A") (pintype "passive"))
      (node (ref "D4") (pin "-") (pinfunction "C_-") (pintype "passive"))
      (node (ref "D8") (pin "3") (pinfunction "C_3") (pintype "bidirectional"))
      (node (ref "D9") (pin "3") (pinfunction "C_3") (pintype "bidirectional"))
      (node (ref "J4") (pin "2") (pinfunction "2_2") (pintype "bidirectional"))
      (node (ref "J5") (pin "3") (pinfunction "3_3") (pintype "bidirectional"))
      (node (ref "J6") (pin "3") (pinfunction "3_3") (pintype "bidirectional"))
      (node (ref "J7") (pin "P$1") (pinfunction "1_P$1") (pintype "bidirectional"))
      (node (ref "M1") (pin "CD_SW1") (pinfunction "CD_SW1_CD_SW1") (pintype "bidirectional"))
      (node (ref "M1") (pin "P$6") (pinfunction "VSS1_P$6") (pintype "bidirectional"))
      (node (ref "M10") (pin "4") (pinfunction "4.GND_CHASSIS_4") (pintype "bidirectional"))
      (node (ref "M10") (pin "5") (pinfunction "5.GND_SIGNAL_5") (pintype "bidirectional"))
      (node (ref "M2") (pin "5") (pinfunction "GND_5") (pintype "power_in"))
      (node (ref "M3") (pin "P$2") (pinfunction "2_P$2") (pintype "bidirectional"))
      (node (ref "M4") (pin "P$2") (pinfunction "2_P$2") (pintype "bidirectional"))
      (node (ref "M5") (pin "P$2") (pinfunction "2_P$2") (pintype "bidirectional"))
      (node (ref "M6") (pin "P$2") (pinfunction "2_P$2") (pintype "bidirectional"))
      (node (ref "M7") (pin "P$4") (pinfunction "4_P$4") (pintype "bidirectional"))
      (node (ref "M8") (pin "P$4") (pinfunction "4_P$4") (pintype "bidirectional"))
      (node (ref "M9") (pin "P$2") (pinfunction "1_P$2") (pintype "bidirectional"))
      (node (ref "Q13") (pin "2") (pinfunction "E_2") (pintype "passive"))
      (node (ref "Q14") (pin "2") (pinfunction "E_2") (pintype "passive"))
      (node (ref "Q15") (pin "2") (pinfunction "S_2") (pintype "bidirectional"))
      (node (ref "Q16") (pin "2") (pinfunction "S_2") (pintype "bidirectional"))
      (node (ref "Q18") (pin "2") (pinfunction "S_2") (pintype "bidirectional"))
      (node (ref "Q27") (pin "2") (pinfunction "S_2") (pintype "bidirectional"))
      (node (ref "Q5") (pin "5") (pinfunction "G_5") (pintype "bidirectional"))
      (node (ref "Q6") (pin "2") (pinfunction "S_2") (pintype "bidirectional"))
      (node (ref "Q8") (pin "5") (pinfunction "D_5") (pintype "bidirectional"))
      (node (ref "Q8") (pin "6") (pinfunction "D_6") (pintype "bidirectional"))
      (node (ref "Q8") (pin "7") (pinfunction "D_7") (pintype "bidirectional"))
      (node (ref "Q8") (pin "8") (pinfunction "D_8") (pintype "bidirectional"))
      (node (ref "R10") (pin "1") (pinfunction "1_1") (pintype "passive"))
      (node (ref "R101") (pin "1") (pinfunction "1_1") (pintype "passive"))
      (node (ref "R102") (pin "1") (pinfunction "1_1") (pintype "passive"))
      (node (ref "R104") (pin "1") (pinfunction "1_1") (pintype "passive"))
      (node (ref "R105") (pin "1") (pinfunction "1_1") (pintype "passive"))
      (node (ref "R14") (pin "1") (pinfunction "1_1") (pintype "passive"))
      (node (ref "R16") (pin "1") (pinfunction "1_1") (pintype "passive"))
      (node (ref "R19") (pin "1") (pinfunction "1_1") (pintype "passive"))
      (node (ref "R25") (pin "1") (pinfunction "1_1") (pintype "passive"))
      (node (ref "R26") (pin "1") (pinfunction "1_1") (pintype "passive"))
      (node (ref "R38") (pin "1") (pinfunction "1_1") (pintype "passive"))
      (node (ref "R43") (pin "1") (pinfunction "1_1") (pintype "passive"))
      (node (ref "R49") (pin "1") (pinfunction "1_1") (pintype "passive"))
      (node (ref "R52") (pin "1") (pinfunction "1_1") (pintype "passive"))
      (node (ref "R70") (pin "1") (pinfunction "1_1") (pintype "passive"))
      (node (ref "R71") (pin "1") (pinfunction "1_1") (pintype "passive"))
      (node (ref "R72") (pin "1") (pinfunction "1_1") (pintype "passive"))
      (node (ref "R90") (pin "1") (pinfunction "1_1") (pintype "passive"))
      (node (ref "R93") (pin "2") (pinfunction "2_2") (pintype "passive"))
      (node (ref "S1") (pin "P$1") (pinfunction "1_P$1") (pintype "passive"))
      (node (ref "S1") (pin "P$2") (pinfunction "1_P$2") (pintype "passive"))
      (node (ref "S4") (pin "COM") (pinfunction "COM_COM") (pintype "passive"))
      (node (ref "TP110") (pin "P$1") (pinfunction "1_P$1") (pintype "bidirectional"))
      (node (ref "TP111") (pin "P$1") (pinfunction "1_P$1") (pintype "bidirectional"))
      (node (ref "TP112") (pin "P$1") (pinfunction "1_P$1") (pintype "bidirectional"))
      (node (ref "TP113") (pin "P$1") (pinfunction "1_P$1") (pintype "bidirectional"))
      (node (ref "TP15") (pin "P$1") (pinfunction "1_P$1") (pintype "bidirectional"))
      (node (ref "TP35") (pin "P$1") (pinfunction "1_P$1") (pintype "bidirectional"))
      (node (ref "TP44") (pin "P$1") (pinfunction "1_P$1") (pintype "bidirectional"))
      (node (ref "TP53") (pin "P$1") (pinfunction "1_P$1") (pintype "bidirectional"))
      (node (ref "TP54") (pin "P$1") (pinfunction "1_P$1") (pintype "bidirectional"))
      (node (ref "TP78") (pin "P$1") (pinfunction "1_P$1") (pintype "bidirectional"))
      (node (ref "U1") (pin "3") (pinfunction "GND_3") (pintype "bidirectional"))
      (node (ref "U10") (pin "2") (pinfunction "VSS_2") (pintype "bidirectional"))
      (node (ref "U11") (pin "8") (pinfunction "GND_8") (pintype "bidirectional"))
      (node (ref "U12") (pin "4") (pinfunction "V-_4") (pintype "bidirectional"))
      (node (ref "U14") (pin "4") (pinfunction "V-_4") (pintype "bidirectional"))
      (node (ref "U15") (pin "P$10") (pinfunction "10.RES_P$10") (pintype "bidirectional"))
      (node (ref "U15") (pin "P$12") (pinfunction "12.GND_P$12") (pintype "bidirectional"))
      (node (ref "U15") (pin "P$13") (pinfunction "13.ADC3_P$13") (pintype "bidirectional"))
      (node (ref "U15") (pin "P$15") (pinfunction "15.ADC2_P$15") (pintype "bidirectional"))
      (node (ref "U15") (pin "P$16") (pinfunction "16.ADC1_P$16") (pintype "bidirectional"))
      (node (ref "U15") (pin "P$5") (pinfunction "5.GND_P$5") (pintype "bidirectional"))
      (node (ref "U16") (pin "P$1") (pinfunction "1.GND1_P$1") (pintype "bidirectional"))
      (node (ref "U16") (pin "P$10") (pinfunction "10.RSVD_GND4_P$10") (pintype "bidirectional"))
      (node (ref "U16") (pin "P$14") (pinfunction "14.GND3_P$14") (pintype "bidirectional"))
      (node (ref "U16") (pin "P$19") (pinfunction "19.GND4_P$19") (pintype "bidirectional"))
      (node (ref "U16") (pin "P$20") (pinfunction "20.RSVD_GND5_P$20") (pintype "bidirectional"))
      (node (ref "U16") (pin "P$21") (pinfunction "21.RSVD_GND6_P$21") (pintype "bidirectional"))
      (node (ref "U16") (pin "P$22") (pinfunction "22.RSVD_GND7_P$22") (pintype "bidirectional"))
      (node (ref "U16") (pin "P$23") (pinfunction "23.RSVD_GND8_P$23") (pintype "bidirectional"))
      (node (ref "U16") (pin "P$24") (pinfunction "24.RSVD_GND9_P$24") (pintype "bidirectional"))
      (node (ref "U16") (pin "P$5") (pinfunction "5.GND2_P$5") (pintype "bidirectional"))
      (node (ref "U16") (pin "P$6") (pinfunction "6.RSVD_GND1_P$6") (pintype "bidirectional"))
      (node (ref "U16") (pin "P$7") (pinfunction "7.RSVD_GND2_P$7") (pintype "bidirectional"))
      (node (ref "U16") (pin "P$9") (pinfunction "9.RSVD_GND3_P$9") (pintype "bidirectional"))
      (node (ref "U17") (pin "P$12") (pinfunction "RES_1_P$12") (pintype "bidirectional"))
      (node (ref "U17") (pin "P$2") (pinfunction "RES_P$2") (pintype "bidirectional"))
      (node (ref "U17") (pin "P$3") (pinfunction "GND_P$3") (pintype "bidirectional"))
      (node (ref "U18") (pin "P$1") (pinfunction "1.GND_P$1") (pintype "bidirectional"))
      (node (ref "U18") (pin "P$12") (pinfunction "12.GND1_P$12") (pintype "bidirectional"))
      (node (ref "U18") (pin "P$28") (pinfunction "28.GND3_P$28") (pintype "bidirectional"))
      (node (ref "U18") (pin "P$29") (pinfunction "29.GND2_P$29") (pintype "bidirectional"))
      (node (ref "U18") (pin "SHEILD1") (pinfunction "SHIELD_SHEILD1") (pintype "bidirectional"))
      (node (ref "U18") (pin "SHEILD2") (pinfunction "SHIELD_SHEILD2") (pintype "bidirectional"))
      (node (ref "U18") (pin "SHEILD3") (pinfunction "SHIELD_SHEILD3") (pintype "bidirectional"))
      (node (ref "U18") (pin "SHEILD4") (pinfunction "SHIELD_SHEILD4") (pintype "bidirectional"))
      (node (ref "U19") (pin "P$12") (pinfunction "VSSA/VREF-_P$12") (pintype "bidirectional"))
      (node (ref "U19") (pin "P$18") (pinfunction "VSS_P$18") (pintype "bidirectional"))
      (node (ref "U19") (pin "P$31") (pinfunction "VSS_1_P$31") (pintype "bidirectional"))
      (node (ref "U19") (pin "P$47") (pinfunction "VSS_2_P$47") (pintype "bidirectional"))
      (node (ref "U19") (pin "P$63") (pinfunction "VSS_3_P$63") (pintype "bidirectional"))
      (node (ref "U2") (pin "4") (pinfunction "V-_4") (pintype "bidirectional"))
      (node (ref "U3") (pin "7") (pinfunction "GND_7") (pintype "bidirectional"))
      (node (ref "U3") (pin "9") (pinfunction "GND_9") (pintype "bidirectional"))
      (node (ref "U6") (pin "2") (pinfunction "GND_2") (pintype "bidirectional"))
      (node (ref "U7") (pin "P$1") (pinfunction "1.GP28_P$1") (pintype "bidirectional"))
      (node (ref "U7") (pin "P$15") (pinfunction "15.GP31_P$15") (pintype "bidirectional"))
      (node (ref "U7") (pin "P$16") (pinfunction "16.AVSS_P$16") (pintype "bidirectional"))
      (node (ref "U7") (pin "P$2") (pinfunction "2.GP29_P$2") (pintype "bidirectional"))
      (node (ref "U7") (pin "P$20") (pinfunction "20.GP32_P$20") (pintype "bidirectional"))
      (node (ref "U7") (pin "P$26") (pinfunction "26.GP33_P$26") (pintype "bidirectional"))
      (node (ref "U7") (pin "P$29") (pinfunction "29.VSS_0_P$29") (pintype "bidirectional"))
      (node (ref "U7") (pin "P$3") (pinfunction "3.GP30_P$3") (pintype "bidirectional"))
      (node (ref "U7") (pin "P$37") (pinfunction "37.GP34_P$37") (pintype "bidirectional"))
      (node (ref "U7") (pin "P$38") (pinfunction "38.GP35_P$38") (pintype "bidirectional"))
      (node (ref "U7") (pin "P$39") (pinfunction "39.VSS_1_P$39") (pintype "bidirectional"))
      (node (ref "U7") (pin "P$45") (pinfunction "PAD_P$45") (pintype "bidirectional"))
      (node (ref "U7") (pin "P$6") (pinfunction "6.VSS_P$6") (pintype "bidirectional"))
      (node (ref "U9") (pin "2") (pinfunction "VSS_2") (pintype "bidirectional"))
      (node (ref "X1") (pin "P$2") (pinfunction "COVER_P$2") (pintype "bidirectional"))
      (node (ref "X1") (pin "P$4") (pinfunction "COVER_P$4") (pintype "bidirectional"))
      (node (ref "X2") (pin "P$2") (pinfunction "COVER_P$2") (pintype "bidirectional"))
      (node (ref "X2") (pin "P$4") (pinfunction "COVER_P$4") (pintype "bidirectional"))
    )
    (net (code "166") (name "SYM_V_BATT") (class "Default")
      (node (ref "C17") (pin "1") (pinfunction "1_1") (pintype "passive"))
      (node (ref "C2") (pin "1") (pinfunction "1_1") (pintype "passive"))
      (node (ref "D1") (pin "C") (pinfunction "C_C") (pintype "passive"))
      (node (ref "F2") (pin "2") (pinfunction "2_2") (pintype "bidirectional"))
      (node (ref "Q12") (pin "6") (pinfunction "S_6") (pintype "bidirectional"))
      (node (ref "Q12") (pin "7") (pinfunction "S_7") (pintype "bidirectional"))
      (node (ref "Q12") (pin "8") (pinfunction "S_8") (pintype "bidirectional"))
      (node (ref "Q9") (pin "3") (pinfunction "D_3") (pintype "bidirectional"))
      (node (ref "R11") (pin "2") (pinfunction "2_2") (pintype "passive"))
      (node (ref "R15") (pin "2") (pinfunction "2_2") (pintype "passive"))
      (node (ref "R18") (pin "2") (pinfunction "2_2") (pintype "passive"))
      (node (ref "R2") (pin "2") (pinfunction "2_2") (pintype "passive"))
      (node (ref "R24") (pin "2") (pinfunction "2_2") (pintype "passive"))
      (node (ref "R4") (pin "2") (pinfunction "2_2") (pintype "passive"))
      (node (ref "R6") (pin "2") (pinfunction "2_2") (pintype "passive"))
      (node (ref "R8") (pin "2") (pinfunction "2_2") (pintype "passive"))
      (node (ref "TP12") (pin "P$1") (pinfunction "1_P$1") (pintype "bidirectional"))
      (node (ref "U1") (pin "1") (pinfunction "VIN_1") (pintype "bidirectional"))
      (node (ref "U11") (pin "5") (pinfunction "VBAT_5") (pintype "bidirectional"))
      (node (ref "U12") (pin "8") (pinfunction "V+_8") (pintype "bidirectional"))
      (node (ref "U2") (pin "8") (pinfunction "V+_8") (pintype "bidirectional"))
      (node (ref "U3") (pin "1") (pinfunction "VIN_1") (pintype "bidirectional"))
    )
    (net (code "167") (name "unconnected-(M2-ID-Pad4)") (class "Default")
      (node (ref "M2") (pin "4") (pinfunction "ID_4") (pintype "bidirectional"))
    )
    (net (code "168") (name "unconnected-(M12-2-PadP$2)") (class "Default")
      (node (ref "M12") (pin "P$2") (pinfunction "2_P$2") (pintype "bidirectional"))
    )
    (net (code "169") (name "unconnected-(U2-+INB-Pad5)") (class "Default")
      (node (ref "U2") (pin "5") (pinfunction "+INB_5") (pintype "input"))
    )
    (net (code "170") (name "unconnected-(U2--INB-Pad6)") (class "Default")
      (node (ref "U2") (pin "6") (pinfunction "-INB_6") (pintype "input"))
    )
    (net (code "171") (name "unconnected-(U2-OUTB-Pad7)") (class "Default")
      (node (ref "U2") (pin "7") (pinfunction "OUTB_7") (pintype "output"))
    )
    (net (code "172") (name "unconnected-(U9-VREF-Pad5)") (class "Default")
      (node (ref "U9") (pin "5") (pinfunction "VREF_5") (pintype "bidirectional"))
    )
    (net (code "173") (name "unconnected-(U10-VREF-Pad5)") (class "Default")
      (node (ref "U10") (pin "5") (pinfunction "VREF_5") (pintype "bidirectional"))
    )
    (net (code "174") (name "unconnected-(U12-+INB-Pad5)") (class "Default")
      (node (ref "U12") (pin "5") (pinfunction "+INB_5") (pintype "input"))
    )
    (net (code "175") (name "unconnected-(U12--INB-Pad6)") (class "Default")
      (node (ref "U12") (pin "6") (pinfunction "-INB_6") (pintype "input"))
    )
    (net (code "176") (name "unconnected-(U12-OUTB-Pad7)") (class "Default")
      (node (ref "U12") (pin "7") (pinfunction "OUTB_7") (pintype "output"))
    )
    (net (code "177") (name "unconnected-(U15-9.INT2-PadP$9)") (class "Default")
      (node (ref "U15") (pin "P$9") (pinfunction "9.INT2_P$9") (pintype "bidirectional"))
    )
    (net (code "178") (name "unconnected-(U15-11.INT1-PadP$11)") (class "Default")
      (node (ref "U15") (pin "P$11") (pinfunction "11.INT1_P$11") (pintype "bidirectional"))
    )
    (net (code "179") (name "unconnected-(U16-2.INT_2{slash}PWR_CTRL-PadP$2)") (class "Default")
      (node (ref "U16") (pin "P$2") (pinfunction "2.INT_2/PWR_CTRL_P$2") (pintype "bidirectional"))
    )
    (net (code "180") (name "unconnected-(U16-3.INT1-PadP$3)") (class "Default")
      (node (ref "U16") (pin "P$3") (pinfunction "3.INT1_P$3") (pintype "bidirectional"))
    )
    (net (code "181") (name "unconnected-(U17-DRDY-PadP$8)") (class "Default")
      (node (ref "U17") (pin "P$8") (pinfunction "DRDY_P$8") (pintype "bidirectional"))
    )
    (net (code "182") (name "unconnected-(U17-INT-PadP$7)") (class "Default")
      (node (ref "U17") (pin "P$7") (pinfunction "INT_P$7") (pintype "bidirectional"))
    )
    (net (code "183") (name "unconnected-(U18-7.PCM_CLK-PadP$7)") (class "Default")
      (node (ref "U18") (pin "P$7") (pinfunction "7.PCM_CLK_P$7") (pintype "bidirectional"))
    )
    (net (code "184") (name "unconnected-(U18-8.PCM_SYNC-PadP$8)") (class "Default")
      (node (ref "U18") (pin "P$8") (pinfunction "8.PCM_SYNC_P$8") (pintype "bidirectional"))
    )
    (net (code "185") (name "unconnected-(U18-9.PCM_IN-PadP$9)") (class "Default")
      (node (ref "U18") (pin "P$9") (pinfunction "9.PCM_IN_P$9") (pintype "bidirectional"))
    )
    (net (code "186") (name "unconnected-(U18-10.PCM_OUT-PadP$10)") (class "Default")
      (node (ref "U18") (pin "P$10") (pinfunction "10.PCM_OUT_P$10") (pintype "bidirectional"))
    )
    (net (code "187") (name "unconnected-(U18-16.UART_CTS-PadP$16)") (class "Default")
      (node (ref "U18") (pin "P$16") (pinfunction "16.UART_CTS_P$16") (pintype "bidirectional"))
    )
    (net (code "188") (name "unconnected-(U18-17.USB_D+-PadP$17)") (class "Default")
      (node (ref "U18") (pin "P$17") (pinfunction "17.USB_D+_P$17") (pintype "bidirectional"))
    )
    (net (code "189") (name "unconnected-(U18-18.USB_D--PadP$18)") (class "Default")
      (node (ref "U18") (pin "P$18") (pinfunction "18.USB_D-_P$18") (pintype "bidirectional"))
    )
    (net (code "190") (name "unconnected-(U18-30.AIO0-PadP$30)") (class "Default")
      (node (ref "U18") (pin "P$30") (pinfunction "30.AIO0_P$30") (pintype "bidirectional"))
    )
    (net (code "191") (name "unconnected-(U18-32.GPIO9-PadP$32)") (class "Default")
      (node (ref "U18") (pin "P$32") (pinfunction "32.GPIO9_P$32") (pintype "bidirectional"))
    )
    (net (code "192") (name "unconnected-(U18-33.GPIO10-PadP$33)") (class "Default")
      (node (ref "U18") (pin "P$33") (pinfunction "33.GPIO10_P$33") (pintype "bidirectional"))
    )
    (net (code "193") (name "unconnected-(U18-34.GPIO11-PadP$34)") (class "Default")
      (node (ref "U18") (pin "P$34") (pinfunction "34.GPIO11_P$34") (pintype "bidirectional"))
    )
    (net (code "194") (name "unconnected-(U18-35.AIO1-PadP$35)") (class "Default")
      (node (ref "U18") (pin "P$35") (pinfunction "35.AIO1_P$35") (pintype "bidirectional"))
    )
    (net (code "195") (name "unconnected-(U19-PA8-PadP$41)") (class "Default")
      (node (ref "U19") (pin "P$41") (pinfunction "PA8_P$41") (pintype "bidirectional"))
    )
    (net (code "196") (name "unconnected-(U19-PA10-PadP$43)") (class "Default")
      (node (ref "U19") (pin "P$43") (pinfunction "PA10_P$43") (pintype "bidirectional"))
    )
    (net (code "197") (name "unconnected-(U19-PC5-PadP$25)") (class "Default")
      (node (ref "U19") (pin "P$25") (pinfunction "PC5_P$25") (pintype "bidirectional"))
    )
    (net (code "198") (name "unconnected-(U19-PC13-PadP$2)") (class "Default")
      (node (ref "U19") (pin "P$2") (pinfunction "PC13_P$2") (pintype "bidirectional"))
    )
    (net (code "199") (name "unconnected-(U19-PC14-OSC32_IN-PadP$3)") (class "Default")
      (node (ref "U19") (pin "P$3") (pinfunction "PC14-OSC32_IN_P$3") (pintype "bidirectional"))
    )
    (net (code "200") (name "unconnected-(U19-PC15-OSC32_OUT-PadP$4)") (class "Default")
      (node (ref "U19") (pin "P$4") (pinfunction "PC15-OSC32_OUT_P$4") (pintype "bidirectional"))
    )
  )
)
